# backplane_v4.net
KiCad netlist of a schematic drawn in EAGLE
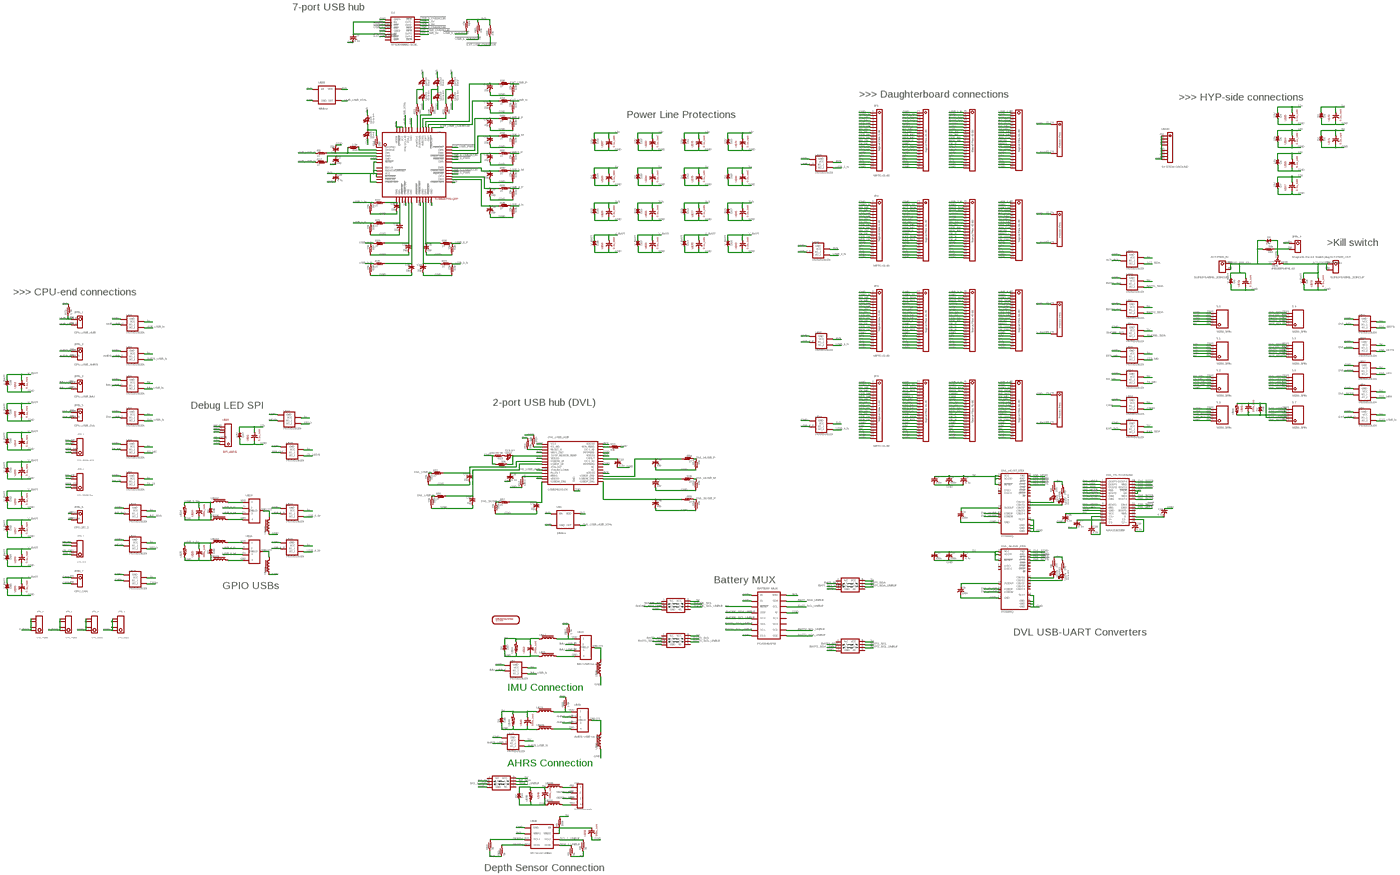
[diagram p0: schematic, sheet 1, overview]
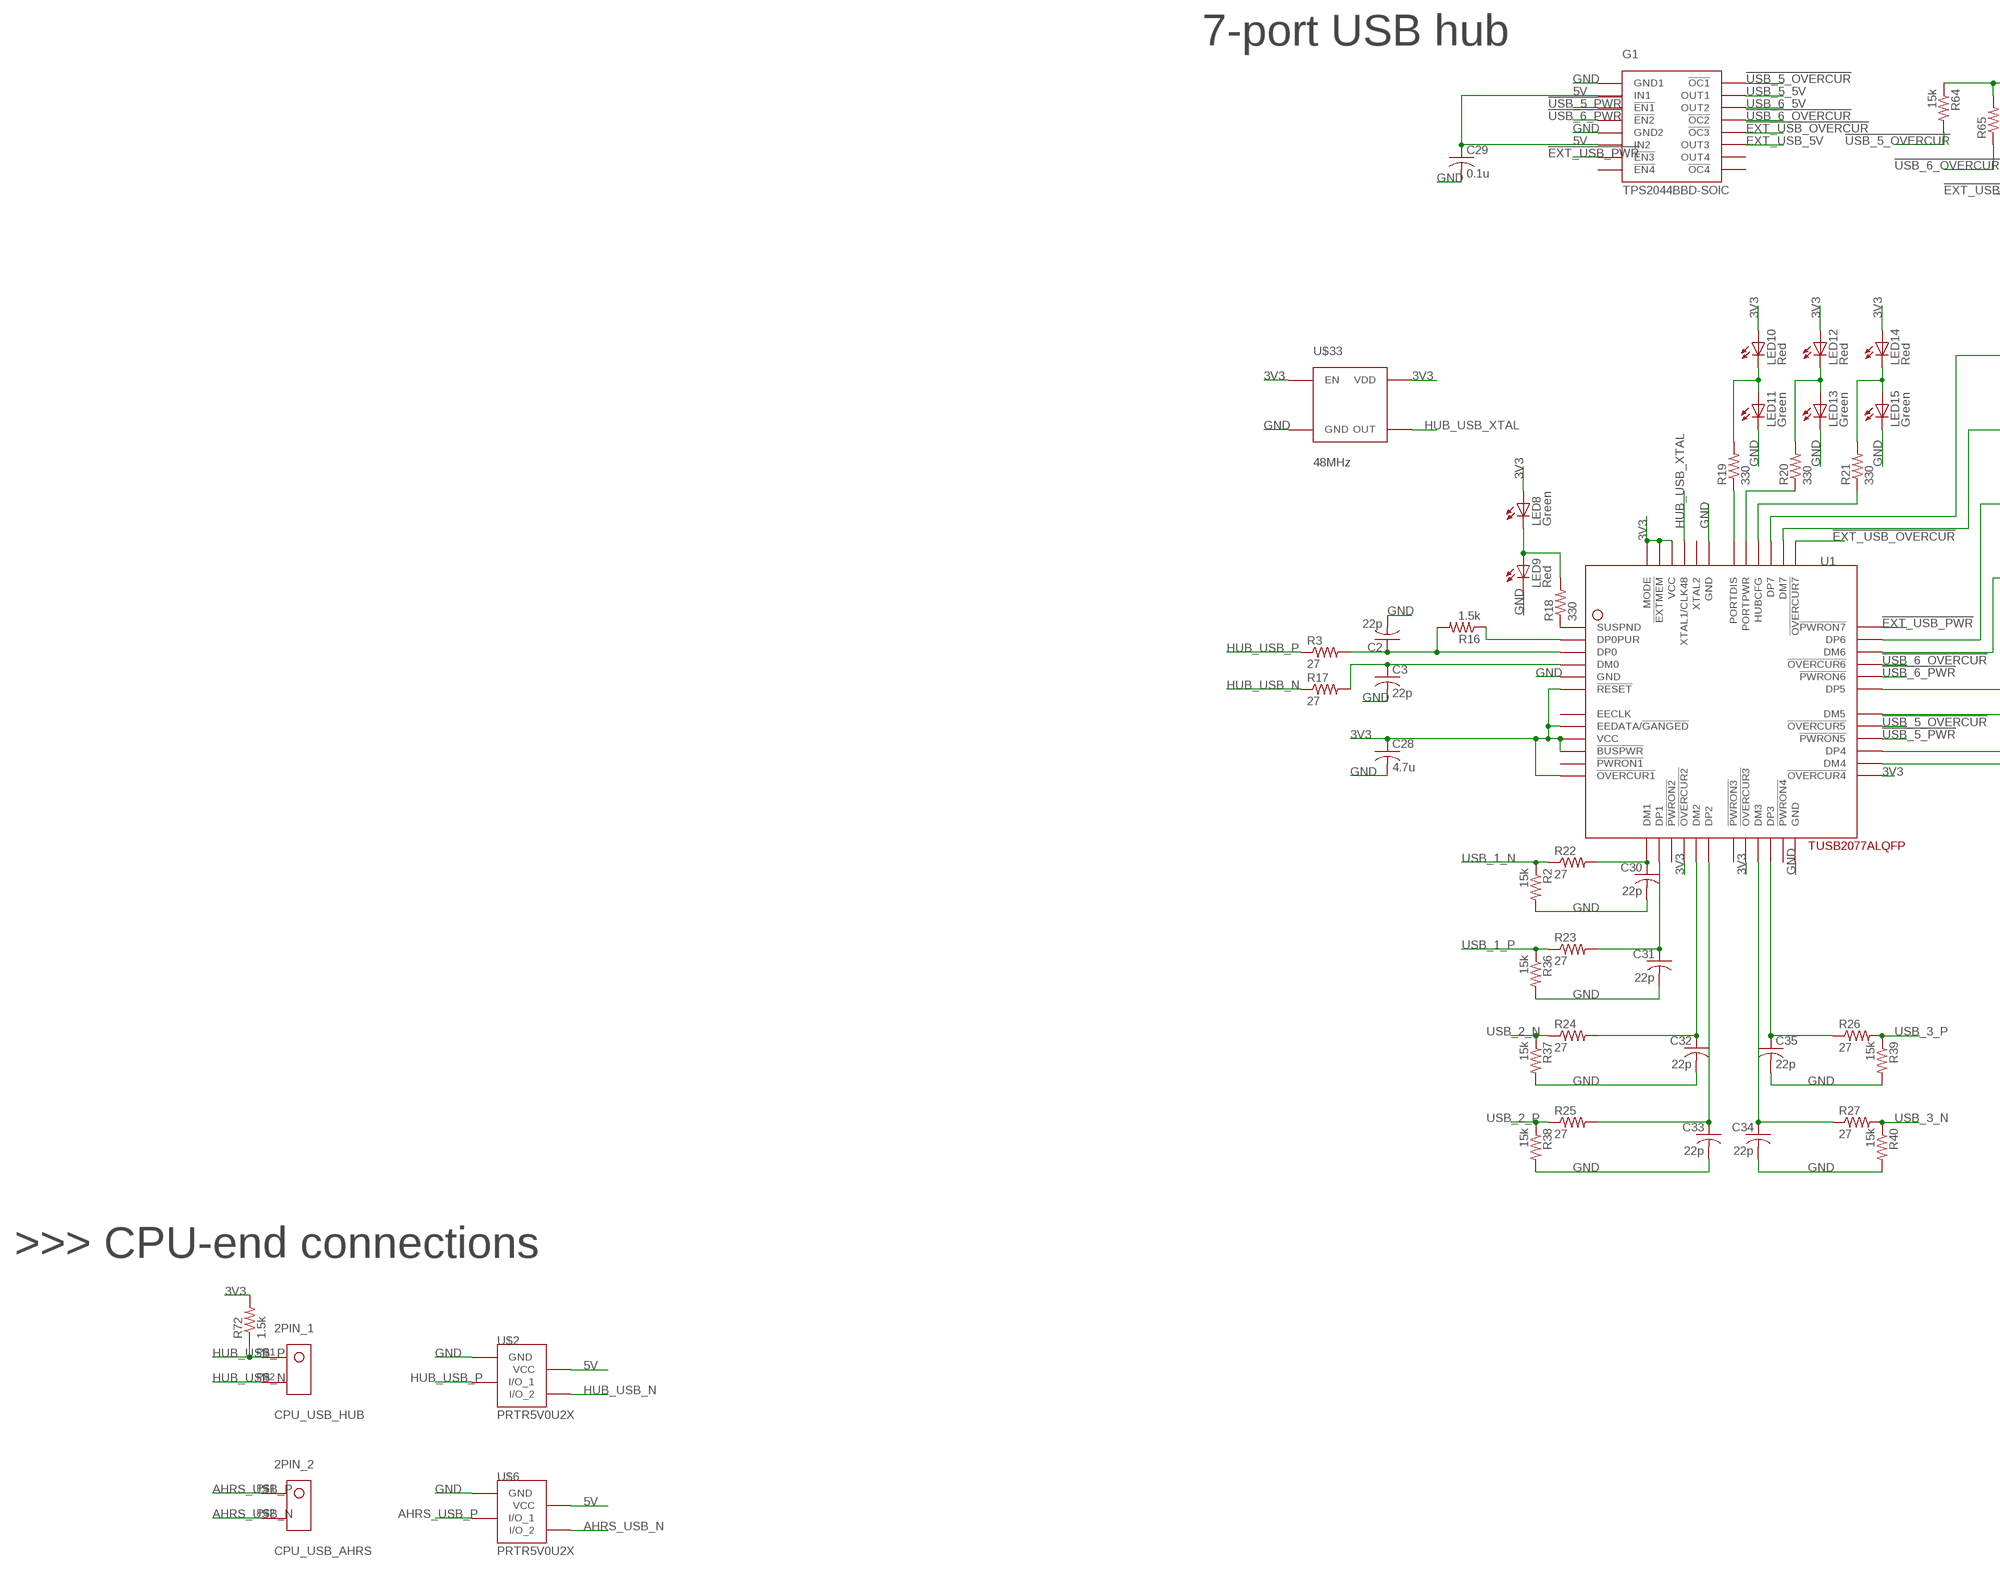
[diagram p1: schematic, sheet 1, part 1 of 5]
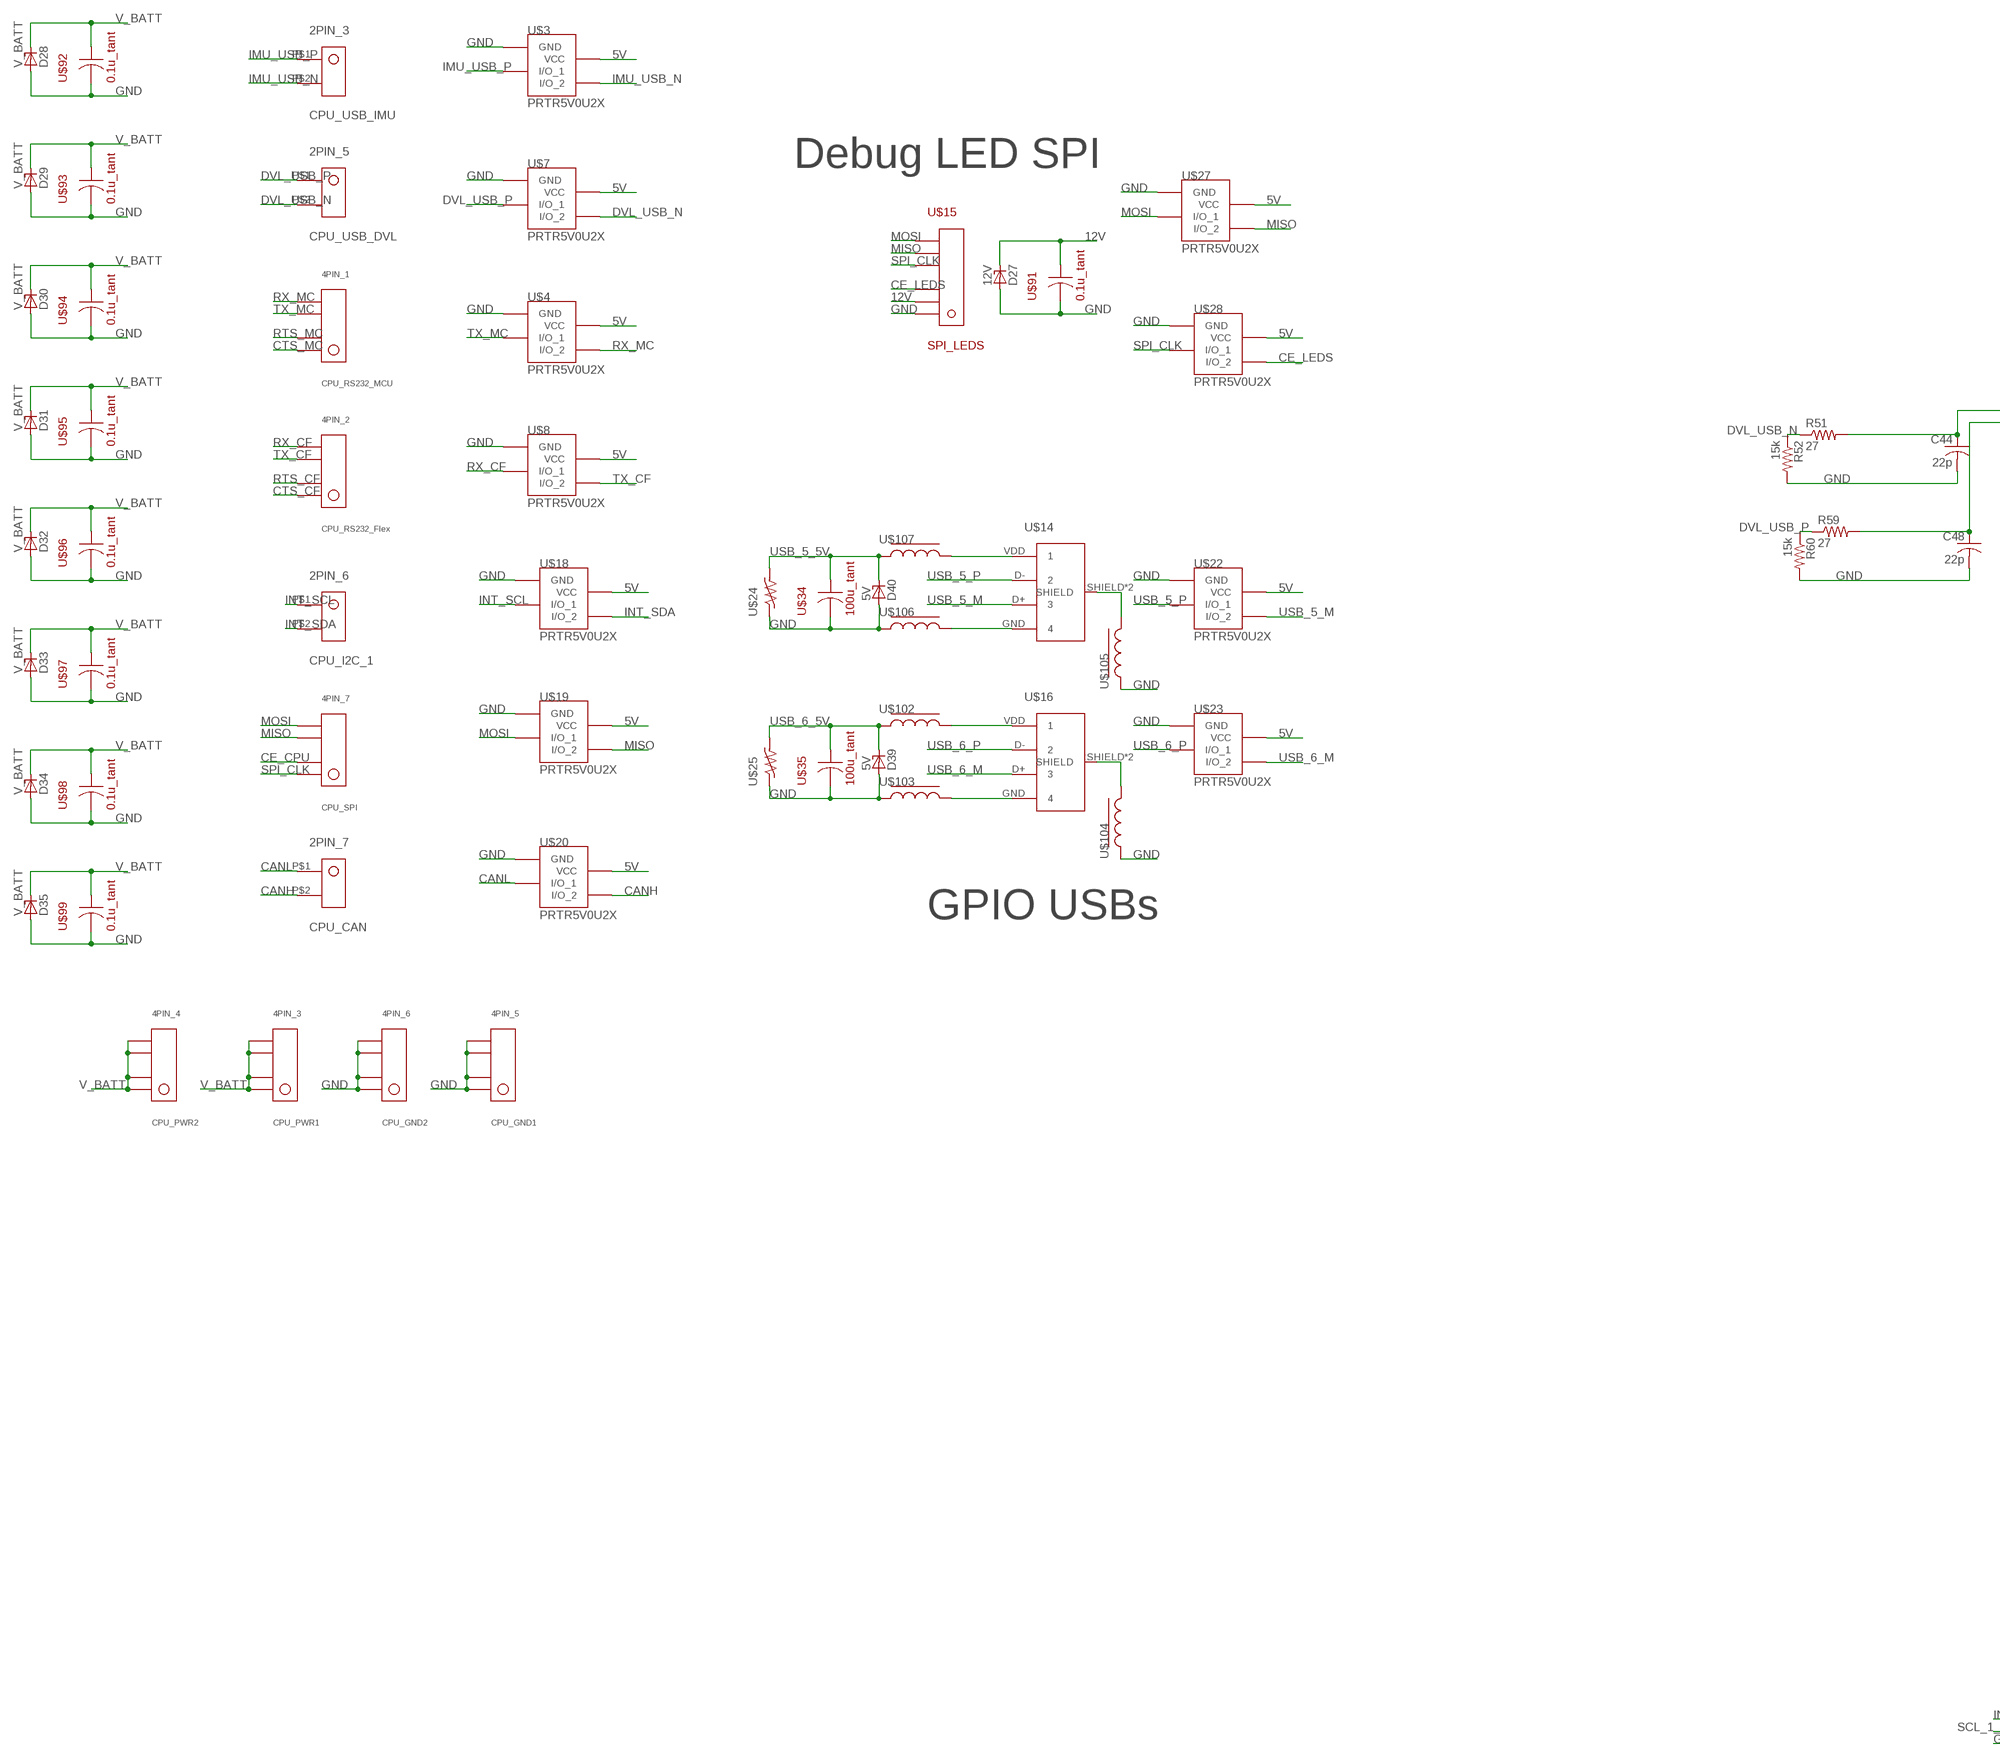
[diagram p2: schematic, sheet 1, part 2 of 5]
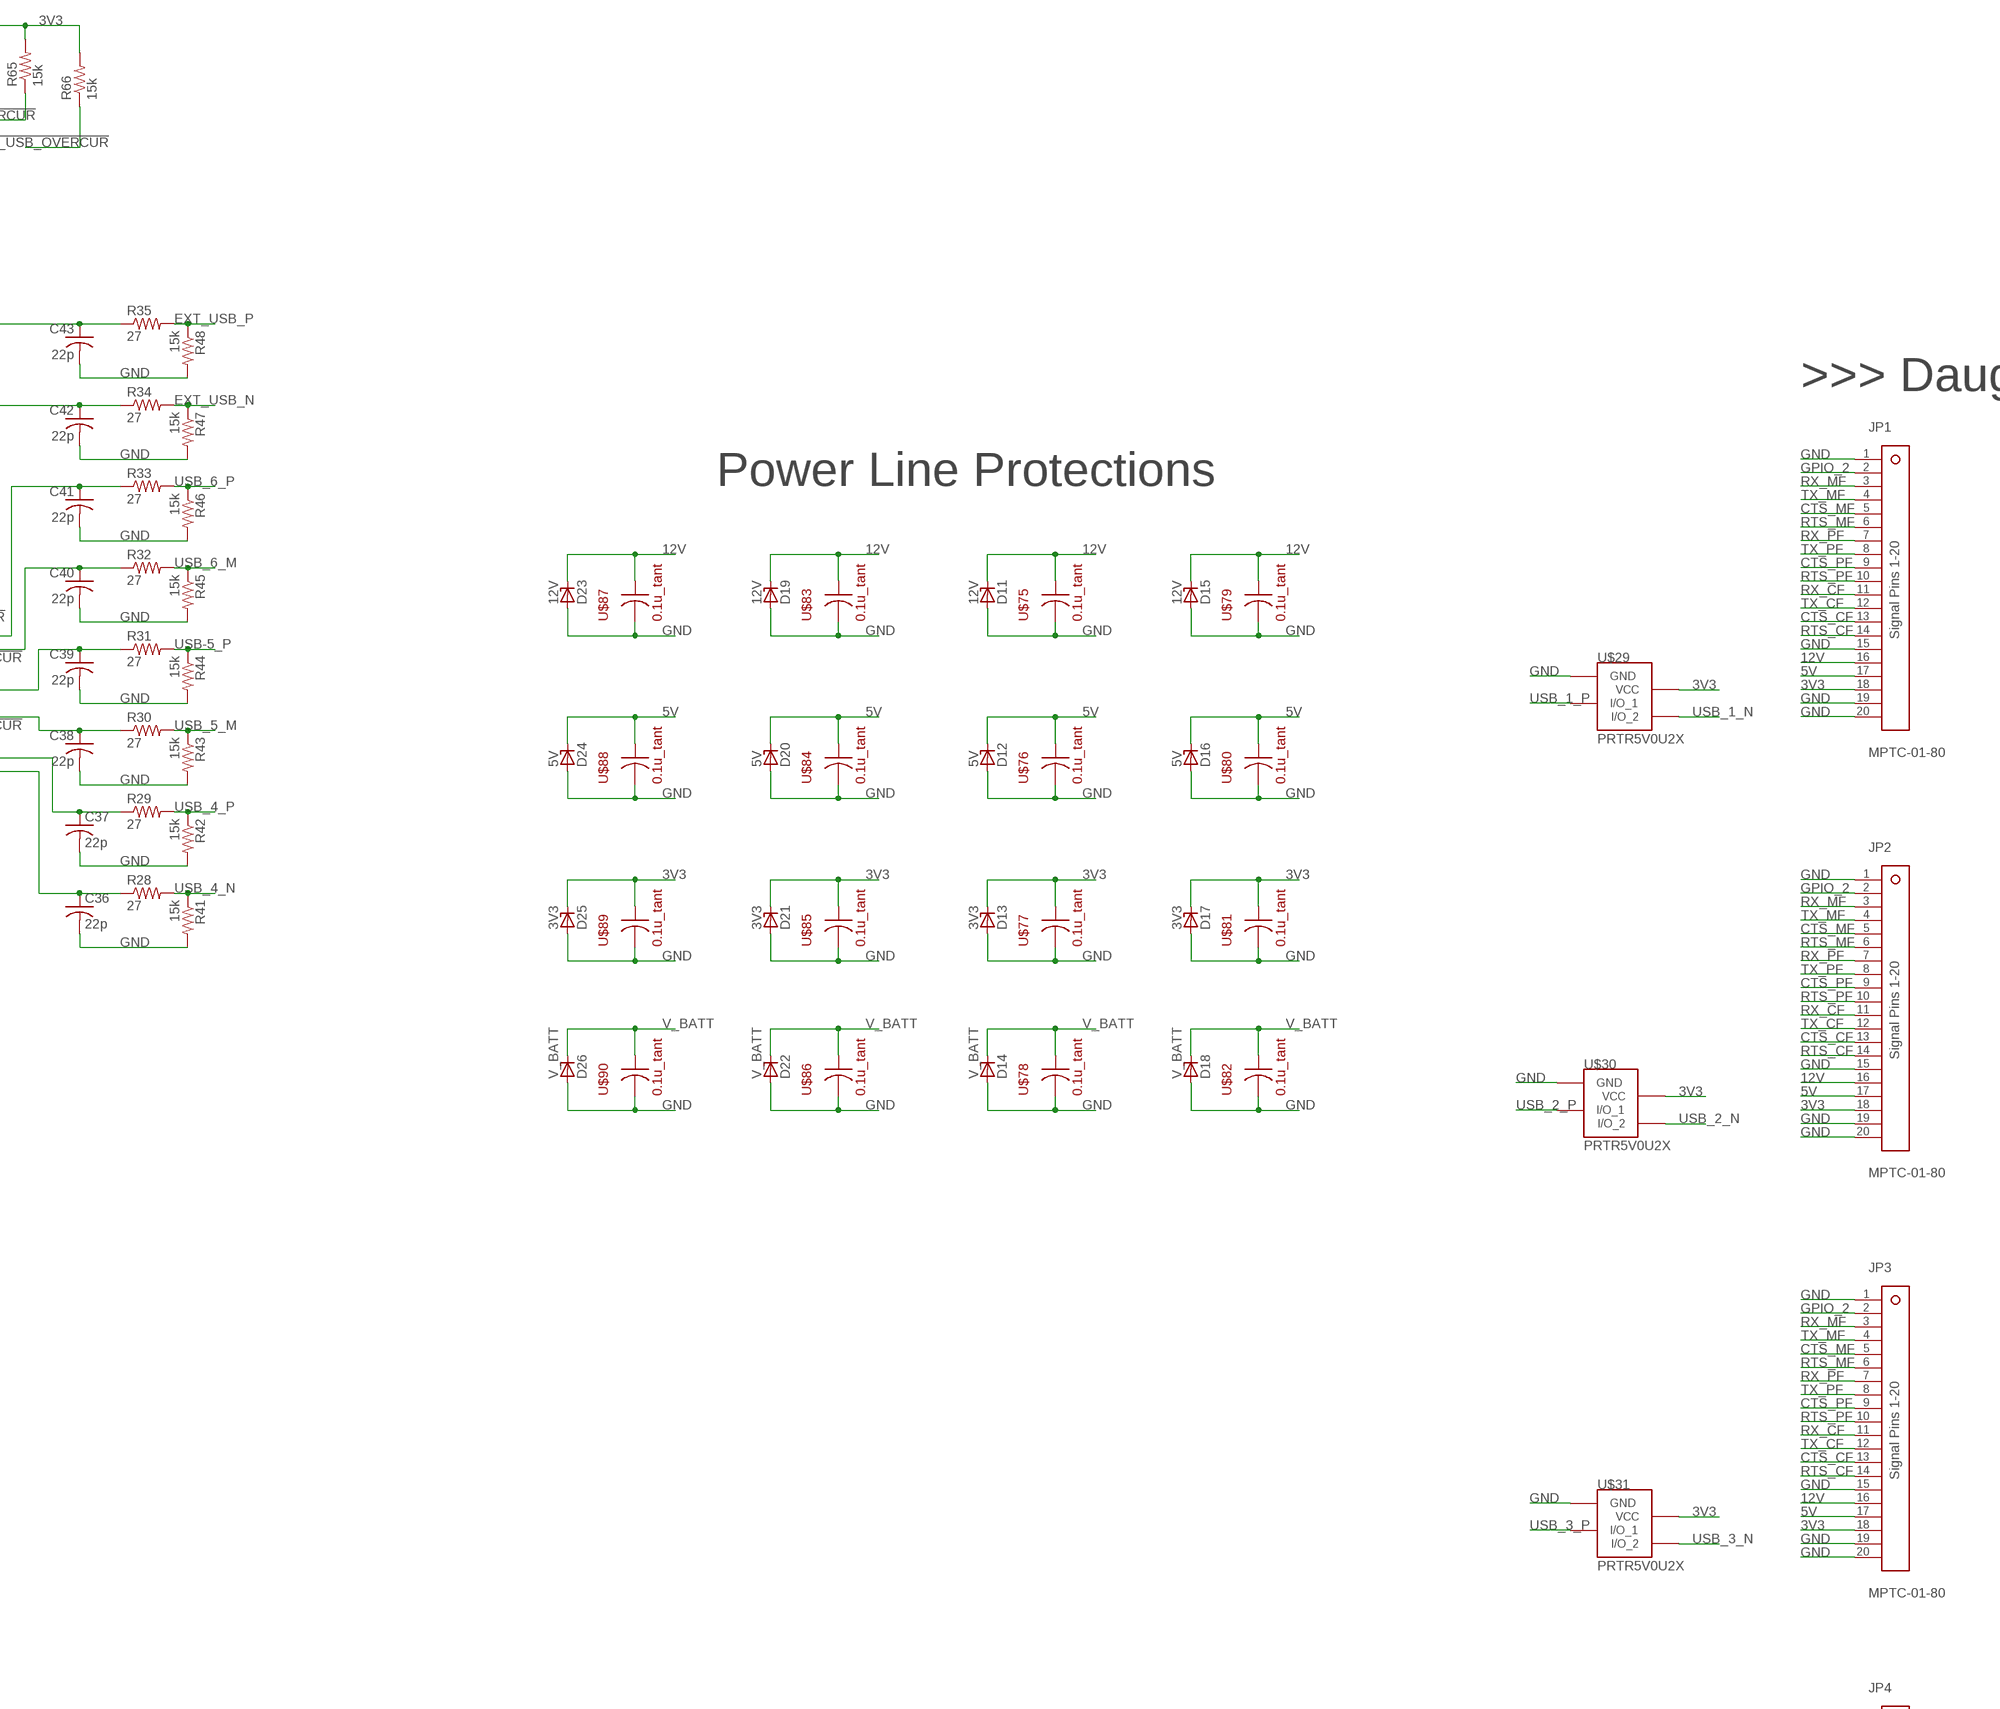
[diagram p3: schematic, sheet 1, part 3 of 5]
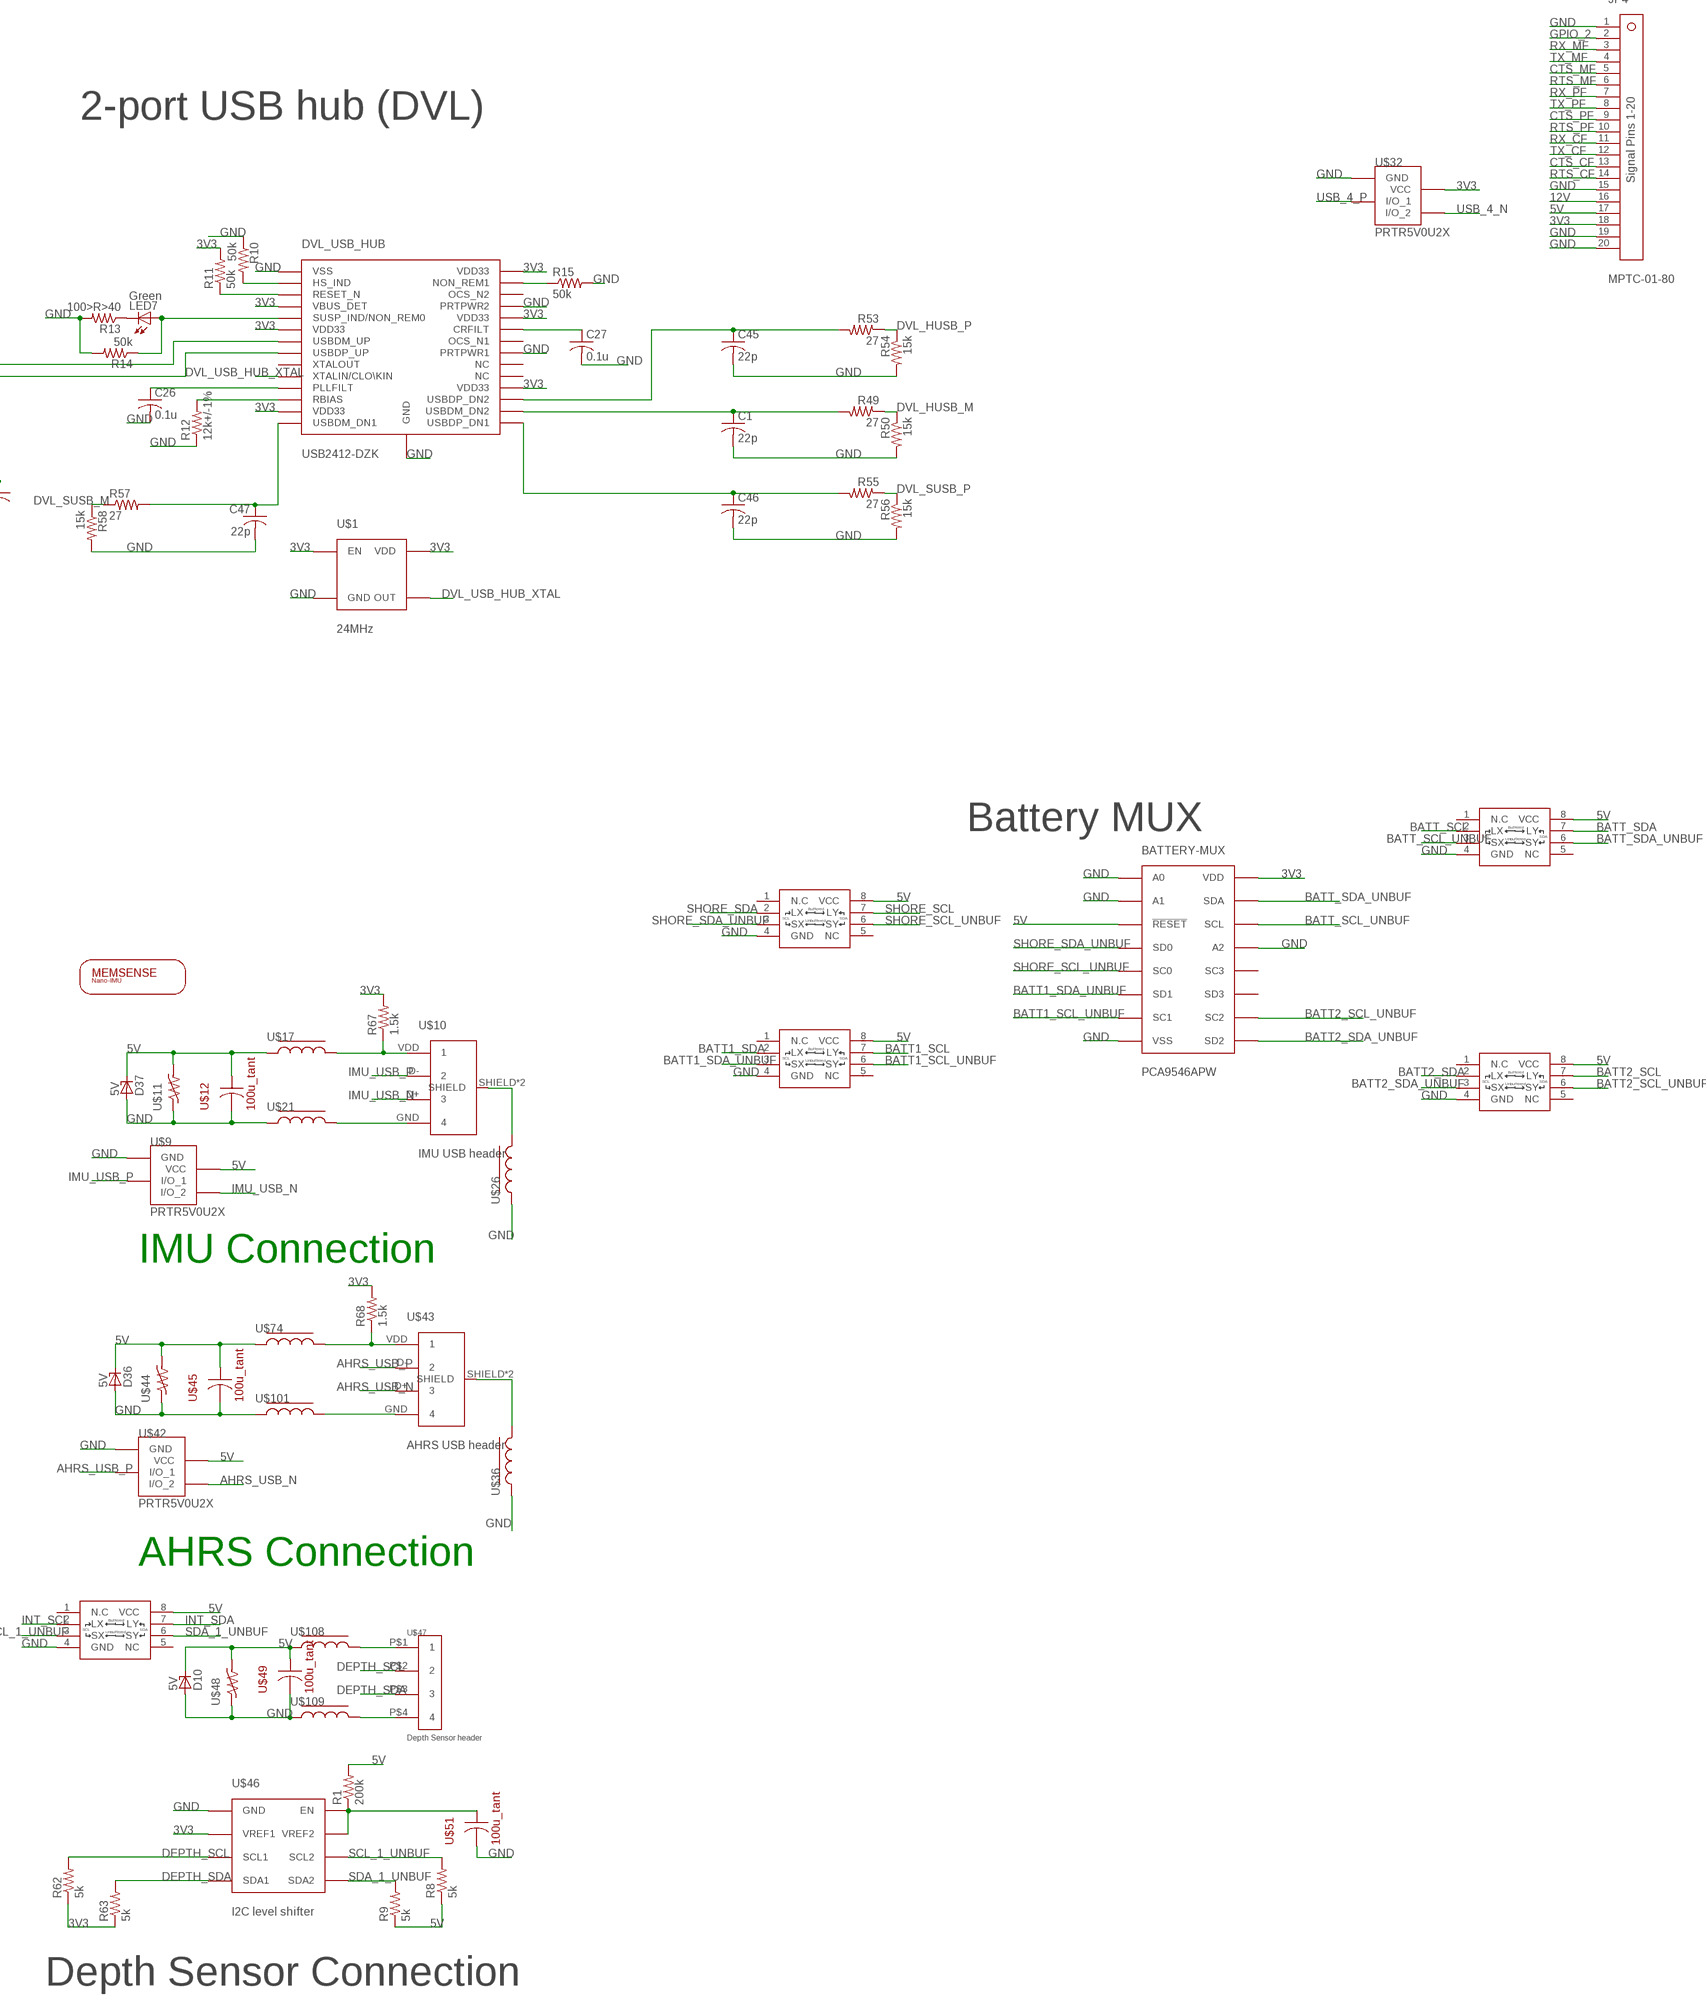
[diagram p4: schematic, sheet 1, part 4 of 5]
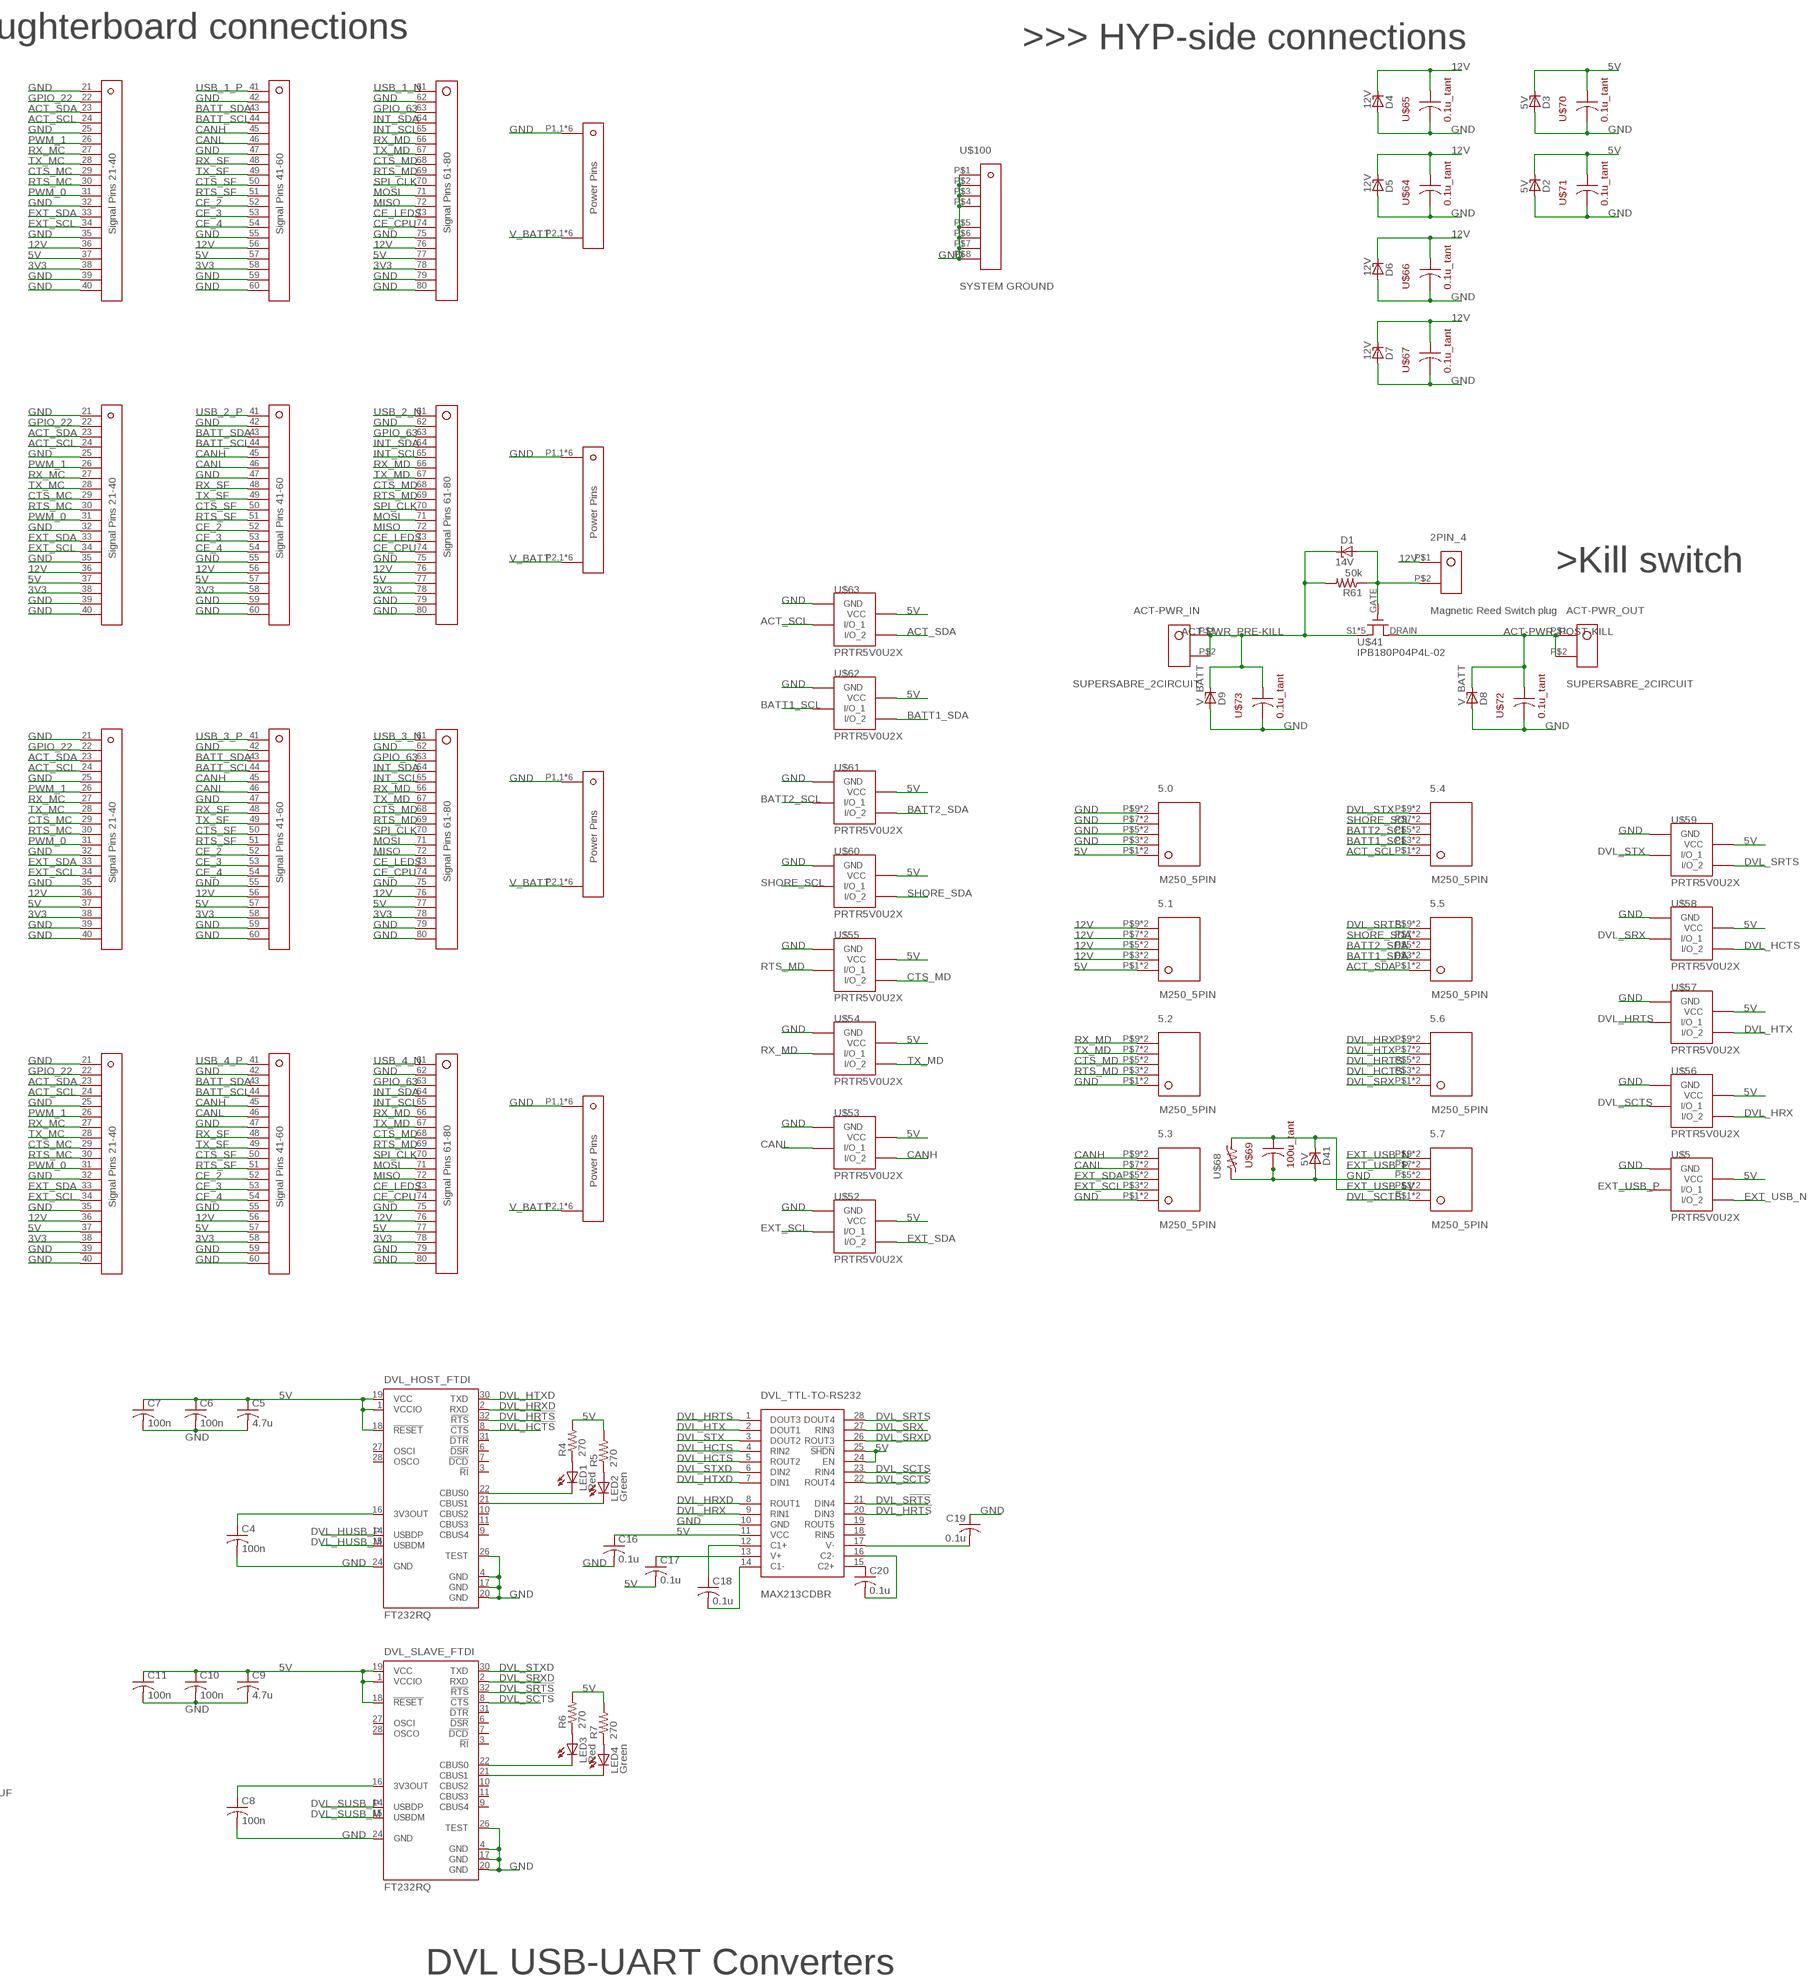
[diagram p5: schematic, sheet 1, part 5 of 5]

(export (version "E")
  (design (tool "Eeschema 10.0.6"))
  (components
    (comp (ref "2PIN_1")
      (value "CPU_USB_HUB")
      (footprint "eagle-import:KK254_VERT_2PIN")
      (libsource (lib "eagle-import") (part "KK254_VERT_2PIN22-29-2021"))
    )
    (comp (ref "2PIN_2")
      (value "CPU_USB_AHRS")
      (footprint "eagle-import:KK254_VERT_2PIN")
      (libsource (lib "eagle-import") (part "KK254_VERT_2PIN22-29-2021"))
    )
    (comp (ref "2PIN_3")
      (value "CPU_USB_IMU")
      (footprint "eagle-import:KK254_VERT_2PIN")
      (libsource (lib "eagle-import") (part "KK254_VERT_2PIN22-29-2021"))
    )
    (comp (ref "2PIN_4")
      (value "Magnetic Reed Switch plug")
      (footprint "eagle-import:KK254_VERT_2PIN")
      (libsource (lib "eagle-import") (part "KK254_VERT_2PIN22-29-2021"))
    )
    (comp (ref "2PIN_5")
      (value "CPU_USB_DVL")
      (footprint "eagle-import:KK254_VERT_2PIN")
      (libsource (lib "eagle-import") (part "KK254_VERT_2PIN22-29-2021"))
    )
    (comp (ref "2PIN_6")
      (value "CPU_I2C_1")
      (footprint "eagle-import:KK254_VERT_2PIN")
      (libsource (lib "eagle-import") (part "KK254_VERT_2PIN22-29-2021"))
    )
    (comp (ref "2PIN_7")
      (value "CPU_CAN")
      (footprint "eagle-import:KK254_VERT_2PIN")
      (libsource (lib "eagle-import") (part "KK254_VERT_2PIN22-29-2021"))
    )
    (comp (ref "4PIN_1")
      (value "CPU_RS232_MCU")
      (footprint "eagle-import:KK254_VERT_4PIN")
      (libsource (lib "eagle-import") (part "KK254_VERT_4PIN22-29-2041"))
    )
    (comp (ref "4PIN_2")
      (value "CPU_RS232_Flex")
      (footprint "eagle-import:KK254_VERT_4PIN")
      (libsource (lib "eagle-import") (part "KK254_VERT_4PIN22-29-2041"))
    )
    (comp (ref "4PIN_3")
      (value "CPU_PWR1")
      (footprint "eagle-import:KK254_VERT_4PIN")
      (libsource (lib "eagle-import") (part "KK254_VERT_4PIN22-29-2041"))
    )
    (comp (ref "4PIN_4")
      (value "CPU_PWR2")
      (footprint "eagle-import:KK254_VERT_4PIN")
      (libsource (lib "eagle-import") (part "KK254_VERT_4PIN22-29-2041"))
    )
    (comp (ref "4PIN_5")
      (value "CPU_GND1")
      (footprint "eagle-import:KK254_VERT_4PIN")
      (libsource (lib "eagle-import") (part "KK254_VERT_4PIN22-29-2041"))
    )
    (comp (ref "4PIN_6")
      (value "CPU_GND2")
      (footprint "eagle-import:KK254_VERT_4PIN")
      (libsource (lib "eagle-import") (part "KK254_VERT_4PIN22-29-2041"))
    )
    (comp (ref "4PIN_7")
      (value "CPU_SPI")
      (footprint "eagle-import:KK254_VERT_4PIN")
      (libsource (lib "eagle-import") (part "KK254_VERT_4PIN22-29-2041"))
    )
    (comp (ref "5.0")
      (value "M250_5PIN")
      (footprint "eagle-import:M205_5PIN")
      (libsource (lib "eagle-import") (part "M250_5PIN"))
    )
    (comp (ref "5.1")
      (value "M250_5PIN")
      (footprint "eagle-import:M205_5PIN")
      (libsource (lib "eagle-import") (part "M250_5PIN"))
    )
    (comp (ref "5.2")
      (value "M250_5PIN")
      (footprint "eagle-import:M205_5PIN")
      (libsource (lib "eagle-import") (part "M250_5PIN"))
    )
    (comp (ref "5.3")
      (value "M250_5PIN")
      (footprint "eagle-import:M205_5PIN")
      (libsource (lib "eagle-import") (part "M250_5PIN"))
    )
    (comp (ref "5.4")
      (value "M250_5PIN")
      (footprint "eagle-import:M205_5PIN")
      (libsource (lib "eagle-import") (part "M250_5PIN"))
    )
    (comp (ref "5.5")
      (value "M250_5PIN")
      (footprint "eagle-import:M205_5PIN")
      (libsource (lib "eagle-import") (part "M250_5PIN"))
    )
    (comp (ref "5.6")
      (value "M250_5PIN")
      (footprint "eagle-import:M205_5PIN")
      (libsource (lib "eagle-import") (part "M250_5PIN"))
    )
    (comp (ref "5.7")
      (value "M250_5PIN")
      (footprint "eagle-import:M205_5PIN")
      (libsource (lib "eagle-import") (part "M250_5PIN"))
    )
    (comp (ref "ACT-PWR_IN")
      (value "SUPERSABRE_2CIRCUIT")
      (footprint "eagle-import:SUPERSABRE_2CIRCUIT")
      (libsource (lib "eagle-import") (part "SUPERSABRE_2CIRCUIT"))
    )
    (comp (ref "ACT-PWR_OUT")
      (value "SUPERSABRE_2CIRCUIT")
      (footprint "eagle-import:SUPERSABRE_2CIRCUIT")
      (libsource (lib "eagle-import") (part "SUPERSABRE_2CIRCUIT"))
    )
    (comp (ref "BATTERY-MUX")
      (value "PCA9546APW")
      (footprint "eagle-import:TSSOP16")
      (libsource (lib "eagle-import") (part "PCA9546APW"))
    )
    (comp (ref "C1")
      (value "22p")
      (footprint "eagle-import:C0805")
      (libsource (lib "eagle-import") (part "C-USC0805"))
    )
    (comp (ref "C2")
      (value "22p")
      (footprint "eagle-import:C0805")
      (libsource (lib "eagle-import") (part "C-USC0805"))
    )
    (comp (ref "C3")
      (value "22p")
      (footprint "eagle-import:C0805")
      (libsource (lib "eagle-import") (part "C-USC0805"))
    )
    (comp (ref "C4")
      (value "100n")
      (footprint "eagle-import:C0805")
      (libsource (lib "eagle-import") (part "C-USC0805"))
    )
    (comp (ref "C5")
      (value "4.7u")
      (footprint "eagle-import:C0805")
      (libsource (lib "eagle-import") (part "C-USC0805"))
    )
    (comp (ref "C6")
      (value "100n")
      (footprint "eagle-import:C0805")
      (libsource (lib "eagle-import") (part "C-USC0805"))
    )
    (comp (ref "C7")
      (value "100n")
      (footprint "eagle-import:C0805")
      (libsource (lib "eagle-import") (part "C-USC0805"))
    )
    (comp (ref "C8")
      (value "100n")
      (footprint "eagle-import:C0805")
      (libsource (lib "eagle-import") (part "C-USC0805"))
    )
    (comp (ref "C9")
      (value "4.7u")
      (footprint "eagle-import:C0805")
      (libsource (lib "eagle-import") (part "C-USC0805"))
    )
    (comp (ref "C10")
      (value "100n")
      (footprint "eagle-import:C0805")
      (libsource (lib "eagle-import") (part "C-USC0805"))
    )
    (comp (ref "C11")
      (value "100n")
      (footprint "eagle-import:C0805")
      (libsource (lib "eagle-import") (part "C-USC0805"))
    )
    (comp (ref "C16")
      (value "0.1u")
      (footprint "eagle-import:C0805")
      (libsource (lib "eagle-import") (part "C-USC0805"))
    )
    (comp (ref "C17")
      (value "0.1u")
      (footprint "eagle-import:C0805")
      (libsource (lib "eagle-import") (part "C-USC0805"))
    )
    (comp (ref "C18")
      (value "0.1u")
      (footprint "eagle-import:C0805")
      (libsource (lib "eagle-import") (part "C-USC0805"))
    )
    (comp (ref "C19")
      (value "0.1u")
      (footprint "eagle-import:C0805")
      (libsource (lib "eagle-import") (part "C-USC0805"))
    )
    (comp (ref "C20")
      (value "0.1u")
      (footprint "eagle-import:C0805")
      (libsource (lib "eagle-import") (part "C-USC0805"))
    )
    (comp (ref "C26")
      (value "0.1u")
      (footprint "eagle-import:C0805")
      (libsource (lib "eagle-import") (part "C-USC0805"))
    )
    (comp (ref "C27")
      (value "0.1u")
      (footprint "eagle-import:C0805")
      (libsource (lib "eagle-import") (part "C-USC0805"))
    )
    (comp (ref "C28")
      (value "4.7u")
      (footprint "eagle-import:C0805")
      (libsource (lib "eagle-import") (part "C-USC0805"))
    )
    (comp (ref "C29")
      (value "0.1u")
      (footprint "eagle-import:C0805")
      (libsource (lib "eagle-import") (part "C-USC0805"))
    )
    (comp (ref "C30")
      (value "22p")
      (footprint "eagle-import:C0805")
      (libsource (lib "eagle-import") (part "C-USC0805"))
    )
    (comp (ref "C31")
      (value "22p")
      (footprint "eagle-import:C0805")
      (libsource (lib "eagle-import") (part "C-USC0805"))
    )
    (comp (ref "C32")
      (value "22p")
      (footprint "eagle-import:C0805")
      (libsource (lib "eagle-import") (part "C-USC0805"))
    )
    (comp (ref "C33")
      (value "22p")
      (footprint "eagle-import:C0805")
      (libsource (lib "eagle-import") (part "C-USC0805"))
    )
    (comp (ref "C34")
      (value "22p")
      (footprint "eagle-import:C0805")
      (libsource (lib "eagle-import") (part "C-USC0805"))
    )
    (comp (ref "C35")
      (value "22p")
      (footprint "eagle-import:C0805")
      (libsource (lib "eagle-import") (part "C-USC0805"))
    )
    (comp (ref "C36")
      (value "22p")
      (footprint "eagle-import:C0805")
      (libsource (lib "eagle-import") (part "C-USC0805"))
    )
    (comp (ref "C37")
      (value "22p")
      (footprint "eagle-import:C0805")
      (libsource (lib "eagle-import") (part "C-USC0805"))
    )
    (comp (ref "C38")
      (value "22p")
      (footprint "eagle-import:C0805")
      (libsource (lib "eagle-import") (part "C-USC0805"))
    )
    (comp (ref "C39")
      (value "22p")
      (footprint "eagle-import:C0805")
      (libsource (lib "eagle-import") (part "C-USC0805"))
    )
    (comp (ref "C40")
      (value "22p")
      (footprint "eagle-import:C0805")
      (libsource (lib "eagle-import") (part "C-USC0805"))
    )
    (comp (ref "C41")
      (value "22p")
      (footprint "eagle-import:C0805")
      (libsource (lib "eagle-import") (part "C-USC0805"))
    )
    (comp (ref "C42")
      (value "22p")
      (footprint "eagle-import:C0805")
      (libsource (lib "eagle-import") (part "C-USC0805"))
    )
    (comp (ref "C43")
      (value "22p")
      (footprint "eagle-import:C0805")
      (libsource (lib "eagle-import") (part "C-USC0805"))
    )
    (comp (ref "C44")
      (value "22p")
      (footprint "eagle-import:C0805")
      (libsource (lib "eagle-import") (part "C-USC0805"))
    )
    (comp (ref "C45")
      (value "22p")
      (footprint "eagle-import:C0805")
      (libsource (lib "eagle-import") (part "C-USC0805"))
    )
    (comp (ref "C46")
      (value "22p")
      (footprint "eagle-import:C0805")
      (libsource (lib "eagle-import") (part "C-USC0805"))
    )
    (comp (ref "C47")
      (value "22p")
      (footprint "eagle-import:C0805")
      (libsource (lib "eagle-import") (part "C-USC0805"))
    )
    (comp (ref "C48")
      (value "22p")
      (footprint "eagle-import:C0805")
      (libsource (lib "eagle-import") (part "C-USC0805"))
    )
    (comp (ref "D1")
      (value "14V")
      (footprint "eagle-import:SOD123")
      (libsource (lib "eagle-import") (part "ZENER-DIODESOD123"))
    )
    (comp (ref "D2")
      (value "5V")
      (footprint "eagle-import:SOD123")
      (libsource (lib "eagle-import") (part "ZENER-DIODESOD123"))
    )
    (comp (ref "D3")
      (value "5V")
      (footprint "eagle-import:SOD123")
      (libsource (lib "eagle-import") (part "ZENER-DIODESOD123"))
    )
    (comp (ref "D4")
      (value "12V")
      (footprint "eagle-import:SOD123")
      (libsource (lib "eagle-import") (part "ZENER-DIODESOD123"))
    )
    (comp (ref "D5")
      (value "12V")
      (footprint "eagle-import:SOD123")
      (libsource (lib "eagle-import") (part "ZENER-DIODESOD123"))
    )
    (comp (ref "D6")
      (value "12V")
      (footprint "eagle-import:SOD123")
      (libsource (lib "eagle-import") (part "ZENER-DIODESOD123"))
    )
    (comp (ref "D7")
      (value "12V")
      (footprint "eagle-import:SOD123")
      (libsource (lib "eagle-import") (part "ZENER-DIODESOD123"))
    )
    (comp (ref "D8")
      (value "V_BATT")
      (footprint "eagle-import:SOD123")
      (libsource (lib "eagle-import") (part "ZENER-DIODESOD123"))
    )
    (comp (ref "D9")
      (value "V_BATT")
      (footprint "eagle-import:SOD123")
      (libsource (lib "eagle-import") (part "ZENER-DIODESOD123"))
    )
    (comp (ref "D10")
      (value "5V")
      (footprint "eagle-import:SOD123")
      (libsource (lib "eagle-import") (part "ZENER-DIODESOD123"))
    )
    (comp (ref "D11")
      (value "12V")
      (footprint "eagle-import:SOD123")
      (libsource (lib "eagle-import") (part "ZENER-DIODESOD123"))
    )
    (comp (ref "D12")
      (value "5V")
      (footprint "eagle-import:SOD123")
      (libsource (lib "eagle-import") (part "ZENER-DIODESOD123"))
    )
    (comp (ref "D13")
      (value "3V3")
      (footprint "eagle-import:SOD123")
      (libsource (lib "eagle-import") (part "ZENER-DIODESOD123"))
    )
    (comp (ref "D14")
      (value "V_BATT")
      (footprint "eagle-import:SOD123")
      (libsource (lib "eagle-import") (part "ZENER-DIODESOD123"))
    )
    (comp (ref "D15")
      (value "12V")
      (footprint "eagle-import:SOD123")
      (libsource (lib "eagle-import") (part "ZENER-DIODESOD123"))
    )
    (comp (ref "D16")
      (value "5V")
      (footprint "eagle-import:SOD123")
      (libsource (lib "eagle-import") (part "ZENER-DIODESOD123"))
    )
    (comp (ref "D17")
      (value "3V3")
      (footprint "eagle-import:SOD123")
      (libsource (lib "eagle-import") (part "ZENER-DIODESOD123"))
    )
    (comp (ref "D18")
      (value "V_BATT")
      (footprint "eagle-import:SOD123")
      (libsource (lib "eagle-import") (part "ZENER-DIODESOD123"))
    )
    (comp (ref "D19")
      (value "12V")
      (footprint "eagle-import:SOD123")
      (libsource (lib "eagle-import") (part "ZENER-DIODESOD123"))
    )
    (comp (ref "D20")
      (value "5V")
      (footprint "eagle-import:SOD123")
      (libsource (lib "eagle-import") (part "ZENER-DIODESOD123"))
    )
    (comp (ref "D21")
      (value "3V3")
      (footprint "eagle-import:SOD123")
      (libsource (lib "eagle-import") (part "ZENER-DIODESOD123"))
    )
    (comp (ref "D22")
      (value "V_BATT")
      (footprint "eagle-import:SOD123")
      (libsource (lib "eagle-import") (part "ZENER-DIODESOD123"))
    )
    (comp (ref "D23")
      (value "12V")
      (footprint "eagle-import:SOD123")
      (libsource (lib "eagle-import") (part "ZENER-DIODESOD123"))
    )
    (comp (ref "D24")
      (value "5V")
      (footprint "eagle-import:SOD123")
      (libsource (lib "eagle-import") (part "ZENER-DIODESOD123"))
    )
    (comp (ref "D25")
      (value "3V3")
      (footprint "eagle-import:SOD123")
      (libsource (lib "eagle-import") (part "ZENER-DIODESOD123"))
    )
    (comp (ref "D26")
      (value "V_BATT")
      (footprint "eagle-import:SOD123")
      (libsource (lib "eagle-import") (part "ZENER-DIODESOD123"))
    )
    (comp (ref "D27")
      (value "12V")
      (footprint "eagle-import:SOD123")
      (libsource (lib "eagle-import") (part "ZENER-DIODESOD123"))
    )
    (comp (ref "D28")
      (value "V_BATT")
      (footprint "eagle-import:SOD123")
      (libsource (lib "eagle-import") (part "ZENER-DIODESOD123"))
    )
    (comp (ref "D29")
      (value "V_BATT")
      (footprint "eagle-import:SOD123")
      (libsource (lib "eagle-import") (part "ZENER-DIODESOD123"))
    )
    (comp (ref "D30")
      (value "V_BATT")
      (footprint "eagle-import:SOD123")
      (libsource (lib "eagle-import") (part "ZENER-DIODESOD123"))
    )
    (comp (ref "D31")
      (value "V_BATT")
      (footprint "eagle-import:SOD123")
      (libsource (lib "eagle-import") (part "ZENER-DIODESOD123"))
    )
    (comp (ref "D32")
      (value "V_BATT")
      (footprint "eagle-import:SOD123")
      (libsource (lib "eagle-import") (part "ZENER-DIODESOD123"))
    )
    (comp (ref "D33")
      (value "V_BATT")
      (footprint "eagle-import:SOD123")
      (libsource (lib "eagle-import") (part "ZENER-DIODESOD123"))
    )
    (comp (ref "D34")
      (value "V_BATT")
      (footprint "eagle-import:SOD123")
      (libsource (lib "eagle-import") (part "ZENER-DIODESOD123"))
    )
    (comp (ref "D35")
      (value "V_BATT")
      (footprint "eagle-import:SOD123")
      (libsource (lib "eagle-import") (part "ZENER-DIODESOD123"))
    )
    (comp (ref "D36")
      (value "5V")
      (footprint "eagle-import:SOD123")
      (libsource (lib "eagle-import") (part "ZENER-DIODESOD123"))
    )
    (comp (ref "D37")
      (value "5V")
      (footprint "eagle-import:SOD123")
      (libsource (lib "eagle-import") (part "ZENER-DIODESOD123"))
    )
    (comp (ref "D39")
      (value "5V")
      (footprint "eagle-import:SOD123")
      (libsource (lib "eagle-import") (part "ZENER-DIODESOD123"))
    )
    (comp (ref "D40")
      (value "5V")
      (footprint "eagle-import:SOD123")
      (libsource (lib "eagle-import") (part "ZENER-DIODESOD123"))
    )
    (comp (ref "D41")
      (value "5V")
      (footprint "eagle-import:SOD123")
      (libsource (lib "eagle-import") (part "ZENER-DIODESOD123"))
    )
    (comp (ref "DVL_HOST_FTDI")
      (value "FT232RQ")
      (footprint "eagle-import:QFN32")
      (libsource (lib "eagle-import") (part "FT232RQ"))
    )
    (comp (ref "DVL_SLAVE_FTDI")
      (value "FT232RQ")
      (footprint "eagle-import:QFN32")
      (libsource (lib "eagle-import") (part "FT232RQ"))
    )
    (comp (ref "DVL_TTL-TO-RS232")
      (value "MAX213CDBR")
      (footprint "eagle-import:SSOP28DB")
      (libsource (lib "eagle-import") (part "MAX213CDBR"))
    )
    (comp (ref "DVL_USB_HUB")
      (value "USB2412-DZK")
      (footprint "eagle-import:QFN-28")
      (libsource (lib "eagle-import") (part "USB2412-DZK"))
    )
    (comp (ref "G1")
      (value "TPS2044BBD-SOIC")
      (footprint "eagle-import:TPS2044")
      (libsource (lib "eagle-import") (part "TPS2044BBD-SOIC"))
    )
    (comp (ref "JP1")
      (value "MPTC-01-80")
      (footprint "eagle-import:MPTC-01-80")
      (libsource (lib "eagle-import") (part "MPTC-01-80"))
    )
    (comp (ref "JP2")
      (value "MPTC-01-80")
      (footprint "eagle-import:MPTC-01-80")
      (libsource (lib "eagle-import") (part "MPTC-01-80"))
    )
    (comp (ref "JP3")
      (value "MPTC-01-80")
      (footprint "eagle-import:MPTC-01-80")
      (libsource (lib "eagle-import") (part "MPTC-01-80"))
    )
    (comp (ref "JP4")
      (value "MPTC-01-80")
      (footprint "eagle-import:MPTC-01-80")
      (libsource (lib "eagle-import") (part "MPTC-01-80"))
    )
    (comp (ref "LED1")
      (value "Red")
      (footprint "eagle-import:CHIPLED_0805")
      (libsource (lib "eagle-import") (part "LEDCHIPLED_0805"))
    )
    (comp (ref "LED2")
      (value "Green")
      (footprint "eagle-import:CHIPLED_0805")
      (libsource (lib "eagle-import") (part "LEDCHIPLED_0805"))
    )
    (comp (ref "LED3")
      (value "Red")
      (footprint "eagle-import:CHIPLED_0805")
      (libsource (lib "eagle-import") (part "LEDCHIPLED_0805"))
    )
    (comp (ref "LED4")
      (value "Green")
      (footprint "eagle-import:CHIPLED_0805")
      (libsource (lib "eagle-import") (part "LEDCHIPLED_0805"))
    )
    (comp (ref "LED7")
      (value "Green")
      (footprint "eagle-import:CHIPLED_0805")
      (libsource (lib "eagle-import") (part "LEDCHIPLED_0805"))
    )
    (comp (ref "LED8")
      (value "Green")
      (footprint "eagle-import:CHIP-LED0805")
      (libsource (lib "eagle-import") (part "LEDCHIP-LED0805"))
    )
    (comp (ref "LED9")
      (value "Red")
      (footprint "eagle-import:CHIP-LED0805")
      (libsource (lib "eagle-import") (part "LEDCHIP-LED0805"))
    )
    (comp (ref "LED10")
      (value "Red")
      (footprint "eagle-import:CHIP-LED0805")
      (libsource (lib "eagle-import") (part "LEDCHIP-LED0805"))
    )
    (comp (ref "LED11")
      (value "Green")
      (footprint "eagle-import:CHIP-LED0805")
      (libsource (lib "eagle-import") (part "LEDCHIP-LED0805"))
    )
    (comp (ref "LED12")
      (value "Red")
      (footprint "eagle-import:CHIP-LED0805")
      (libsource (lib "eagle-import") (part "LEDCHIP-LED0805"))
    )
    (comp (ref "LED13")
      (value "Green")
      (footprint "eagle-import:CHIP-LED0805")
      (libsource (lib "eagle-import") (part "LEDCHIP-LED0805"))
    )
    (comp (ref "LED14")
      (value "Red")
      (footprint "eagle-import:CHIP-LED0805")
      (libsource (lib "eagle-import") (part "LEDCHIP-LED0805"))
    )
    (comp (ref "LED15")
      (value "Green")
      (footprint "eagle-import:CHIP-LED0805")
      (libsource (lib "eagle-import") (part "LEDCHIP-LED0805"))
    )
    (comp (ref "R1")
      (value "200k")
      (footprint "eagle-import:R0805")
      (libsource (lib "eagle-import") (part "R-US_R0805"))
    )
    (comp (ref "R2")
      (value "15k")
      (footprint "eagle-import:R0805")
      (libsource (lib "eagle-import") (part "R-US_R0805"))
    )
    (comp (ref "R3")
      (value "27")
      (footprint "eagle-import:R0805")
      (libsource (lib "eagle-import") (part "R-US_R0805"))
    )
    (comp (ref "R4")
      (value "270")
      (footprint "eagle-import:R0805")
      (libsource (lib "eagle-import") (part "R-US_R0805"))
    )
    (comp (ref "R5")
      (value "270")
      (footprint "eagle-import:R0805")
      (libsource (lib "eagle-import") (part "R-US_R0805"))
    )
    (comp (ref "R6")
      (value "270")
      (footprint "eagle-import:R0805")
      (libsource (lib "eagle-import") (part "R-US_R0805"))
    )
    (comp (ref "R7")
      (value "270")
      (footprint "eagle-import:R0805")
      (libsource (lib "eagle-import") (part "R-US_R0805"))
    )
    (comp (ref "R8")
      (value "5k")
      (footprint "eagle-import:R0805")
      (libsource (lib "eagle-import") (part "R-US_R0805"))
    )
    (comp (ref "R9")
      (value "5k")
      (footprint "eagle-import:R0805")
      (libsource (lib "eagle-import") (part "R-US_R0805"))
    )
    (comp (ref "R10")
      (value "50k")
      (footprint "eagle-import:R0805")
      (libsource (lib "eagle-import") (part "R-US_R0805"))
    )
    (comp (ref "R11")
      (value "50k")
      (footprint "eagle-import:R0805")
      (libsource (lib "eagle-import") (part "R-US_R0805"))
    )
    (comp (ref "R12")
      (value "12k+/-1%")
      (footprint "eagle-import:R0805")
      (libsource (lib "eagle-import") (part "R-US_R0805"))
    )
    (comp (ref "R13")
      (value "100>R>40")
      (footprint "eagle-import:R0805")
      (libsource (lib "eagle-import") (part "R-US_R0805"))
    )
    (comp (ref "R14")
      (value "50k")
      (footprint "eagle-import:R0805")
      (libsource (lib "eagle-import") (part "R-US_R0805"))
    )
    (comp (ref "R15")
      (value "50k")
      (footprint "eagle-import:R0805")
      (libsource (lib "eagle-import") (part "R-US_R0805"))
    )
    (comp (ref "R16")
      (value "1.5k")
      (footprint "eagle-import:R0805")
      (libsource (lib "eagle-import") (part "R-US_R0805"))
    )
    (comp (ref "R17")
      (value "27")
      (footprint "eagle-import:R0805")
      (libsource (lib "eagle-import") (part "R-US_R0805"))
    )
    (comp (ref "R18")
      (value "330")
      (footprint "eagle-import:R0805")
      (libsource (lib "eagle-import") (part "R-US_R0805"))
    )
    (comp (ref "R19")
      (value "330")
      (footprint "eagle-import:R0805")
      (libsource (lib "eagle-import") (part "R-US_R0805"))
    )
    (comp (ref "R20")
      (value "330")
      (footprint "eagle-import:R0805")
      (libsource (lib "eagle-import") (part "R-US_R0805"))
    )
    (comp (ref "R21")
      (value "330")
      (footprint "eagle-import:R0805")
      (libsource (lib "eagle-import") (part "R-US_R0805"))
    )
    (comp (ref "R22")
      (value "27")
      (footprint "eagle-import:R0805")
      (libsource (lib "eagle-import") (part "R-US_R0805"))
    )
    (comp (ref "R23")
      (value "27")
      (footprint "eagle-import:R0805")
      (libsource (lib "eagle-import") (part "R-US_R0805"))
    )
    (comp (ref "R24")
      (value "27")
      (footprint "eagle-import:R0805")
      (libsource (lib "eagle-import") (part "R-US_R0805"))
    )
    (comp (ref "R25")
      (value "27")
      (footprint "eagle-import:R0805")
      (libsource (lib "eagle-import") (part "R-US_R0805"))
    )
    (comp (ref "R26")
      (value "27")
      (footprint "eagle-import:R0805")
      (libsource (lib "eagle-import") (part "R-US_R0805"))
    )
    (comp (ref "R27")
      (value "27")
      (footprint "eagle-import:R0805")
      (libsource (lib "eagle-import") (part "R-US_R0805"))
    )
    (comp (ref "R28")
      (value "27")
      (footprint "eagle-import:R0805")
      (libsource (lib "eagle-import") (part "R-US_R0805"))
    )
    (comp (ref "R29")
      (value "27")
      (footprint "eagle-import:R0805")
      (libsource (lib "eagle-import") (part "R-US_R0805"))
    )
    (comp (ref "R30")
      (value "27")
      (footprint "eagle-import:R0805")
      (libsource (lib "eagle-import") (part "R-US_R0805"))
    )
    (comp (ref "R31")
      (value "27")
      (footprint "eagle-import:R0805")
      (libsource (lib "eagle-import") (part "R-US_R0805"))
    )
    (comp (ref "R32")
      (value "27")
      (footprint "eagle-import:R0805")
      (libsource (lib "eagle-import") (part "R-US_R0805"))
    )
    (comp (ref "R33")
      (value "27")
      (footprint "eagle-import:R0805")
      (libsource (lib "eagle-import") (part "R-US_R0805"))
    )
    (comp (ref "R34")
      (value "27")
      (footprint "eagle-import:R0805")
      (libsource (lib "eagle-import") (part "R-US_R0805"))
    )
    (comp (ref "R35")
      (value "27")
      (footprint "eagle-import:R0805")
      (libsource (lib "eagle-import") (part "R-US_R0805"))
    )
    (comp (ref "R36")
      (value "15k")
      (footprint "eagle-import:R0805")
      (libsource (lib "eagle-import") (part "R-US_R0805"))
    )
    (comp (ref "R37")
      (value "15k")
      (footprint "eagle-import:R0805")
      (libsource (lib "eagle-import") (part "R-US_R0805"))
    )
    (comp (ref "R38")
      (value "15k")
      (footprint "eagle-import:R0805")
      (libsource (lib "eagle-import") (part "R-US_R0805"))
    )
    (comp (ref "R39")
      (value "15k")
      (footprint "eagle-import:R0805")
      (libsource (lib "eagle-import") (part "R-US_R0805"))
    )
    (comp (ref "R40")
      (value "15k")
      (footprint "eagle-import:R0805")
      (libsource (lib "eagle-import") (part "R-US_R0805"))
    )
    (comp (ref "R41")
      (value "15k")
      (footprint "eagle-import:R0805")
      (libsource (lib "eagle-import") (part "R-US_R0805"))
    )
    (comp (ref "R42")
      (value "15k")
      (footprint "eagle-import:R0805")
      (libsource (lib "eagle-import") (part "R-US_R0805"))
    )
    (comp (ref "R43")
      (value "15k")
      (footprint "eagle-import:R0805")
      (libsource (lib "eagle-import") (part "R-US_R0805"))
    )
    (comp (ref "R44")
      (value "15k")
      (footprint "eagle-import:R0805")
      (libsource (lib "eagle-import") (part "R-US_R0805"))
    )
    (comp (ref "R45")
      (value "15k")
      (footprint "eagle-import:R0805")
      (libsource (lib "eagle-import") (part "R-US_R0805"))
    )
    (comp (ref "R46")
      (value "15k")
      (footprint "eagle-import:R0805")
      (libsource (lib "eagle-import") (part "R-US_R0805"))
    )
    (comp (ref "R47")
      (value "15k")
      (footprint "eagle-import:R0805")
      (libsource (lib "eagle-import") (part "R-US_R0805"))
    )
    (comp (ref "R48")
      (value "15k")
      (footprint "eagle-import:R0805")
      (libsource (lib "eagle-import") (part "R-US_R0805"))
    )
    (comp (ref "R49")
      (value "27")
      (footprint "eagle-import:R0805")
      (libsource (lib "eagle-import") (part "R-US_R0805"))
    )
    (comp (ref "R50")
      (value "15k")
      (footprint "eagle-import:R0805")
      (libsource (lib "eagle-import") (part "R-US_R0805"))
    )
    (comp (ref "R51")
      (value "27")
      (footprint "eagle-import:R0805")
      (libsource (lib "eagle-import") (part "R-US_R0805"))
    )
    (comp (ref "R52")
      (value "15k")
      (footprint "eagle-import:R0805")
      (libsource (lib "eagle-import") (part "R-US_R0805"))
    )
    (comp (ref "R53")
      (value "27")
      (footprint "eagle-import:R0805")
      (libsource (lib "eagle-import") (part "R-US_R0805"))
    )
    (comp (ref "R54")
      (value "15k")
      (footprint "eagle-import:R0805")
      (libsource (lib "eagle-import") (part "R-US_R0805"))
    )
    (comp (ref "R55")
      (value "27")
      (footprint "eagle-import:R0805")
      (libsource (lib "eagle-import") (part "R-US_R0805"))
    )
    (comp (ref "R56")
      (value "15k")
      (footprint "eagle-import:R0805")
      (libsource (lib "eagle-import") (part "R-US_R0805"))
    )
    (comp (ref "R57")
      (value "27")
      (footprint "eagle-import:R0805")
      (libsource (lib "eagle-import") (part "R-US_R0805"))
    )
    (comp (ref "R58")
      (value "15k")
      (footprint "eagle-import:R0805")
      (libsource (lib "eagle-import") (part "R-US_R0805"))
    )
    (comp (ref "R59")
      (value "27")
      (footprint "eagle-import:R0805")
      (libsource (lib "eagle-import") (part "R-US_R0805"))
    )
    (comp (ref "R60")
      (value "15k")
      (footprint "eagle-import:R0805")
      (libsource (lib "eagle-import") (part "R-US_R0805"))
    )
    (comp (ref "R61")
      (value "50k")
      (footprint "eagle-import:R0805")
      (libsource (lib "eagle-import") (part "R-US_R0805"))
    )
    (comp (ref "R62")
      (value "5k")
      (footprint "eagle-import:R0805")
      (libsource (lib "eagle-import") (part "R-US_R0805"))
    )
    (comp (ref "R63")
      (value "5k")
      (footprint "eagle-import:R0805")
      (libsource (lib "eagle-import") (part "R-US_R0805"))
    )
    (comp (ref "R64")
      (value "15k")
      (footprint "eagle-import:R0805")
      (libsource (lib "eagle-import") (part "R-US_R0805"))
    )
    (comp (ref "R65")
      (value "15k")
      (footprint "eagle-import:R0805")
      (libsource (lib "eagle-import") (part "R-US_R0805"))
    )
    (comp (ref "R66")
      (value "15k")
      (footprint "eagle-import:R0805")
      (libsource (lib "eagle-import") (part "R-US_R0805"))
    )
    (comp (ref "R67")
      (value "1.5k")
      (footprint "eagle-import:R0805")
      (libsource (lib "eagle-import") (part "R-US_R0805"))
    )
    (comp (ref "R68")
      (value "1.5k")
      (footprint "eagle-import:R0805")
      (libsource (lib "eagle-import") (part "R-US_R0805"))
    )
    (comp (ref "R72")
      (value "1.5k")
      (footprint "eagle-import:R0805")
      (libsource (lib "eagle-import") (part "R-US_R0805"))
    )
    (comp (ref "U$1")
      (value "24MHz")
      (footprint "eagle-import:4-CDFN_3.2X2.5MM")
      (libsource (lib "eagle-import") (part "DCS6XXX"))
    )
    (comp (ref "U$2")
      (value "PRTR5V0U2X")
      (footprint "eagle-import:SOT143B")
      (libsource (lib "eagle-import") (part "PRTR5V0U2X"))
    )
    (comp (ref "U$3")
      (value "PRTR5V0U2X")
      (footprint "eagle-import:SOT143B")
      (libsource (lib "eagle-import") (part "PRTR5V0U2X"))
    )
    (comp (ref "U$4")
      (value "PRTR5V0U2X")
      (footprint "eagle-import:SOT143B")
      (libsource (lib "eagle-import") (part "PRTR5V0U2X"))
    )
    (comp (ref "U$5")
      (value "PRTR5V0U2X")
      (footprint "eagle-import:SOT143B")
      (libsource (lib "eagle-import") (part "PRTR5V0U2X"))
    )
    (comp (ref "U$6")
      (value "PRTR5V0U2X")
      (footprint "eagle-import:SOT143B")
      (libsource (lib "eagle-import") (part "PRTR5V0U2X"))
    )
    (comp (ref "U$7")
      (value "PRTR5V0U2X")
      (footprint "eagle-import:SOT143B")
      (libsource (lib "eagle-import") (part "PRTR5V0U2X"))
    )
    (comp (ref "U$8")
      (value "PRTR5V0U2X")
      (footprint "eagle-import:SOT143B")
      (libsource (lib "eagle-import") (part "PRTR5V0U2X"))
    )
    (comp (ref "U$9")
      (value "PRTR5V0U2X")
      (footprint "eagle-import:SOT143B")
      (libsource (lib "eagle-import") (part "PRTR5V0U2X"))
    )
    (comp (ref "U$10")
      (value "IMU USB header")
      (footprint "eagle-import:UE27AE54100")
      (libsource (lib "eagle-import") (part "USB_4PIN_VERT"))
    )
    (comp (ref "U$11")
      (value "V5.5MLA0805")
      (footprint "eagle-import:0805")
      (libsource (lib "eagle-import") (part "V5.5MLA0805"))
    )
    (comp (ref "U$12")
      (value "100u_tant")
      (footprint "eagle-import:1206")
      (libsource (lib "eagle-import") (part "F93-XX-XXX-X-A"))
    )
    (comp (ref "U$13")
      (value "MEMSENSE_NIMU")
      (footprint "eagle-import:MEMSENSE_NIMU")
      (libsource (lib "eagle-import") (part "MEMSENSE_NIMU"))
    )
    (comp (ref "U$14")
      (value "USB_4PIN_VERT")
      (footprint "eagle-import:UE27AE54100")
      (libsource (lib "eagle-import") (part "USB_4PIN_VERT"))
    )
    (comp (ref "U$15")
      (value "SPI_LEDS")
      (footprint "eagle-import:KK254_6PIN")
      (libsource (lib "eagle-import") (part "KK254_6PIN"))
    )
    (comp (ref "U$16")
      (value "USB_4PIN_VERT")
      (footprint "eagle-import:UE27AE54100")
      (libsource (lib "eagle-import") (part "USB_4PIN_VERT"))
    )
    (comp (ref "U$17")
      (value "FERRITE_BEAD")
      (footprint "eagle-import:R0805")
      (libsource (lib "eagle-import") (part "FERRITE_BEAD"))
    )
    (comp (ref "U$18")
      (value "PRTR5V0U2X")
      (footprint "eagle-import:SOT143B")
      (libsource (lib "eagle-import") (part "PRTR5V0U2X"))
    )
    (comp (ref "U$19")
      (value "PRTR5V0U2X")
      (footprint "eagle-import:SOT143B")
      (libsource (lib "eagle-import") (part "PRTR5V0U2X"))
    )
    (comp (ref "U$20")
      (value "PRTR5V0U2X")
      (footprint "eagle-import:SOT143B")
      (libsource (lib "eagle-import") (part "PRTR5V0U2X"))
    )
    (comp (ref "U$21")
      (value "FERRITE_BEAD")
      (footprint "eagle-import:R0805")
      (libsource (lib "eagle-import") (part "FERRITE_BEAD"))
    )
    (comp (ref "U$22")
      (value "PRTR5V0U2X")
      (footprint "eagle-import:SOT143B")
      (libsource (lib "eagle-import") (part "PRTR5V0U2X"))
    )
    (comp (ref "U$23")
      (value "PRTR5V0U2X")
      (footprint "eagle-import:SOT143B")
      (libsource (lib "eagle-import") (part "PRTR5V0U2X"))
    )
    (comp (ref "U$24")
      (value "V5.5MLA0805")
      (footprint "eagle-import:0805")
      (libsource (lib "eagle-import") (part "V5.5MLA0805"))
    )
    (comp (ref "U$25")
      (value "V5.5MLA0805")
      (footprint "eagle-import:0805")
      (libsource (lib "eagle-import") (part "V5.5MLA0805"))
    )
    (comp (ref "U$26")
      (value "FERRITE_BEAD")
      (footprint "eagle-import:R0805")
      (libsource (lib "eagle-import") (part "FERRITE_BEAD"))
    )
    (comp (ref "U$27")
      (value "PRTR5V0U2X")
      (footprint "eagle-import:SOT143B")
      (libsource (lib "eagle-import") (part "PRTR5V0U2X"))
    )
    (comp (ref "U$28")
      (value "PRTR5V0U2X")
      (footprint "eagle-import:SOT143B")
      (libsource (lib "eagle-import") (part "PRTR5V0U2X"))
    )
    (comp (ref "U$29")
      (value "PRTR5V0U2X")
      (footprint "eagle-import:SOT143B")
      (libsource (lib "eagle-import") (part "PRTR5V0U2X"))
    )
    (comp (ref "U$30")
      (value "PRTR5V0U2X")
      (footprint "eagle-import:SOT143B")
      (libsource (lib "eagle-import") (part "PRTR5V0U2X"))
    )
    (comp (ref "U$31")
      (value "PRTR5V0U2X")
      (footprint "eagle-import:SOT143B")
      (libsource (lib "eagle-import") (part "PRTR5V0U2X"))
    )
    (comp (ref "U$32")
      (value "PRTR5V0U2X")
      (footprint "eagle-import:SOT143B")
      (libsource (lib "eagle-import") (part "PRTR5V0U2X"))
    )
    (comp (ref "U$33")
      (value "48MHz")
      (footprint "eagle-import:4-CDFN_3.2X2.5MM")
      (libsource (lib "eagle-import") (part "DCS6XXX"))
    )
    (comp (ref "U$34")
      (value "100u_tant")
      (footprint "eagle-import:1206")
      (libsource (lib "eagle-import") (part "F93-XX-XXX-X-A"))
    )
    (comp (ref "U$35")
      (value "100u_tant")
      (footprint "eagle-import:1206")
      (libsource (lib "eagle-import") (part "F93-XX-XXX-X-A"))
    )
    (comp (ref "U$36")
      (value "FERRITE_BEAD")
      (footprint "eagle-import:R0805")
      (libsource (lib "eagle-import") (part "FERRITE_BEAD"))
    )
    (comp (ref "U$37")
      (value "P82B715")
      (footprint "eagle-import:SO8")
      (libsource (lib "eagle-import") (part "P82B715"))
    )
    (comp (ref "U$38")
      (value "P82B715")
      (footprint "eagle-import:SO8")
      (libsource (lib "eagle-import") (part "P82B715"))
    )
    (comp (ref "U$39")
      (value "P82B715")
      (footprint "eagle-import:SO8")
      (libsource (lib "eagle-import") (part "P82B715"))
    )
    (comp (ref "U$40")
      (value "P82B715")
      (footprint "eagle-import:SO8")
      (libsource (lib "eagle-import") (part "P82B715"))
    )
    (comp (ref "U$41")
      (value "IPB180P04P4L-02")
      (footprint "eagle-import:PG-TO263-7-3")
      (libsource (lib "eagle-import") (part "IPB180P04P4L-02"))
    )
    (comp (ref "U$42")
      (value "PRTR5V0U2X")
      (footprint "eagle-import:SOT143B")
      (libsource (lib "eagle-import") (part "PRTR5V0U2X"))
    )
    (comp (ref "U$43")
      (value "AHRS USB header")
      (footprint "eagle-import:UE27AE54100")
      (libsource (lib "eagle-import") (part "USB_4PIN_VERT"))
    )
    (comp (ref "U$44")
      (value "V5.5MLA0805")
      (footprint "eagle-import:0805")
      (libsource (lib "eagle-import") (part "V5.5MLA0805"))
    )
    (comp (ref "U$45")
      (value "100u_tant")
      (footprint "eagle-import:1206")
      (libsource (lib "eagle-import") (part "F93-XX-XXX-X-A"))
    )
    (comp (ref "U$46")
      (value "I2C level shifter")
      (footprint "eagle-import:SM8")
      (libsource (lib "eagle-import") (part "PCA9306DCT"))
    )
    (comp (ref "U$47")
      (value "Depth Sensor header")
      (footprint "eagle-import:DF13-4")
      (libsource (lib "eagle-import") (part "DF13-4"))
    )
    (comp (ref "U$48")
      (value "V5.5MLA0805")
      (footprint "eagle-import:0805")
      (libsource (lib "eagle-import") (part "V5.5MLA0805"))
    )
    (comp (ref "U$49")
      (value "100u_tant")
      (footprint "eagle-import:1206")
      (libsource (lib "eagle-import") (part "F93-XX-XXX-X-A"))
    )
    (comp (ref "U$50")
      (value "P82B715")
      (footprint "eagle-import:SO8")
      (libsource (lib "eagle-import") (part "P82B715"))
    )
    (comp (ref "U$51")
      (value "100u_tant")
      (footprint "eagle-import:1206")
      (libsource (lib "eagle-import") (part "F93-XX-XXX-X-A"))
    )
    (comp (ref "U$52")
      (value "PRTR5V0U2X")
      (footprint "eagle-import:SOT143B")
      (libsource (lib "eagle-import") (part "PRTR5V0U2X"))
    )
    (comp (ref "U$53")
      (value "PRTR5V0U2X")
      (footprint "eagle-import:SOT143B")
      (libsource (lib "eagle-import") (part "PRTR5V0U2X"))
    )
    (comp (ref "U$54")
      (value "PRTR5V0U2X")
      (footprint "eagle-import:SOT143B")
      (libsource (lib "eagle-import") (part "PRTR5V0U2X"))
    )
    (comp (ref "U$55")
      (value "PRTR5V0U2X")
      (footprint "eagle-import:SOT143B")
      (libsource (lib "eagle-import") (part "PRTR5V0U2X"))
    )
    (comp (ref "U$56")
      (value "PRTR5V0U2X")
      (footprint "eagle-import:SOT143B")
      (libsource (lib "eagle-import") (part "PRTR5V0U2X"))
    )
    (comp (ref "U$57")
      (value "PRTR5V0U2X")
      (footprint "eagle-import:SOT143B")
      (libsource (lib "eagle-import") (part "PRTR5V0U2X"))
    )
    (comp (ref "U$58")
      (value "PRTR5V0U2X")
      (footprint "eagle-import:SOT143B")
      (libsource (lib "eagle-import") (part "PRTR5V0U2X"))
    )
    (comp (ref "U$59")
      (value "PRTR5V0U2X")
      (footprint "eagle-import:SOT143B")
      (libsource (lib "eagle-import") (part "PRTR5V0U2X"))
    )
    (comp (ref "U$60")
      (value "PRTR5V0U2X")
      (footprint "eagle-import:SOT143B")
      (libsource (lib "eagle-import") (part "PRTR5V0U2X"))
    )
    (comp (ref "U$61")
      (value "PRTR5V0U2X")
      (footprint "eagle-import:SOT143B")
      (libsource (lib "eagle-import") (part "PRTR5V0U2X"))
    )
    (comp (ref "U$62")
      (value "PRTR5V0U2X")
      (footprint "eagle-import:SOT143B")
      (libsource (lib "eagle-import") (part "PRTR5V0U2X"))
    )
    (comp (ref "U$63")
      (value "PRTR5V0U2X")
      (footprint "eagle-import:SOT143B")
      (libsource (lib "eagle-import") (part "PRTR5V0U2X"))
    )
    (comp (ref "U$64")
      (value "0.1u_tant")
      (footprint "eagle-import:1206")
      (libsource (lib "eagle-import") (part "F93-XX-XXX-X-A"))
    )
    (comp (ref "U$65")
      (value "0.1u_tant")
      (footprint "eagle-import:1206")
      (libsource (lib "eagle-import") (part "F93-XX-XXX-X-A"))
    )
    (comp (ref "U$66")
      (value "0.1u_tant")
      (footprint "eagle-import:1206")
      (libsource (lib "eagle-import") (part "F93-XX-XXX-X-A"))
    )
    (comp (ref "U$67")
      (value "0.1u_tant")
      (footprint "eagle-import:1206")
      (libsource (lib "eagle-import") (part "F93-XX-XXX-X-A"))
    )
    (comp (ref "U$68")
      (value "V5.5MLA0805")
      (footprint "eagle-import:0805")
      (libsource (lib "eagle-import") (part "V5.5MLA0805"))
    )
    (comp (ref "U$69")
      (value "100u_tant")
      (footprint "eagle-import:1206")
      (libsource (lib "eagle-import") (part "F93-XX-XXX-X-A"))
    )
    (comp (ref "U$70")
      (value "0.1u_tant")
      (footprint "eagle-import:1206")
      (libsource (lib "eagle-import") (part "F93-XX-XXX-X-A"))
    )
    (comp (ref "U$71")
      (value "0.1u_tant")
      (footprint "eagle-import:1206")
      (libsource (lib "eagle-import") (part "F93-XX-XXX-X-A"))
    )
    (comp (ref "U$72")
      (value "0.1u_tant")
      (footprint "eagle-import:1206")
      (libsource (lib "eagle-import") (part "F93-XX-XXX-X-A"))
    )
    (comp (ref "U$73")
      (value "0.1u_tant")
      (footprint "eagle-import:1206")
      (libsource (lib "eagle-import") (part "F93-XX-XXX-X-A"))
    )
    (comp (ref "U$74")
      (value "FERRITE_BEAD")
      (footprint "eagle-import:R0805")
      (libsource (lib "eagle-import") (part "FERRITE_BEAD"))
    )
    (comp (ref "U$75")
      (value "0.1u_tant")
      (footprint "eagle-import:1206")
      (libsource (lib "eagle-import") (part "F93-XX-XXX-X-A"))
    )
    (comp (ref "U$76")
      (value "0.1u_tant")
      (footprint "eagle-import:1206")
      (libsource (lib "eagle-import") (part "F93-XX-XXX-X-A"))
    )
    (comp (ref "U$77")
      (value "0.1u_tant")
      (footprint "eagle-import:1206")
      (libsource (lib "eagle-import") (part "F93-XX-XXX-X-A"))
    )
    (comp (ref "U$78")
      (value "0.1u_tant")
      (footprint "eagle-import:1206")
      (libsource (lib "eagle-import") (part "F93-XX-XXX-X-A"))
    )
    (comp (ref "U$79")
      (value "0.1u_tant")
      (footprint "eagle-import:1206")
      (libsource (lib "eagle-import") (part "F93-XX-XXX-X-A"))
    )
    (comp (ref "U$80")
      (value "0.1u_tant")
      (footprint "eagle-import:1206")
      (libsource (lib "eagle-import") (part "F93-XX-XXX-X-A"))
    )
    (comp (ref "U$81")
      (value "0.1u_tant")
      (footprint "eagle-import:1206")
      (libsource (lib "eagle-import") (part "F93-XX-XXX-X-A"))
    )
    (comp (ref "U$82")
      (value "0.1u_tant")
      (footprint "eagle-import:1206")
      (libsource (lib "eagle-import") (part "F93-XX-XXX-X-A"))
    )
    (comp (ref "U$83")
      (value "0.1u_tant")
      (footprint "eagle-import:1206")
      (libsource (lib "eagle-import") (part "F93-XX-XXX-X-A"))
    )
    (comp (ref "U$84")
      (value "0.1u_tant")
      (footprint "eagle-import:1206")
      (libsource (lib "eagle-import") (part "F93-XX-XXX-X-A"))
    )
    (comp (ref "U$85")
      (value "0.1u_tant")
      (footprint "eagle-import:1206")
      (libsource (lib "eagle-import") (part "F93-XX-XXX-X-A"))
    )
    (comp (ref "U$86")
      (value "0.1u_tant")
      (footprint "eagle-import:1206")
      (libsource (lib "eagle-import") (part "F93-XX-XXX-X-A"))
    )
    (comp (ref "U$87")
      (value "0.1u_tant")
      (footprint "eagle-import:1206")
      (libsource (lib "eagle-import") (part "F93-XX-XXX-X-A"))
    )
    (comp (ref "U$88")
      (value "0.1u_tant")
      (footprint "eagle-import:1206")
      (libsource (lib "eagle-import") (part "F93-XX-XXX-X-A"))
    )
    (comp (ref "U$89")
      (value "0.1u_tant")
      (footprint "eagle-import:1206")
      (libsource (lib "eagle-import") (part "F93-XX-XXX-X-A"))
    )
    (comp (ref "U$90")
      (value "0.1u_tant")
      (footprint "eagle-import:1206")
      (libsource (lib "eagle-import") (part "F93-XX-XXX-X-A"))
    )
    (comp (ref "U$91")
      (value "0.1u_tant")
      (footprint "eagle-import:1206")
      (libsource (lib "eagle-import") (part "F93-XX-XXX-X-A"))
    )
    (comp (ref "U$92")
      (value "0.1u_tant")
      (footprint "eagle-import:1206")
      (libsource (lib "eagle-import") (part "F93-XX-XXX-X-A"))
    )
    (comp (ref "U$93")
      (value "0.1u_tant")
      (footprint "eagle-import:1206")
      (libsource (lib "eagle-import") (part "F93-XX-XXX-X-A"))
    )
    (comp (ref "U$94")
      (value "0.1u_tant")
      (footprint "eagle-import:1206")
      (libsource (lib "eagle-import") (part "F93-XX-XXX-X-A"))
    )
    (comp (ref "U$95")
      (value "0.1u_tant")
      (footprint "eagle-import:1206")
      (libsource (lib "eagle-import") (part "F93-XX-XXX-X-A"))
    )
    (comp (ref "U$96")
      (value "0.1u_tant")
      (footprint "eagle-import:1206")
      (libsource (lib "eagle-import") (part "F93-XX-XXX-X-A"))
    )
    (comp (ref "U$97")
      (value "0.1u_tant")
      (footprint "eagle-import:1206")
      (libsource (lib "eagle-import") (part "F93-XX-XXX-X-A"))
    )
    (comp (ref "U$98")
      (value "0.1u_tant")
      (footprint "eagle-import:1206")
      (libsource (lib "eagle-import") (part "F93-XX-XXX-X-A"))
    )
    (comp (ref "U$99")
      (value "0.1u_tant")
      (footprint "eagle-import:1206")
      (libsource (lib "eagle-import") (part "F93-XX-XXX-X-A"))
    )
    (comp (ref "U$100")
      (value "SYSTEM GROUND")
      (footprint "eagle-import:SUPERSABRE_8-PIN")
      (libsource (lib "eagle-import") (part "SUPERSABRE_8CIRCUIT"))
    )
    (comp (ref "U$101")
      (value "FERRITE_BEAD")
      (footprint "eagle-import:R0805")
      (libsource (lib "eagle-import") (part "FERRITE_BEAD"))
    )
    (comp (ref "U$102")
      (value "FERRITE_BEAD")
      (footprint "eagle-import:R0805")
      (libsource (lib "eagle-import") (part "FERRITE_BEAD"))
    )
    (comp (ref "U$103")
      (value "FERRITE_BEAD")
      (footprint "eagle-import:R0805")
      (libsource (lib "eagle-import") (part "FERRITE_BEAD"))
    )
    (comp (ref "U$104")
      (value "FERRITE_BEAD")
      (footprint "eagle-import:R0805")
      (libsource (lib "eagle-import") (part "FERRITE_BEAD"))
    )
    (comp (ref "U$105")
      (value "FERRITE_BEAD")
      (footprint "eagle-import:R0805")
      (libsource (lib "eagle-import") (part "FERRITE_BEAD"))
    )
    (comp (ref "U$106")
      (value "FERRITE_BEAD")
      (footprint "eagle-import:R0805")
      (libsource (lib "eagle-import") (part "FERRITE_BEAD"))
    )
    (comp (ref "U$107")
      (value "FERRITE_BEAD")
      (footprint "eagle-import:R0805")
      (libsource (lib "eagle-import") (part "FERRITE_BEAD"))
    )
    (comp (ref "U$108")
      (value "FERRITE_BEAD")
      (footprint "eagle-import:R0805")
      (libsource (lib "eagle-import") (part "FERRITE_BEAD"))
    )
    (comp (ref "U$109")
      (value "FERRITE_BEAD")
      (footprint "eagle-import:R0805")
      (libsource (lib "eagle-import") (part "FERRITE_BEAD"))
    )
    (comp (ref "U1")
      (value "TUSB2077ALQFP")
      (footprint "eagle-import:48-LQFP_0.5MM_PITCH")
      (libsource (lib "eagle-import") (part "TUSB2077ALQFP"))
    )
  )
  (nets
    (net (code "1") (name "/3V3") (class "Default")
      (node (ref "BATTERY-MUX") (pin "P$16") (pinfunction "VDD_P$16") (pintype "bidirectional"))
      (node (ref "C28") (pin "1") (pinfunction "1_1") (pintype "passive"))
      (node (ref "D13") (pin "C") (pinfunction "C_C") (pintype "passive"))
      (node (ref "D17") (pin "C") (pinfunction "C_C") (pintype "passive"))
      (node (ref "D21") (pin "C") (pinfunction "C_C") (pintype "passive"))
      (node (ref "D25") (pin "C") (pinfunction "C_C") (pintype "passive"))
      (node (ref "DVL_USB_HUB") (pin "P$10") (pinfunction "VDD33_P$10") (pintype "bidirectional"))
      (node (ref "DVL_USB_HUB") (pin "P$14") (pinfunction "VDD33_P$14") (pintype "bidirectional"))
      (node (ref "DVL_USB_HUB") (pin "P$18") (pinfunction "VBUS_DET_P$18") (pintype "bidirectional"))
      (node (ref "DVL_USB_HUB") (pin "P$20") (pinfunction "VDD33_P$20") (pintype "bidirectional"))
      (node (ref "DVL_USB_HUB") (pin "P$27") (pinfunction "VDD33_P$27") (pintype "bidirectional"))
      (node (ref "DVL_USB_HUB") (pin "P$4") (pinfunction "VDD33_P$4") (pintype "bidirectional"))
      (node (ref "JP1") (pin "18") (pinfunction "P$18_18") (pintype "bidirectional"))
      (node (ref "JP1") (pin "38") (pinfunction "P$38_38") (pintype "bidirectional"))
      (node (ref "JP1") (pin "58") (pinfunction "P$58_58") (pintype "bidirectional"))
      (node (ref "JP1") (pin "78") (pinfunction "P$78_78") (pintype "bidirectional"))
      (node (ref "JP2") (pin "18") (pinfunction "P$18_18") (pintype "bidirectional"))
      (node (ref "JP2") (pin "38") (pinfunction "P$38_38") (pintype "bidirectional"))
      (node (ref "JP2") (pin "58") (pinfunction "P$58_58") (pintype "bidirectional"))
      (node (ref "JP2") (pin "78") (pinfunction "P$78_78") (pintype "bidirectional"))
      (node (ref "JP3") (pin "18") (pinfunction "P$18_18") (pintype "bidirectional"))
      (node (ref "JP3") (pin "38") (pinfunction "P$38_38") (pintype "bidirectional"))
      (node (ref "JP3") (pin "58") (pinfunction "P$58_58") (pintype "bidirectional"))
      (node (ref "JP3") (pin "78") (pinfunction "P$78_78") (pintype "bidirectional"))
      (node (ref "JP4") (pin "18") (pinfunction "P$18_18") (pintype "bidirectional"))
      (node (ref "JP4") (pin "38") (pinfunction "P$38_38") (pintype "bidirectional"))
      (node (ref "JP4") (pin "58") (pinfunction "P$58_58") (pintype "bidirectional"))
      (node (ref "JP4") (pin "78") (pinfunction "P$78_78") (pintype "bidirectional"))
      (node (ref "LED10") (pin "A") (pinfunction "A_A") (pintype "passive"))
      (node (ref "LED12") (pin "A") (pinfunction "A_A") (pintype "passive"))
      (node (ref "LED14") (pin "A") (pinfunction "A_A") (pintype "passive"))
      (node (ref "LED8") (pin "A") (pinfunction "A_A") (pintype "passive"))
      (node (ref "R11") (pin "2") (pinfunction "2_2") (pintype "passive"))
      (node (ref "R62") (pin "1") (pinfunction "1_1") (pintype "passive"))
      (node (ref "R63") (pin "1") (pinfunction "1_1") (pintype "passive"))
      (node (ref "R64") (pin "1") (pinfunction "1_1") (pintype "passive"))
      (node (ref "R65") (pin "2") (pinfunction "2_2") (pintype "passive"))
      (node (ref "R66") (pin "2") (pinfunction "2_2") (pintype "passive"))
      (node (ref "R67") (pin "2") (pinfunction "2_2") (pintype "passive"))
      (node (ref "R68") (pin "2") (pinfunction "2_2") (pintype "passive"))
      (node (ref "R72") (pin "2") (pinfunction "2_2") (pintype "passive"))
      (node (ref "U$1") (pin "P$1") (pinfunction "EN_P$1") (pintype "bidirectional"))
      (node (ref "U$1") (pin "P$4") (pinfunction "VDD_P$4") (pintype "bidirectional"))
      (node (ref "U$29") (pin "P$4") (pinfunction "VCC_P$4") (pintype "bidirectional"))
      (node (ref "U$30") (pin "P$4") (pinfunction "VCC_P$4") (pintype "bidirectional"))
      (node (ref "U$31") (pin "P$4") (pinfunction "VCC_P$4") (pintype "bidirectional"))
      (node (ref "U$32") (pin "P$4") (pinfunction "VCC_P$4") (pintype "bidirectional"))
      (node (ref "U$33") (pin "P$1") (pinfunction "EN_P$1") (pintype "bidirectional"))
      (node (ref "U$33") (pin "P$4") (pinfunction "VDD_P$4") (pintype "bidirectional"))
      (node (ref "U$46") (pin "P$2") (pinfunction "VREF1_P$2") (pintype "bidirectional"))
      (node (ref "U$77") (pin "P$1") (pinfunction "+_P$1") (pintype "bidirectional"))
      (node (ref "U$81") (pin "P$1") (pinfunction "+_P$1") (pintype "bidirectional"))
      (node (ref "U$85") (pin "P$1") (pinfunction "+_P$1") (pintype "bidirectional"))
      (node (ref "U$89") (pin "P$1") (pinfunction "+_P$1") (pintype "bidirectional"))
      (node (ref "U1") (pin "P$10") (pinfunction "~{BUSPWR}_P$10") (pintype "bidirectional"))
      (node (ref "U1") (pin "P$12") (pinfunction "~{OVERCUR1}_P$12") (pintype "bidirectional"))
      (node (ref "U1") (pin "P$16") (pinfunction "~{OVERCUR2}_P$16") (pintype "bidirectional"))
      (node (ref "U1") (pin "P$20") (pinfunction "~{OVERCUR3}_P$20") (pintype "bidirectional"))
      (node (ref "U1") (pin "P$25") (pinfunction "~{OVERCUR4}_P$25") (pintype "bidirectional"))
      (node (ref "U1") (pin "P$46") (pinfunction "VCC_P$46") (pintype "bidirectional"))
      (node (ref "U1") (pin "P$47") (pinfunction "~{EXTMEM}_P$47") (pintype "bidirectional"))
      (node (ref "U1") (pin "P$48") (pinfunction "MODE_P$48") (pintype "bidirectional"))
      (node (ref "U1") (pin "P$6") (pinfunction "~{RESET}_P$6") (pintype "bidirectional"))
      (node (ref "U1") (pin "P$8") (pinfunction "EEDATA/~{GANGED}_P$8") (pintype "bidirectional"))
      (node (ref "U1") (pin "P$9") (pinfunction "VCC_P$9") (pintype "bidirectional"))
    )
    (net (code "2") (name "/5V") (class "Default")
      (node (ref "5.0") (pin "P$1") (pinfunction "P$1_P$1") (pintype "bidirectional"))
      (node (ref "5.0") (pin "P$2") (pinfunction "P$1_P$2") (pintype "bidirectional"))
      (node (ref "5.1") (pin "P$1") (pinfunction "P$1_P$1") (pintype "bidirectional"))
      (node (ref "5.1") (pin "P$2") (pinfunction "P$1_P$2") (pintype "bidirectional"))
      (node (ref "BATTERY-MUX") (pin "P$3") (pinfunction "~{RESET}_P$3") (pintype "bidirectional"))
      (node (ref "C10") (pin "1") (pinfunction "1_1") (pintype "passive"))
      (node (ref "C11") (pin "1") (pinfunction "1_1") (pintype "passive"))
      (node (ref "C16") (pin "1") (pinfunction "1_1") (pintype "passive"))
      (node (ref "C17") (pin "2") (pinfunction "2_2") (pintype "passive"))
      (node (ref "C29") (pin "1") (pinfunction "1_1") (pintype "passive"))
      (node (ref "C5") (pin "1") (pinfunction "1_1") (pintype "passive"))
      (node (ref "C6") (pin "1") (pinfunction "1_1") (pintype "passive"))
      (node (ref "C7") (pin "1") (pinfunction "1_1") (pintype "passive"))
      (node (ref "C9") (pin "1") (pinfunction "1_1") (pintype "passive"))
      (node (ref "D10") (pin "C") (pinfunction "C_C") (pintype "passive"))
      (node (ref "D12") (pin "C") (pinfunction "C_C") (pintype "passive"))
      (node (ref "D16") (pin "C") (pinfunction "C_C") (pintype "passive"))
      (node (ref "D2") (pin "C") (pinfunction "C_C") (pintype "passive"))
      (node (ref "D20") (pin "C") (pinfunction "C_C") (pintype "passive"))
      (node (ref "D24") (pin "C") (pinfunction "C_C") (pintype "passive"))
      (node (ref "D3") (pin "C") (pinfunction "C_C") (pintype "passive"))
      (node (ref "D36") (pin "C") (pinfunction "C_C") (pintype "passive"))
      (node (ref "D37") (pin "C") (pinfunction "C_C") (pintype "passive"))
      (node (ref "DVL_HOST_FTDI") (pin "1") (pinfunction "VCCIO_1") (pintype "power_in"))
      (node (ref "DVL_HOST_FTDI") (pin "18") (pinfunction "~{RESET}_18") (pintype "input"))
      (node (ref "DVL_HOST_FTDI") (pin "19") (pinfunction "VCC_19") (pintype "power_in"))
      (node (ref "DVL_SLAVE_FTDI") (pin "1") (pinfunction "VCCIO_1") (pintype "power_in"))
      (node (ref "DVL_SLAVE_FTDI") (pin "18") (pinfunction "~{RESET}_18") (pintype "input"))
      (node (ref "DVL_SLAVE_FTDI") (pin "19") (pinfunction "VCC_19") (pintype "power_in"))
      (node (ref "DVL_TTL-TO-RS232") (pin "11") (pinfunction "VCC_11") (pintype "bidirectional"))
      (node (ref "DVL_TTL-TO-RS232") (pin "24") (pinfunction "EN_24") (pintype "bidirectional"))
      (node (ref "DVL_TTL-TO-RS232") (pin "25") (pinfunction "~{SHDN}_25") (pintype "bidirectional"))
      (node (ref "G1") (pin "IN1") (pinfunction "IN1_IN1") (pintype "bidirectional"))
      (node (ref "G1") (pin "IN2") (pinfunction "IN2_IN2") (pintype "bidirectional"))
      (node (ref "JP1") (pin "17") (pinfunction "P$17_17") (pintype "bidirectional"))
      (node (ref "JP1") (pin "37") (pinfunction "P$37_37") (pintype "bidirectional"))
      (node (ref "JP1") (pin "57") (pinfunction "P$57_57") (pintype "bidirectional"))
      (node (ref "JP1") (pin "77") (pinfunction "P$77_77") (pintype "bidirectional"))
      (node (ref "JP2") (pin "17") (pinfunction "P$17_17") (pintype "bidirectional"))
      (node (ref "JP2") (pin "37") (pinfunction "P$37_37") (pintype "bidirectional"))
      (node (ref "JP2") (pin "57") (pinfunction "P$57_57") (pintype "bidirectional"))
      (node (ref "JP2") (pin "77") (pinfunction "P$77_77") (pintype "bidirectional"))
      (node (ref "JP3") (pin "17") (pinfunction "P$17_17") (pintype "bidirectional"))
      (node (ref "JP3") (pin "37") (pinfunction "P$37_37") (pintype "bidirectional"))
      (node (ref "JP3") (pin "57") (pinfunction "P$57_57") (pintype "bidirectional"))
      (node (ref "JP3") (pin "77") (pinfunction "P$77_77") (pintype "bidirectional"))
      (node (ref "JP4") (pin "17") (pinfunction "P$17_17") (pintype "bidirectional"))
      (node (ref "JP4") (pin "37") (pinfunction "P$37_37") (pintype "bidirectional"))
      (node (ref "JP4") (pin "57") (pinfunction "P$57_57") (pintype "bidirectional"))
      (node (ref "JP4") (pin "77") (pinfunction "P$77_77") (pintype "bidirectional"))
      (node (ref "R1") (pin "2") (pinfunction "2_2") (pintype "passive"))
      (node (ref "R4") (pin "2") (pinfunction "2_2") (pintype "passive"))
      (node (ref "R5") (pin "2") (pinfunction "2_2") (pintype "passive"))
      (node (ref "R6") (pin "2") (pinfunction "2_2") (pintype "passive"))
      (node (ref "R7") (pin "2") (pinfunction "2_2") (pintype "passive"))
      (node (ref "R8") (pin "1") (pinfunction "1_1") (pintype "passive"))
      (node (ref "R9") (pin "1") (pinfunction "1_1") (pintype "passive"))
      (node (ref "U$108") (pin "1") (pinfunction "P$1_1") (pintype "bidirectional"))
      (node (ref "U$11") (pin "P$2") (pinfunction "P$2_P$2") (pintype "bidirectional"))
      (node (ref "U$12") (pin "P$1") (pinfunction "+_P$1") (pintype "bidirectional"))
      (node (ref "U$17") (pin "1") (pinfunction "P$1_1") (pintype "bidirectional"))
      (node (ref "U$18") (pin "P$4") (pinfunction "VCC_P$4") (pintype "bidirectional"))
      (node (ref "U$19") (pin "P$4") (pinfunction "VCC_P$4") (pintype "bidirectional"))
      (node (ref "U$2") (pin "P$4") (pinfunction "VCC_P$4") (pintype "bidirectional"))
      (node (ref "U$20") (pin "P$4") (pinfunction "VCC_P$4") (pintype "bidirectional"))
      (node (ref "U$22") (pin "P$4") (pinfunction "VCC_P$4") (pintype "bidirectional"))
      (node (ref "U$23") (pin "P$4") (pinfunction "VCC_P$4") (pintype "bidirectional"))
      (node (ref "U$27") (pin "P$4") (pinfunction "VCC_P$4") (pintype "bidirectional"))
      (node (ref "U$28") (pin "P$4") (pinfunction "VCC_P$4") (pintype "bidirectional"))
      (node (ref "U$3") (pin "P$4") (pinfunction "VCC_P$4") (pintype "bidirectional"))
      (node (ref "U$37") (pin "8") (pinfunction "VCC_8") (pintype "bidirectional"))
      (node (ref "U$38") (pin "8") (pinfunction "VCC_8") (pintype "bidirectional"))
      (node (ref "U$39") (pin "8") (pinfunction "VCC_8") (pintype "bidirectional"))
      (node (ref "U$4") (pin "P$4") (pinfunction "VCC_P$4") (pintype "bidirectional"))
      (node (ref "U$40") (pin "8") (pinfunction "VCC_8") (pintype "bidirectional"))
      (node (ref "U$42") (pin "P$4") (pinfunction "VCC_P$4") (pintype "bidirectional"))
      (node (ref "U$44") (pin "P$2") (pinfunction "P$2_P$2") (pintype "bidirectional"))
      (node (ref "U$45") (pin "P$1") (pinfunction "+_P$1") (pintype "bidirectional"))
      (node (ref "U$48") (pin "P$2") (pinfunction "P$2_P$2") (pintype "bidirectional"))
      (node (ref "U$49") (pin "P$1") (pinfunction "+_P$1") (pintype "bidirectional"))
      (node (ref "U$5") (pin "P$4") (pinfunction "VCC_P$4") (pintype "bidirectional"))
      (node (ref "U$50") (pin "8") (pinfunction "VCC_8") (pintype "bidirectional"))
      (node (ref "U$52") (pin "P$4") (pinfunction "VCC_P$4") (pintype "bidirectional"))
      (node (ref "U$53") (pin "P$4") (pinfunction "VCC_P$4") (pintype "bidirectional"))
      (node (ref "U$54") (pin "P$4") (pinfunction "VCC_P$4") (pintype "bidirectional"))
      (node (ref "U$55") (pin "P$4") (pinfunction "VCC_P$4") (pintype "bidirectional"))
      (node (ref "U$56") (pin "P$4") (pinfunction "VCC_P$4") (pintype "bidirectional"))
      (node (ref "U$57") (pin "P$4") (pinfunction "VCC_P$4") (pintype "bidirectional"))
      (node (ref "U$58") (pin "P$4") (pinfunction "VCC_P$4") (pintype "bidirectional"))
      (node (ref "U$59") (pin "P$4") (pinfunction "VCC_P$4") (pintype "bidirectional"))
      (node (ref "U$6") (pin "P$4") (pinfunction "VCC_P$4") (pintype "bidirectional"))
      (node (ref "U$60") (pin "P$4") (pinfunction "VCC_P$4") (pintype "bidirectional"))
      (node (ref "U$61") (pin "P$4") (pinfunction "VCC_P$4") (pintype "bidirectional"))
      (node (ref "U$62") (pin "P$4") (pinfunction "VCC_P$4") (pintype "bidirectional"))
      (node (ref "U$63") (pin "P$4") (pinfunction "VCC_P$4") (pintype "bidirectional"))
      (node (ref "U$7") (pin "P$4") (pinfunction "VCC_P$4") (pintype "bidirectional"))
      (node (ref "U$70") (pin "P$1") (pinfunction "+_P$1") (pintype "bidirectional"))
      (node (ref "U$71") (pin "P$1") (pinfunction "+_P$1") (pintype "bidirectional"))
      (node (ref "U$74") (pin "1") (pinfunction "P$1_1") (pintype "bidirectional"))
      (node (ref "U$76") (pin "P$1") (pinfunction "+_P$1") (pintype "bidirectional"))
      (node (ref "U$8") (pin "P$4") (pinfunction "VCC_P$4") (pintype "bidirectional"))
      (node (ref "U$80") (pin "P$1") (pinfunction "+_P$1") (pintype "bidirectional"))
      (node (ref "U$84") (pin "P$1") (pinfunction "+_P$1") (pintype "bidirectional"))
      (node (ref "U$88") (pin "P$1") (pinfunction "+_P$1") (pintype "bidirectional"))
      (node (ref "U$9") (pin "P$4") (pinfunction "VCC_P$4") (pintype "bidirectional"))
    )
    (net (code "3") (name "/12V") (class "Default")
      (node (ref "2PIN_4") (pin "P$1") (pinfunction "P$1_P$1") (pintype "bidirectional"))
      (node (ref "5.1") (pin "P$10") (pinfunction "P$5_P$10") (pintype "bidirectional"))
      (node (ref "5.1") (pin "P$3") (pinfunction "P$2_P$3") (pintype "bidirectional"))
      (node (ref "5.1") (pin "P$4") (pinfunction "P$2_P$4") (pintype "bidirectional"))
      (node (ref "5.1") (pin "P$5") (pinfunction "P$3_P$5") (pintype "bidirectional"))
      (node (ref "5.1") (pin "P$6") (pinfunction "P$3_P$6") (pintype "bidirectional"))
      (node (ref "5.1") (pin "P$7") (pinfunction "P$4_P$7") (pintype "bidirectional"))
      (node (ref "5.1") (pin "P$8") (pinfunction "P$4_P$8") (pintype "bidirectional"))
      (node (ref "5.1") (pin "P$9") (pinfunction "P$5_P$9") (pintype "bidirectional"))
      (node (ref "D11") (pin "C") (pinfunction "C_C") (pintype "passive"))
      (node (ref "D15") (pin "C") (pinfunction "C_C") (pintype "passive"))
      (node (ref "D19") (pin "C") (pinfunction "C_C") (pintype "passive"))
      (node (ref "D23") (pin "C") (pinfunction "C_C") (pintype "passive"))
      (node (ref "D27") (pin "C") (pinfunction "C_C") (pintype "passive"))
      (node (ref "D4") (pin "C") (pinfunction "C_C") (pintype "passive"))
      (node (ref "D5") (pin "C") (pinfunction "C_C") (pintype "passive"))
      (node (ref "D6") (pin "C") (pinfunction "C_C") (pintype "passive"))
      (node (ref "D7") (pin "C") (pinfunction "C_C") (pintype "passive"))
      (node (ref "JP1") (pin "16") (pinfunction "P$16_16") (pintype "bidirectional"))
      (node (ref "JP1") (pin "36") (pinfunction "P$36_36") (pintype "bidirectional"))
      (node (ref "JP1") (pin "56") (pinfunction "P$56_56") (pintype "bidirectional"))
      (node (ref "JP1") (pin "76") (pinfunction "P$76_76") (pintype "bidirectional"))
      (node (ref "JP2") (pin "16") (pinfunction "P$16_16") (pintype "bidirectional"))
      (node (ref "JP2") (pin "36") (pinfunction "P$36_36") (pintype "bidirectional"))
      (node (ref "JP2") (pin "56") (pinfunction "P$56_56") (pintype "bidirectional"))
      (node (ref "JP2") (pin "76") (pinfunction "P$76_76") (pintype "bidirectional"))
      (node (ref "JP3") (pin "16") (pinfunction "P$16_16") (pintype "bidirectional"))
      (node (ref "JP3") (pin "36") (pinfunction "P$36_36") (pintype "bidirectional"))
      (node (ref "JP3") (pin "56") (pinfunction "P$56_56") (pintype "bidirectional"))
      (node (ref "JP3") (pin "76") (pinfunction "P$76_76") (pintype "bidirectional"))
      (node (ref "JP4") (pin "16") (pinfunction "P$16_16") (pintype "bidirectional"))
      (node (ref "JP4") (pin "36") (pinfunction "P$36_36") (pintype "bidirectional"))
      (node (ref "JP4") (pin "56") (pinfunction "P$56_56") (pintype "bidirectional"))
      (node (ref "JP4") (pin "76") (pinfunction "P$76_76") (pintype "bidirectional"))
      (node (ref "U$15") (pin "P$2") (pinfunction "P$2_P$2") (pintype "bidirectional"))
      (node (ref "U$64") (pin "P$1") (pinfunction "+_P$1") (pintype "bidirectional"))
      (node (ref "U$65") (pin "P$1") (pinfunction "+_P$1") (pintype "bidirectional"))
      (node (ref "U$66") (pin "P$1") (pinfunction "+_P$1") (pintype "bidirectional"))
      (node (ref "U$67") (pin "P$1") (pinfunction "+_P$1") (pintype "bidirectional"))
      (node (ref "U$75") (pin "P$1") (pinfunction "+_P$1") (pintype "bidirectional"))
      (node (ref "U$79") (pin "P$1") (pinfunction "+_P$1") (pintype "bidirectional"))
      (node (ref "U$83") (pin "P$1") (pinfunction "+_P$1") (pintype "bidirectional"))
      (node (ref "U$87") (pin "P$1") (pinfunction "+_P$1") (pintype "bidirectional"))
      (node (ref "U$91") (pin "P$1") (pinfunction "+_P$1") (pintype "bidirectional"))
    )
    (net (code "4") (name "/ACT-PWR_POST-KILL") (class "Default")
      (node (ref "ACT-PWR_OUT") (pin "P$1") (pinfunction "P$1_P$1") (pintype "bidirectional"))
      (node (ref "ACT-PWR_OUT") (pin "P$2") (pinfunction "P$2_P$2") (pintype "bidirectional"))
      (node (ref "D8") (pin "C") (pinfunction "C_C") (pintype "passive"))
      (node (ref "U$41") (pin "DRAIN") (pinfunction "P$2_DRAIN") (pintype "bidirectional"))
      (node (ref "U$72") (pin "P$1") (pinfunction "+_P$1") (pintype "bidirectional"))
    )
    (net (code "5") (name "/ACT-PWR_PRE-KILL") (class "Default")
      (node (ref "ACT-PWR_IN") (pin "P$1") (pinfunction "P$1_P$1") (pintype "bidirectional"))
      (node (ref "ACT-PWR_IN") (pin "P$2") (pinfunction "P$2_P$2") (pintype "bidirectional"))
      (node (ref "D1") (pin "C") (pinfunction "C_C") (pintype "passive"))
      (node (ref "D9") (pin "C") (pinfunction "C_C") (pintype "passive"))
      (node (ref "R61") (pin "2") (pinfunction "2_2") (pintype "passive"))
      (node (ref "U$41") (pin "S1") (pinfunction "P$1_S1") (pintype "bidirectional"))
      (node (ref "U$41") (pin "S2") (pinfunction "P$1_S2") (pintype "bidirectional"))
      (node (ref "U$41") (pin "S3") (pinfunction "P$1_S3") (pintype "bidirectional"))
      (node (ref "U$41") (pin "S4") (pinfunction "P$1_S4") (pintype "bidirectional"))
      (node (ref "U$41") (pin "S5") (pinfunction "P$1_S5") (pintype "bidirectional"))
      (node (ref "U$73") (pin "P$1") (pinfunction "+_P$1") (pintype "bidirectional"))
    )
    (net (code "6") (name "/ACT_SCL") (class "Default")
      (node (ref "5.4") (pin "P$1") (pinfunction "P$1_P$1") (pintype "bidirectional"))
      (node (ref "5.4") (pin "P$2") (pinfunction "P$1_P$2") (pintype "bidirectional"))
      (node (ref "JP1") (pin "24") (pinfunction "P$24_24") (pintype "bidirectional"))
      (node (ref "JP2") (pin "24") (pinfunction "P$24_24") (pintype "bidirectional"))
      (node (ref "JP3") (pin "24") (pinfunction "P$24_24") (pintype "bidirectional"))
      (node (ref "JP4") (pin "24") (pinfunction "P$24_24") (pintype "bidirectional"))
      (node (ref "U$63") (pin "P$2") (pinfunction "I/O_1_P$2") (pintype "bidirectional"))
    )
    (net (code "7") (name "/ACT_SDA") (class "Default")
      (node (ref "5.5") (pin "P$1") (pinfunction "P$1_P$1") (pintype "bidirectional"))
      (node (ref "5.5") (pin "P$2") (pinfunction "P$1_P$2") (pintype "bidirectional"))
      (node (ref "JP1") (pin "23") (pinfunction "P$23_23") (pintype "bidirectional"))
      (node (ref "JP2") (pin "23") (pinfunction "P$23_23") (pintype "bidirectional"))
      (node (ref "JP3") (pin "23") (pinfunction "P$23_23") (pintype "bidirectional"))
      (node (ref "JP4") (pin "23") (pinfunction "P$23_23") (pintype "bidirectional"))
      (node (ref "U$63") (pin "P$3") (pinfunction "I/O_2_P$3") (pintype "bidirectional"))
    )
    (net (code "8") (name "/AHRS_USB_N") (class "Default")
      (node (ref "2PIN_2") (pin "P$2") (pinfunction "P$2_P$2") (pintype "bidirectional"))
      (node (ref "U$42") (pin "P$3") (pinfunction "I/O_2_P$3") (pintype "bidirectional"))
      (node (ref "U$43") (pin "D+") (pinfunction "3_D+") (pintype "bidirectional"))
      (node (ref "U$6") (pin "P$3") (pinfunction "I/O_2_P$3") (pintype "bidirectional"))
    )
    (net (code "9") (name "/AHRS_USB_P") (class "Default")
      (node (ref "2PIN_2") (pin "P$1") (pinfunction "P$1_P$1") (pintype "bidirectional"))
      (node (ref "U$42") (pin "P$2") (pinfunction "I/O_1_P$2") (pintype "bidirectional"))
      (node (ref "U$43") (pin "D-") (pinfunction "2_D-") (pintype "bidirectional"))
      (node (ref "U$6") (pin "P$2") (pinfunction "I/O_1_P$2") (pintype "bidirectional"))
    )
    (net (code "10") (name "/BATT1_SCL") (class "Default")
      (node (ref "5.4") (pin "P$3") (pinfunction "P$2_P$3") (pintype "bidirectional"))
      (node (ref "5.4") (pin "P$4") (pinfunction "P$2_P$4") (pintype "bidirectional"))
      (node (ref "U$39") (pin "7") (pinfunction "LY_7") (pintype "bidirectional"))
      (node (ref "U$62") (pin "P$2") (pinfunction "I/O_1_P$2") (pintype "bidirectional"))
    )
    (net (code "11") (name "/BATT1_SCL_UNBUF") (class "Default")
      (node (ref "BATTERY-MUX") (pin "P$7") (pinfunction "SC1_P$7") (pintype "bidirectional"))
      (node (ref "U$39") (pin "6") (pinfunction "SY_6") (pintype "bidirectional"))
    )
    (net (code "12") (name "/BATT1_SDA") (class "Default")
      (node (ref "5.5") (pin "P$3") (pinfunction "P$2_P$3") (pintype "bidirectional"))
      (node (ref "5.5") (pin "P$4") (pinfunction "P$2_P$4") (pintype "bidirectional"))
      (node (ref "U$39") (pin "2") (pinfunction "LX_2") (pintype "bidirectional"))
      (node (ref "U$62") (pin "P$3") (pinfunction "I/O_2_P$3") (pintype "bidirectional"))
    )
    (net (code "13") (name "/BATT1_SDA_UNBUF") (class "Default")
      (node (ref "BATTERY-MUX") (pin "P$6") (pinfunction "SD1_P$6") (pintype "bidirectional"))
      (node (ref "U$39") (pin "3") (pinfunction "SX_3") (pintype "bidirectional"))
    )
    (net (code "14") (name "/BATT2_SCL") (class "Default")
      (node (ref "5.4") (pin "P$5") (pinfunction "P$3_P$5") (pintype "bidirectional"))
      (node (ref "5.4") (pin "P$6") (pinfunction "P$3_P$6") (pintype "bidirectional"))
      (node (ref "U$37") (pin "7") (pinfunction "LY_7") (pintype "bidirectional"))
      (node (ref "U$61") (pin "P$2") (pinfunction "I/O_1_P$2") (pintype "bidirectional"))
    )
    (net (code "15") (name "/BATT2_SCL_UNBUF") (class "Default")
      (node (ref "BATTERY-MUX") (pin "P$10") (pinfunction "SC2_P$10") (pintype "bidirectional"))
      (node (ref "U$37") (pin "6") (pinfunction "SY_6") (pintype "bidirectional"))
    )
    (net (code "16") (name "/BATT2_SDA") (class "Default")
      (node (ref "5.5") (pin "P$5") (pinfunction "P$3_P$5") (pintype "bidirectional"))
      (node (ref "5.5") (pin "P$6") (pinfunction "P$3_P$6") (pintype "bidirectional"))
      (node (ref "U$37") (pin "2") (pinfunction "LX_2") (pintype "bidirectional"))
      (node (ref "U$61") (pin "P$3") (pinfunction "I/O_2_P$3") (pintype "bidirectional"))
    )
    (net (code "17") (name "/BATT2_SDA_UNBUF") (class "Default")
      (node (ref "BATTERY-MUX") (pin "P$9") (pinfunction "SD2_P$9") (pintype "bidirectional"))
      (node (ref "U$37") (pin "3") (pinfunction "SX_3") (pintype "bidirectional"))
    )
    (net (code "18") (name "/BATT_SCL") (class "Default")
      (node (ref "JP1") (pin "44") (pinfunction "P$44_44") (pintype "bidirectional"))
      (node (ref "JP2") (pin "44") (pinfunction "P$44_44") (pintype "bidirectional"))
      (node (ref "JP3") (pin "44") (pinfunction "P$44_44") (pintype "bidirectional"))
      (node (ref "JP4") (pin "44") (pinfunction "P$44_44") (pintype "bidirectional"))
      (node (ref "U$38") (pin "2") (pinfunction "LX_2") (pintype "bidirectional"))
    )
    (net (code "19") (name "/BATT_SCL_UNBUF") (class "Default")
      (node (ref "BATTERY-MUX") (pin "P$14") (pinfunction "SCL_P$14") (pintype "bidirectional"))
      (node (ref "U$38") (pin "3") (pinfunction "SX_3") (pintype "bidirectional"))
    )
    (net (code "20") (name "/BATT_SDA") (class "Default")
      (node (ref "JP1") (pin "43") (pinfunction "P$43_43") (pintype "bidirectional"))
      (node (ref "JP2") (pin "43") (pinfunction "P$43_43") (pintype "bidirectional"))
      (node (ref "JP3") (pin "43") (pinfunction "P$43_43") (pintype "bidirectional"))
      (node (ref "JP4") (pin "43") (pinfunction "P$43_43") (pintype "bidirectional"))
      (node (ref "U$38") (pin "7") (pinfunction "LY_7") (pintype "bidirectional"))
    )
    (net (code "21") (name "/BATT_SDA_UNBUF") (class "Default")
      (node (ref "BATTERY-MUX") (pin "P$15") (pinfunction "SDA_P$15") (pintype "bidirectional"))
      (node (ref "U$38") (pin "6") (pinfunction "SY_6") (pintype "bidirectional"))
    )
    (net (code "22") (name "/CANH") (class "Default")
      (node (ref "2PIN_7") (pin "P$2") (pinfunction "P$2_P$2") (pintype "bidirectional"))
      (node (ref "5.3") (pin "P$10") (pinfunction "P$5_P$10") (pintype "bidirectional"))
      (node (ref "5.3") (pin "P$9") (pinfunction "P$5_P$9") (pintype "bidirectional"))
      (node (ref "JP1") (pin "45") (pinfunction "P$45_45") (pintype "bidirectional"))
      (node (ref "JP2") (pin "45") (pinfunction "P$45_45") (pintype "bidirectional"))
      (node (ref "JP3") (pin "45") (pinfunction "P$45_45") (pintype "bidirectional"))
      (node (ref "JP4") (pin "45") (pinfunction "P$45_45") (pintype "bidirectional"))
      (node (ref "U$20") (pin "P$3") (pinfunction "I/O_2_P$3") (pintype "bidirectional"))
      (node (ref "U$53") (pin "P$3") (pinfunction "I/O_2_P$3") (pintype "bidirectional"))
    )
    (net (code "23") (name "/CANL") (class "Default")
      (node (ref "2PIN_7") (pin "P$1") (pinfunction "P$1_P$1") (pintype "bidirectional"))
      (node (ref "5.3") (pin "P$7") (pinfunction "P$4_P$7") (pintype "bidirectional"))
      (node (ref "5.3") (pin "P$8") (pinfunction "P$4_P$8") (pintype "bidirectional"))
      (node (ref "JP1") (pin "46") (pinfunction "P$46_46") (pintype "bidirectional"))
      (node (ref "JP2") (pin "46") (pinfunction "P$46_46") (pintype "bidirectional"))
      (node (ref "JP3") (pin "46") (pinfunction "P$46_46") (pintype "bidirectional"))
      (node (ref "JP4") (pin "46") (pinfunction "P$46_46") (pintype "bidirectional"))
      (node (ref "U$20") (pin "P$2") (pinfunction "I/O_1_P$2") (pintype "bidirectional"))
      (node (ref "U$53") (pin "P$2") (pinfunction "I/O_1_P$2") (pintype "bidirectional"))
    )
    (net (code "24") (name "/CE_2") (class "Default")
      (node (ref "JP1") (pin "52") (pinfunction "P$52_52") (pintype "bidirectional"))
      (node (ref "JP2") (pin "52") (pinfunction "P$52_52") (pintype "bidirectional"))
      (node (ref "JP3") (pin "52") (pinfunction "P$52_52") (pintype "bidirectional"))
      (node (ref "JP4") (pin "52") (pinfunction "P$52_52") (pintype "bidirectional"))
    )
    (net (code "25") (name "/CE_3") (class "Default")
      (node (ref "JP1") (pin "53") (pinfunction "P$53_53") (pintype "bidirectional"))
      (node (ref "JP2") (pin "53") (pinfunction "P$53_53") (pintype "bidirectional"))
      (node (ref "JP3") (pin "53") (pinfunction "P$53_53") (pintype "bidirectional"))
      (node (ref "JP4") (pin "53") (pinfunction "P$53_53") (pintype "bidirectional"))
    )
    (net (code "26") (name "/CE_4") (class "Default")
      (node (ref "JP1") (pin "54") (pinfunction "P$54_54") (pintype "bidirectional"))
      (node (ref "JP2") (pin "54") (pinfunction "P$54_54") (pintype "bidirectional"))
      (node (ref "JP3") (pin "54") (pinfunction "P$54_54") (pintype "bidirectional"))
      (node (ref "JP4") (pin "54") (pinfunction "P$54_54") (pintype "bidirectional"))
    )
    (net (code "27") (name "/CE_CPU") (class "Default")
      (node (ref "4PIN_7") (pin "P$2") (pinfunction "P$2_P$2") (pintype "bidirectional"))
      (node (ref "JP1") (pin "74") (pinfunction "P$74_74") (pintype "bidirectional"))
      (node (ref "JP2") (pin "74") (pinfunction "P$74_74") (pintype "bidirectional"))
      (node (ref "JP3") (pin "74") (pinfunction "P$74_74") (pintype "bidirectional"))
      (node (ref "JP4") (pin "74") (pinfunction "P$74_74") (pintype "bidirectional"))
    )
    (net (code "28") (name "/CE_LEDS") (class "Default")
      (node (ref "JP1") (pin "73") (pinfunction "P$73_73") (pintype "bidirectional"))
      (node (ref "JP2") (pin "73") (pinfunction "P$73_73") (pintype "bidirectional"))
      (node (ref "JP3") (pin "73") (pinfunction "P$73_73") (pintype "bidirectional"))
      (node (ref "JP4") (pin "73") (pinfunction "P$73_73") (pintype "bidirectional"))
      (node (ref "U$15") (pin "P$3") (pinfunction "P$3_P$3") (pintype "bidirectional"))
      (node (ref "U$28") (pin "P$3") (pinfunction "I/O_2_P$3") (pintype "bidirectional"))
    )
    (net (code "29") (name "/CTS_CF") (class "Default")
      (node (ref "4PIN_2") (pin "P$1") (pinfunction "P$1_P$1") (pintype "bidirectional"))
      (node (ref "JP1") (pin "13") (pinfunction "P$13_13") (pintype "bidirectional"))
      (node (ref "JP2") (pin "13") (pinfunction "P$13_13") (pintype "bidirectional"))
      (node (ref "JP3") (pin "13") (pinfunction "P$13_13") (pintype "bidirectional"))
      (node (ref "JP4") (pin "13") (pinfunction "P$13_13") (pintype "bidirectional"))
    )
    (net (code "30") (name "/CTS_MC") (class "Default")
      (node (ref "4PIN_1") (pin "P$1") (pinfunction "P$1_P$1") (pintype "bidirectional"))
      (node (ref "JP1") (pin "29") (pinfunction "P$29_29") (pintype "bidirectional"))
      (node (ref "JP2") (pin "29") (pinfunction "P$29_29") (pintype "bidirectional"))
      (node (ref "JP3") (pin "29") (pinfunction "P$29_29") (pintype "bidirectional"))
      (node (ref "JP4") (pin "29") (pinfunction "P$29_29") (pintype "bidirectional"))
    )
    (net (code "31") (name "/CTS_MD") (class "Default")
      (node (ref "5.2") (pin "P$5") (pinfunction "P$3_P$5") (pintype "bidirectional"))
      (node (ref "5.2") (pin "P$6") (pinfunction "P$3_P$6") (pintype "bidirectional"))
      (node (ref "JP1") (pin "68") (pinfunction "P$68_68") (pintype "bidirectional"))
      (node (ref "JP2") (pin "68") (pinfunction "P$68_68") (pintype "bidirectional"))
      (node (ref "JP3") (pin "68") (pinfunction "P$68_68") (pintype "bidirectional"))
      (node (ref "JP4") (pin "68") (pinfunction "P$68_68") (pintype "bidirectional"))
      (node (ref "U$55") (pin "P$3") (pinfunction "I/O_2_P$3") (pintype "bidirectional"))
    )
    (net (code "32") (name "/CTS_MF") (class "Default")
      (node (ref "JP1") (pin "5") (pinfunction "P$5_5") (pintype "bidirectional"))
      (node (ref "JP2") (pin "5") (pinfunction "P$5_5") (pintype "bidirectional"))
      (node (ref "JP3") (pin "5") (pinfunction "P$5_5") (pintype "bidirectional"))
      (node (ref "JP4") (pin "5") (pinfunction "P$5_5") (pintype "bidirectional"))
    )
    (net (code "33") (name "/CTS_PF") (class "Default")
      (node (ref "JP1") (pin "9") (pinfunction "P$9_9") (pintype "bidirectional"))
      (node (ref "JP2") (pin "9") (pinfunction "P$9_9") (pintype "bidirectional"))
      (node (ref "JP3") (pin "9") (pinfunction "P$9_9") (pintype "bidirectional"))
      (node (ref "JP4") (pin "9") (pinfunction "P$9_9") (pintype "bidirectional"))
    )
    (net (code "34") (name "/CTS_SF") (class "Default")
      (node (ref "JP1") (pin "50") (pinfunction "P$50_50") (pintype "bidirectional"))
      (node (ref "JP2") (pin "50") (pinfunction "P$50_50") (pintype "bidirectional"))
      (node (ref "JP3") (pin "50") (pinfunction "P$50_50") (pintype "bidirectional"))
      (node (ref "JP4") (pin "50") (pinfunction "P$50_50") (pintype "bidirectional"))
    )
    (net (code "35") (name "/DEPTH_SCL") (class "Default")
      (node (ref "R62") (pin "2") (pinfunction "2_2") (pintype "passive"))
      (node (ref "U$46") (pin "P$3") (pinfunction "SCL1_P$3") (pintype "bidirectional"))
      (node (ref "U$47") (pin "P$2") (pinfunction "2_P$2") (pintype "bidirectional"))
    )
    (net (code "36") (name "/DEPTH_SDA") (class "Default")
      (node (ref "R63") (pin "2") (pinfunction "2_2") (pintype "passive"))
      (node (ref "U$46") (pin "P$4") (pinfunction "SDA1_P$4") (pintype "bidirectional"))
      (node (ref "U$47") (pin "P$3") (pinfunction "3_P$3") (pintype "bidirectional"))
    )
    (net (code "37") (name "/DVL_HCTS") (class "Default")
      (node (ref "5.6") (pin "P$3") (pinfunction "P$2_P$3") (pintype "bidirectional"))
      (node (ref "5.6") (pin "P$4") (pinfunction "P$2_P$4") (pintype "bidirectional"))
      (node (ref "DVL_TTL-TO-RS232") (pin "4") (pinfunction "RIN2_4") (pintype "bidirectional"))
      (node (ref "U$58") (pin "P$3") (pinfunction "I/O_2_P$3") (pintype "bidirectional"))
    )
    (net (code "38") (name "/DVL_HRTS") (class "Default")
      (node (ref "5.6") (pin "P$5") (pinfunction "P$3_P$5") (pintype "bidirectional"))
      (node (ref "5.6") (pin "P$6") (pinfunction "P$3_P$6") (pintype "bidirectional"))
      (node (ref "DVL_TTL-TO-RS232") (pin "1") (pinfunction "DOUT3_1") (pintype "bidirectional"))
      (node (ref "U$57") (pin "P$2") (pinfunction "I/O_1_P$2") (pintype "bidirectional"))
    )
    (net (code "39") (name "/DVL_HRX") (class "Default")
      (node (ref "5.6") (pin "P$10") (pinfunction "P$5_P$10") (pintype "bidirectional"))
      (node (ref "5.6") (pin "P$9") (pinfunction "P$5_P$9") (pintype "bidirectional"))
      (node (ref "DVL_TTL-TO-RS232") (pin "9") (pinfunction "RIN1_9") (pintype "bidirectional"))
      (node (ref "U$56") (pin "P$3") (pinfunction "I/O_2_P$3") (pintype "bidirectional"))
    )
    (net (code "40") (name "/DVL_HRXD") (class "Default")
      (node (ref "DVL_HOST_FTDI") (pin "2") (pinfunction "RXD_2") (pintype "input"))
      (node (ref "DVL_TTL-TO-RS232") (pin "8") (pinfunction "ROUT1_8") (pintype "bidirectional"))
    )
    (net (code "41") (name "/DVL_HTX") (class "Default")
      (node (ref "5.6") (pin "P$7") (pinfunction "P$4_P$7") (pintype "bidirectional"))
      (node (ref "5.6") (pin "P$8") (pinfunction "P$4_P$8") (pintype "bidirectional"))
      (node (ref "DVL_TTL-TO-RS232") (pin "2") (pinfunction "DOUT1_2") (pintype "bidirectional"))
      (node (ref "U$57") (pin "P$3") (pinfunction "I/O_2_P$3") (pintype "bidirectional"))
    )
    (net (code "42") (name "/DVL_HTXD") (class "Default")
      (node (ref "DVL_HOST_FTDI") (pin "30") (pinfunction "TXD_30") (pintype "output"))
      (node (ref "DVL_TTL-TO-RS232") (pin "7") (pinfunction "DIN1_7") (pintype "bidirectional"))
    )
    (net (code "43") (name "/DVL_HUSB_M") (class "Default")
      (node (ref "DVL_HOST_FTDI") (pin "15") (pinfunction "USBDM_15") (pintype "bidirectional"))
      (node (ref "R49") (pin "1") (pinfunction "1_1") (pintype "passive"))
      (node (ref "R50") (pin "1") (pinfunction "1_1") (pintype "passive"))
    )
    (net (code "44") (name "/DVL_HUSB_P") (class "Default")
      (node (ref "DVL_HOST_FTDI") (pin "14") (pinfunction "USBDP_14") (pintype "bidirectional"))
      (node (ref "R53") (pin "1") (pinfunction "1_1") (pintype "passive"))
      (node (ref "R54") (pin "1") (pinfunction "1_1") (pintype "passive"))
    )
    (net (code "45") (name "/DVL_H~{CTS}") (class "Default")
      (node (ref "DVL_HOST_FTDI") (pin "8") (pinfunction "~{CTS}_8") (pintype "input"))
      (node (ref "DVL_TTL-TO-RS232") (pin "5") (pinfunction "ROUT2_5") (pintype "bidirectional"))
    )
    (net (code "46") (name "/DVL_H~{RTS}") (class "Default")
      (node (ref "DVL_HOST_FTDI") (pin "32") (pinfunction "~{RTS}_32") (pintype "output"))
      (node (ref "DVL_TTL-TO-RS232") (pin "20") (pinfunction "DIN3_20") (pintype "bidirectional"))
    )
    (net (code "47") (name "/DVL_SCTS") (class "Default")
      (node (ref "5.7") (pin "P$1") (pinfunction "P$1_P$1") (pintype "bidirectional"))
      (node (ref "5.7") (pin "P$2") (pinfunction "P$1_P$2") (pintype "bidirectional"))
      (node (ref "DVL_TTL-TO-RS232") (pin "23") (pinfunction "RIN4_23") (pintype "bidirectional"))
      (node (ref "U$56") (pin "P$2") (pinfunction "I/O_1_P$2") (pintype "bidirectional"))
    )
    (net (code "48") (name "/DVL_SRTS") (class "Default")
      (node (ref "5.5") (pin "P$10") (pinfunction "P$5_P$10") (pintype "bidirectional"))
      (node (ref "5.5") (pin "P$9") (pinfunction "P$5_P$9") (pintype "bidirectional"))
      (node (ref "DVL_TTL-TO-RS232") (pin "28") (pinfunction "DOUT4_28") (pintype "bidirectional"))
      (node (ref "U$59") (pin "P$3") (pinfunction "I/O_2_P$3") (pintype "bidirectional"))
    )
    (net (code "49") (name "/DVL_SRX") (class "Default")
      (node (ref "5.6") (pin "P$1") (pinfunction "P$1_P$1") (pintype "bidirectional"))
      (node (ref "5.6") (pin "P$2") (pinfunction "P$1_P$2") (pintype "bidirectional"))
      (node (ref "DVL_TTL-TO-RS232") (pin "27") (pinfunction "RIN3_27") (pintype "bidirectional"))
      (node (ref "U$58") (pin "P$2") (pinfunction "I/O_1_P$2") (pintype "bidirectional"))
    )
    (net (code "50") (name "/DVL_SRXD") (class "Default")
      (node (ref "DVL_SLAVE_FTDI") (pin "2") (pinfunction "RXD_2") (pintype "input"))
      (node (ref "DVL_TTL-TO-RS232") (pin "26") (pinfunction "ROUT3_26") (pintype "bidirectional"))
    )
    (net (code "51") (name "/DVL_STX") (class "Default")
      (node (ref "5.4") (pin "P$10") (pinfunction "P$5_P$10") (pintype "bidirectional"))
      (node (ref "5.4") (pin "P$9") (pinfunction "P$5_P$9") (pintype "bidirectional"))
      (node (ref "DVL_TTL-TO-RS232") (pin "3") (pinfunction "DOUT2_3") (pintype "bidirectional"))
      (node (ref "U$59") (pin "P$2") (pinfunction "I/O_1_P$2") (pintype "bidirectional"))
    )
    (net (code "52") (name "/DVL_STXD") (class "Default")
      (node (ref "DVL_SLAVE_FTDI") (pin "30") (pinfunction "TXD_30") (pintype "output"))
      (node (ref "DVL_TTL-TO-RS232") (pin "6") (pinfunction "DIN2_6") (pintype "bidirectional"))
    )
    (net (code "53") (name "/DVL_SUSB_M") (class "Default")
      (node (ref "DVL_SLAVE_FTDI") (pin "15") (pinfunction "USBDM_15") (pintype "bidirectional"))
      (node (ref "R57") (pin "1") (pinfunction "1_1") (pintype "passive"))
      (node (ref "R58") (pin "1") (pinfunction "1_1") (pintype "passive"))
    )
    (net (code "54") (name "/DVL_SUSB_P") (class "Default")
      (node (ref "DVL_SLAVE_FTDI") (pin "14") (pinfunction "USBDP_14") (pintype "bidirectional"))
      (node (ref "R55") (pin "1") (pinfunction "1_1") (pintype "passive"))
      (node (ref "R56") (pin "1") (pinfunction "1_1") (pintype "passive"))
    )
    (net (code "55") (name "/DVL_S~{CTS}") (class "Default")
      (node (ref "DVL_SLAVE_FTDI") (pin "8") (pinfunction "~{CTS}_8") (pintype "input"))
      (node (ref "DVL_TTL-TO-RS232") (pin "22") (pinfunction "ROUT4_22") (pintype "bidirectional"))
    )
    (net (code "56") (name "/DVL_S~{RTS}") (class "Default")
      (node (ref "DVL_SLAVE_FTDI") (pin "32") (pinfunction "~{RTS}_32") (pintype "output"))
      (node (ref "DVL_TTL-TO-RS232") (pin "21") (pinfunction "DIN4_21") (pintype "bidirectional"))
    )
    (net (code "57") (name "/DVL_USB_HUB_XTAL") (class "Default")
      (node (ref "DVL_USB_HUB") (pin "P$24") (pinfunction "XTALIN/CLO\\KIN_P$24") (pintype "bidirectional"))
      (node (ref "U$1") (pin "P$3") (pinfunction "OUT_P$3") (pintype "bidirectional"))
    )
    (net (code "58") (name "/DVL_USB_N") (class "Default")
      (node (ref "2PIN_5") (pin "P$2") (pinfunction "P$2_P$2") (pintype "bidirectional"))
      (node (ref "R51") (pin "1") (pinfunction "1_1") (pintype "passive"))
      (node (ref "R52") (pin "1") (pinfunction "1_1") (pintype "passive"))
      (node (ref "U$7") (pin "P$3") (pinfunction "I/O_2_P$3") (pintype "bidirectional"))
    )
    (net (code "59") (name "/DVL_USB_P") (class "Default")
      (node (ref "2PIN_5") (pin "P$1") (pinfunction "P$1_P$1") (pintype "bidirectional"))
      (node (ref "R59") (pin "1") (pinfunction "1_1") (pintype "passive"))
      (node (ref "R60") (pin "1") (pinfunction "1_1") (pintype "passive"))
      (node (ref "U$7") (pin "P$2") (pinfunction "I/O_1_P$2") (pintype "bidirectional"))
    )
    (net (code "60") (name "/EXT_SCL") (class "Default")
      (node (ref "5.3") (pin "P$3") (pinfunction "P$2_P$3") (pintype "bidirectional"))
      (node (ref "5.3") (pin "P$4") (pinfunction "P$2_P$4") (pintype "bidirectional"))
      (node (ref "JP1") (pin "34") (pinfunction "P$34_34") (pintype "bidirectional"))
      (node (ref "JP2") (pin "34") (pinfunction "P$34_34") (pintype "bidirectional"))
      (node (ref "JP3") (pin "34") (pinfunction "P$34_34") (pintype "bidirectional"))
      (node (ref "JP4") (pin "34") (pinfunction "P$34_34") (pintype "bidirectional"))
      (node (ref "U$52") (pin "P$2") (pinfunction "I/O_1_P$2") (pintype "bidirectional"))
    )
    (net (code "61") (name "/EXT_SDA") (class "Default")
      (node (ref "5.3") (pin "P$5") (pinfunction "P$3_P$5") (pintype "bidirectional"))
      (node (ref "5.3") (pin "P$6") (pinfunction "P$3_P$6") (pintype "bidirectional"))
      (node (ref "JP1") (pin "33") (pinfunction "P$33_33") (pintype "bidirectional"))
      (node (ref "JP2") (pin "33") (pinfunction "P$33_33") (pintype "bidirectional"))
      (node (ref "JP3") (pin "33") (pinfunction "P$33_33") (pintype "bidirectional"))
      (node (ref "JP4") (pin "33") (pinfunction "P$33_33") (pintype "bidirectional"))
      (node (ref "U$52") (pin "P$3") (pinfunction "I/O_2_P$3") (pintype "bidirectional"))
    )
    (net (code "62") (name "/EXT_USB_5V") (class "Default")
      (node (ref "5.7") (pin "P$3") (pinfunction "P$2_P$3") (pintype "bidirectional"))
      (node (ref "5.7") (pin "P$4") (pinfunction "P$2_P$4") (pintype "bidirectional"))
      (node (ref "D41") (pin "C") (pinfunction "C_C") (pintype "passive"))
      (node (ref "G1") (pin "OUT3") (pinfunction "OUT3_OUT3") (pintype "bidirectional"))
      (node (ref "U$68") (pin "P$2") (pinfunction "P$2_P$2") (pintype "bidirectional"))
      (node (ref "U$69") (pin "P$1") (pinfunction "+_P$1") (pintype "bidirectional"))
    )
    (net (code "63") (name "/EXT_USB_N") (class "Default")
      (node (ref "5.7") (pin "P$10") (pinfunction "P$5_P$10") (pintype "bidirectional"))
      (node (ref "5.7") (pin "P$9") (pinfunction "P$5_P$9") (pintype "bidirectional"))
      (node (ref "R34") (pin "2") (pinfunction "2_2") (pintype "passive"))
      (node (ref "R47") (pin "1") (pinfunction "1_1") (pintype "passive"))
      (node (ref "U$5") (pin "P$3") (pinfunction "I/O_2_P$3") (pintype "bidirectional"))
    )
    (net (code "64") (name "/EXT_USB_P") (class "Default")
      (node (ref "5.7") (pin "P$7") (pinfunction "P$4_P$7") (pintype "bidirectional"))
      (node (ref "5.7") (pin "P$8") (pinfunction "P$4_P$8") (pintype "bidirectional"))
      (node (ref "R35") (pin "2") (pinfunction "2_2") (pintype "passive"))
      (node (ref "R48") (pin "1") (pinfunction "1_1") (pintype "passive"))
      (node (ref "U$5") (pin "P$2") (pinfunction "I/O_1_P$2") (pintype "bidirectional"))
    )
    (net (code "65") (name "/GND") (class "Default")
      (node (ref "4PIN_5") (pin "P$1") (pinfunction "P$1_P$1") (pintype "bidirectional"))
      (node (ref "4PIN_5") (pin "P$2") (pinfunction "P$2_P$2") (pintype "bidirectional"))
      (node (ref "4PIN_5") (pin "P$3") (pinfunction "P$3_P$3") (pintype "bidirectional"))
      (node (ref "4PIN_5") (pin "P$4") (pinfunction "P$4_P$4") (pintype "bidirectional"))
      (node (ref "4PIN_6") (pin "P$1") (pinfunction "P$1_P$1") (pintype "bidirectional"))
      (node (ref "4PIN_6") (pin "P$2") (pinfunction "P$2_P$2") (pintype "bidirectional"))
      (node (ref "4PIN_6") (pin "P$3") (pinfunction "P$3_P$3") (pintype "bidirectional"))
      (node (ref "4PIN_6") (pin "P$4") (pinfunction "P$4_P$4") (pintype "bidirectional"))
      (node (ref "5.0") (pin "P$10") (pinfunction "P$5_P$10") (pintype "bidirectional"))
      (node (ref "5.0") (pin "P$3") (pinfunction "P$2_P$3") (pintype "bidirectional"))
      (node (ref "5.0") (pin "P$4") (pinfunction "P$2_P$4") (pintype "bidirectional"))
      (node (ref "5.0") (pin "P$5") (pinfunction "P$3_P$5") (pintype "bidirectional"))
      (node (ref "5.0") (pin "P$6") (pinfunction "P$3_P$6") (pintype "bidirectional"))
      (node (ref "5.0") (pin "P$7") (pinfunction "P$4_P$7") (pintype "bidirectional"))
      (node (ref "5.0") (pin "P$8") (pinfunction "P$4_P$8") (pintype "bidirectional"))
      (node (ref "5.0") (pin "P$9") (pinfunction "P$5_P$9") (pintype "bidirectional"))
      (node (ref "5.2") (pin "P$1") (pinfunction "P$1_P$1") (pintype "bidirectional"))
      (node (ref "5.2") (pin "P$2") (pinfunction "P$1_P$2") (pintype "bidirectional"))
      (node (ref "5.3") (pin "P$1") (pinfunction "P$1_P$1") (pintype "bidirectional"))
      (node (ref "5.3") (pin "P$2") (pinfunction "P$1_P$2") (pintype "bidirectional"))
      (node (ref "5.7") (pin "P$5") (pinfunction "P$3_P$5") (pintype "bidirectional"))
      (node (ref "5.7") (pin "P$6") (pinfunction "P$3_P$6") (pintype "bidirectional"))
      (node (ref "BATTERY-MUX") (pin "P$1") (pinfunction "A0_P$1") (pintype "bidirectional"))
      (node (ref "BATTERY-MUX") (pin "P$13") (pinfunction "A2_P$13") (pintype "bidirectional"))
      (node (ref "BATTERY-MUX") (pin "P$2") (pinfunction "A1_P$2") (pintype "bidirectional"))
      (node (ref "BATTERY-MUX") (pin "P$8") (pinfunction "VSS_P$8") (pintype "bidirectional"))
      (node (ref "C1") (pin "2") (pinfunction "2_2") (pintype "passive"))
      (node (ref "C10") (pin "2") (pinfunction "2_2") (pintype "passive"))
      (node (ref "C11") (pin "2") (pinfunction "2_2") (pintype "passive"))
      (node (ref "C16") (pin "2") (pinfunction "2_2") (pintype "passive"))
      (node (ref "C19") (pin "1") (pinfunction "1_1") (pintype "passive"))
      (node (ref "C2") (pin "2") (pinfunction "2_2") (pintype "passive"))
      (node (ref "C26") (pin "2") (pinfunction "2_2") (pintype "passive"))
      (node (ref "C27") (pin "2") (pinfunction "2_2") (pintype "passive"))
      (node (ref "C28") (pin "2") (pinfunction "2_2") (pintype "passive"))
      (node (ref "C29") (pin "2") (pinfunction "2_2") (pintype "passive"))
      (node (ref "C3") (pin "2") (pinfunction "2_2") (pintype "passive"))
      (node (ref "C30") (pin "2") (pinfunction "2_2") (pintype "passive"))
      (node (ref "C31") (pin "2") (pinfunction "2_2") (pintype "passive"))
      (node (ref "C32") (pin "2") (pinfunction "2_2") (pintype "passive"))
      (node (ref "C33") (pin "2") (pinfunction "2_2") (pintype "passive"))
      (node (ref "C34") (pin "2") (pinfunction "2_2") (pintype "passive"))
      (node (ref "C35") (pin "2") (pinfunction "2_2") (pintype "passive"))
      (node (ref "C36") (pin "2") (pinfunction "2_2") (pintype "passive"))
      (node (ref "C37") (pin "2") (pinfunction "2_2") (pintype "passive"))
      (node (ref "C38") (pin "2") (pinfunction "2_2") (pintype "passive"))
      (node (ref "C39") (pin "2") (pinfunction "2_2") (pintype "passive"))
      (node (ref "C4") (pin "2") (pinfunction "2_2") (pintype "passive"))
      (node (ref "C40") (pin "2") (pinfunction "2_2") (pintype "passive"))
      (node (ref "C41") (pin "2") (pinfunction "2_2") (pintype "passive"))
      (node (ref "C42") (pin "2") (pinfunction "2_2") (pintype "passive"))
      (node (ref "C43") (pin "2") (pinfunction "2_2") (pintype "passive"))
      (node (ref "C44") (pin "2") (pinfunction "2_2") (pintype "passive"))
      (node (ref "C45") (pin "2") (pinfunction "2_2") (pintype "passive"))
      (node (ref "C46") (pin "2") (pinfunction "2_2") (pintype "passive"))
      (node (ref "C47") (pin "2") (pinfunction "2_2") (pintype "passive"))
      (node (ref "C48") (pin "2") (pinfunction "2_2") (pintype "passive"))
      (node (ref "C5") (pin "2") (pinfunction "2_2") (pintype "passive"))
      (node (ref "C6") (pin "2") (pinfunction "2_2") (pintype "passive"))
      (node (ref "C7") (pin "2") (pinfunction "2_2") (pintype "passive"))
      (node (ref "C8") (pin "2") (pinfunction "2_2") (pintype "passive"))
      (node (ref "C9") (pin "2") (pinfunction "2_2") (pintype "passive"))
      (node (ref "D10") (pin "A") (pinfunction "A_A") (pintype "passive"))
      (node (ref "D11") (pin "A") (pinfunction "A_A") (pintype "passive"))
      (node (ref "D12") (pin "A") (pinfunction "A_A") (pintype "passive"))
      (node (ref "D13") (pin "A") (pinfunction "A_A") (pintype "passive"))
      (node (ref "D14") (pin "A") (pinfunction "A_A") (pintype "passive"))
      (node (ref "D15") (pin "A") (pinfunction "A_A") (pintype "passive"))
      (node (ref "D16") (pin "A") (pinfunction "A_A") (pintype "passive"))
      (node (ref "D17") (pin "A") (pinfunction "A_A") (pintype "passive"))
      (node (ref "D18") (pin "A") (pinfunction "A_A") (pintype "passive"))
      (node (ref "D19") (pin "A") (pinfunction "A_A") (pintype "passive"))
      (node (ref "D2") (pin "A") (pinfunction "A_A") (pintype "passive"))
      (node (ref "D20") (pin "A") (pinfunction "A_A") (pintype "passive"))
      (node (ref "D21") (pin "A") (pinfunction "A_A") (pintype "passive"))
      (node (ref "D22") (pin "A") (pinfunction "A_A") (pintype "passive"))
      (node (ref "D23") (pin "A") (pinfunction "A_A") (pintype "passive"))
      (node (ref "D24") (pin "A") (pinfunction "A_A") (pintype "passive"))
      (node (ref "D25") (pin "A") (pinfunction "A_A") (pintype "passive"))
      (node (ref "D26") (pin "A") (pinfunction "A_A") (pintype "passive"))
      (node (ref "D27") (pin "A") (pinfunction "A_A") (pintype "passive"))
      (node (ref "D28") (pin "A") (pinfunction "A_A") (pintype "passive"))
      (node (ref "D29") (pin "A") (pinfunction "A_A") (pintype "passive"))
      (node (ref "D3") (pin "A") (pinfunction "A_A") (pintype "passive"))
      (node (ref "D30") (pin "A") (pinfunction "A_A") (pintype "passive"))
      (node (ref "D31") (pin "A") (pinfunction "A_A") (pintype "passive"))
      (node (ref "D32") (pin "A") (pinfunction "A_A") (pintype "passive"))
      (node (ref "D33") (pin "A") (pinfunction "A_A") (pintype "passive"))
      (node (ref "D34") (pin "A") (pinfunction "A_A") (pintype "passive"))
      (node (ref "D35") (pin "A") (pinfunction "A_A") (pintype "passive"))
      (node (ref "D36") (pin "A") (pinfunction "A_A") (pintype "passive"))
      (node (ref "D37") (pin "A") (pinfunction "A_A") (pintype "passive"))
      (node (ref "D39") (pin "A") (pinfunction "A_A") (pintype "passive"))
      (node (ref "D4") (pin "A") (pinfunction "A_A") (pintype "passive"))
      (node (ref "D40") (pin "A") (pinfunction "A_A") (pintype "passive"))
      (node (ref "D41") (pin "A") (pinfunction "A_A") (pintype "passive"))
      (node (ref "D5") (pin "A") (pinfunction "A_A") (pintype "passive"))
      (node (ref "D6") (pin "A") (pinfunction "A_A") (pintype "passive"))
      (node (ref "D7") (pin "A") (pinfunction "A_A") (pintype "passive"))
      (node (ref "D8") (pin "A") (pinfunction "A_A") (pintype "passive"))
      (node (ref "D9") (pin "A") (pinfunction "A_A") (pintype "passive"))
      (node (ref "DVL_HOST_FTDI") (pin "17") (pinfunction "GND_17") (pintype "power_in"))
      (node (ref "DVL_HOST_FTDI") (pin "20") (pinfunction "GND_20") (pintype "power_in"))
      (node (ref "DVL_HOST_FTDI") (pin "24") (pinfunction "GND_24") (pintype "power_in"))
      (node (ref "DVL_HOST_FTDI") (pin "26") (pinfunction "TEST_26") (pintype "input"))
      (node (ref "DVL_HOST_FTDI") (pin "4") (pinfunction "GND_4") (pintype "power_in"))
      (node (ref "DVL_SLAVE_FTDI") (pin "17") (pinfunction "GND_17") (pintype "power_in"))
      (node (ref "DVL_SLAVE_FTDI") (pin "20") (pinfunction "GND_20") (pintype "power_in"))
      (node (ref "DVL_SLAVE_FTDI") (pin "24") (pinfunction "GND_24") (pintype "power_in"))
      (node (ref "DVL_SLAVE_FTDI") (pin "26") (pinfunction "TEST_26") (pintype "input"))
      (node (ref "DVL_SLAVE_FTDI") (pin "4") (pinfunction "GND_4") (pintype "power_in"))
      (node (ref "DVL_TTL-TO-RS232") (pin "10") (pinfunction "GND_10") (pintype "bidirectional"))
      (node (ref "DVL_USB_HUB") (pin "P$11") (pinfunction "PRTPWR2_P$11") (pintype "bidirectional"))
      (node (ref "DVL_USB_HUB") (pin "P$15") (pinfunction "VSS_P$15") (pintype "bidirectional"))
      (node (ref "DVL_USB_HUB") (pin "P$29") (pinfunction "GND_P$29") (pintype "bidirectional"))
      (node (ref "DVL_USB_HUB") (pin "P$7") (pinfunction "PRTPWR1_P$7") (pintype "bidirectional"))
      (node (ref "G1") (pin "GND1") (pinfunction "GND1_GND1") (pintype "bidirectional"))
      (node (ref "G1") (pin "GND2") (pinfunction "GND2_GND2") (pintype "bidirectional"))
      (node (ref "JP1") (pin "1") (pinfunction "P$1_1") (pintype "bidirectional"))
      (node (ref "JP1") (pin "15") (pinfunction "P$15_15") (pintype "bidirectional"))
      (node (ref "JP1") (pin "19") (pinfunction "P$19_19") (pintype "bidirectional"))
      (node (ref "JP1") (pin "20") (pinfunction "P$20_20") (pintype "bidirectional"))
      (node (ref "JP1") (pin "21") (pinfunction "P$21_21") (pintype "bidirectional"))
      (node (ref "JP1") (pin "25") (pinfunction "P$25_25") (pintype "bidirectional"))
      (node (ref "JP1") (pin "32") (pinfunction "P$32_32") (pintype "bidirectional"))
      (node (ref "JP1") (pin "35") (pinfunction "P$35_35") (pintype "bidirectional"))
      (node (ref "JP1") (pin "39") (pinfunction "P$39_39") (pintype "bidirectional"))
      (node (ref "JP1") (pin "40") (pinfunction "P$40_40") (pintype "bidirectional"))
      (node (ref "JP1") (pin "42") (pinfunction "P$42_42") (pintype "bidirectional"))
      (node (ref "JP1") (pin "47") (pinfunction "P$47_47") (pintype "bidirectional"))
      (node (ref "JP1") (pin "55") (pinfunction "P$55_55") (pintype "bidirectional"))
      (node (ref "JP1") (pin "59") (pinfunction "P$59_59") (pintype "bidirectional"))
      (node (ref "JP1") (pin "60") (pinfunction "P$60_60") (pintype "bidirectional"))
      (node (ref "JP1") (pin "62") (pinfunction "P$62_62") (pintype "bidirectional"))
      (node (ref "JP1") (pin "75") (pinfunction "P$75_75") (pintype "bidirectional"))
      (node (ref "JP1") (pin "79") (pinfunction "P$79_79") (pintype "bidirectional"))
      (node (ref "JP1") (pin "80") (pinfunction "P$80_80") (pintype "bidirectional"))
      (node (ref "JP1") (pin "P1,1") (pinfunction "POWER1_P1,1") (pintype "bidirectional"))
      (node (ref "JP1") (pin "P1,2") (pinfunction "POWER1_P1,2") (pintype "bidirectional"))
      (node (ref "JP1") (pin "P1,3") (pinfunction "POWER1_P1,3") (pintype "bidirectional"))
      (node (ref "JP1") (pin "P1,4") (pinfunction "POWER1_P1,4") (pintype "bidirectional"))
      (node (ref "JP1") (pin "P1,5") (pinfunction "POWER1_P1,5") (pintype "bidirectional"))
      (node (ref "JP1") (pin "P1,6") (pinfunction "POWER1_P1,6") (pintype "bidirectional"))
      (node (ref "JP2") (pin "1") (pinfunction "P$1_1") (pintype "bidirectional"))
      (node (ref "JP2") (pin "15") (pinfunction "P$15_15") (pintype "bidirectional"))
      (node (ref "JP2") (pin "19") (pinfunction "P$19_19") (pintype "bidirectional"))
      (node (ref "JP2") (pin "20") (pinfunction "P$20_20") (pintype "bidirectional"))
      (node (ref "JP2") (pin "21") (pinfunction "P$21_21") (pintype "bidirectional"))
      (node (ref "JP2") (pin "25") (pinfunction "P$25_25") (pintype "bidirectional"))
      (node (ref "JP2") (pin "32") (pinfunction "P$32_32") (pintype "bidirectional"))
      (node (ref "JP2") (pin "35") (pinfunction "P$35_35") (pintype "bidirectional"))
      (node (ref "JP2") (pin "39") (pinfunction "P$39_39") (pintype "bidirectional"))
      (node (ref "JP2") (pin "40") (pinfunction "P$40_40") (pintype "bidirectional"))
      (node (ref "JP2") (pin "42") (pinfunction "P$42_42") (pintype "bidirectional"))
      (node (ref "JP2") (pin "47") (pinfunction "P$47_47") (pintype "bidirectional"))
      (node (ref "JP2") (pin "55") (pinfunction "P$55_55") (pintype "bidirectional"))
      (node (ref "JP2") (pin "59") (pinfunction "P$59_59") (pintype "bidirectional"))
      (node (ref "JP2") (pin "60") (pinfunction "P$60_60") (pintype "bidirectional"))
      (node (ref "JP2") (pin "62") (pinfunction "P$62_62") (pintype "bidirectional"))
      (node (ref "JP2") (pin "75") (pinfunction "P$75_75") (pintype "bidirectional"))
      (node (ref "JP2") (pin "79") (pinfunction "P$79_79") (pintype "bidirectional"))
      (node (ref "JP2") (pin "80") (pinfunction "P$80_80") (pintype "bidirectional"))
      (node (ref "JP2") (pin "P1,1") (pinfunction "POWER1_P1,1") (pintype "bidirectional"))
      (node (ref "JP2") (pin "P1,2") (pinfunction "POWER1_P1,2") (pintype "bidirectional"))
      (node (ref "JP2") (pin "P1,3") (pinfunction "POWER1_P1,3") (pintype "bidirectional"))
      (node (ref "JP2") (pin "P1,4") (pinfunction "POWER1_P1,4") (pintype "bidirectional"))
      (node (ref "JP2") (pin "P1,5") (pinfunction "POWER1_P1,5") (pintype "bidirectional"))
      (node (ref "JP2") (pin "P1,6") (pinfunction "POWER1_P1,6") (pintype "bidirectional"))
      (node (ref "JP3") (pin "1") (pinfunction "P$1_1") (pintype "bidirectional"))
      (node (ref "JP3") (pin "15") (pinfunction "P$15_15") (pintype "bidirectional"))
      (node (ref "JP3") (pin "19") (pinfunction "P$19_19") (pintype "bidirectional"))
      (node (ref "JP3") (pin "20") (pinfunction "P$20_20") (pintype "bidirectional"))
      (node (ref "JP3") (pin "21") (pinfunction "P$21_21") (pintype "bidirectional"))
      (node (ref "JP3") (pin "25") (pinfunction "P$25_25") (pintype "bidirectional"))
      (node (ref "JP3") (pin "32") (pinfunction "P$32_32") (pintype "bidirectional"))
      (node (ref "JP3") (pin "35") (pinfunction "P$35_35") (pintype "bidirectional"))
      (node (ref "JP3") (pin "39") (pinfunction "P$39_39") (pintype "bidirectional"))
      (node (ref "JP3") (pin "40") (pinfunction "P$40_40") (pintype "bidirectional"))
      (node (ref "JP3") (pin "42") (pinfunction "P$42_42") (pintype "bidirectional"))
      (node (ref "JP3") (pin "47") (pinfunction "P$47_47") (pintype "bidirectional"))
      (node (ref "JP3") (pin "55") (pinfunction "P$55_55") (pintype "bidirectional"))
      (node (ref "JP3") (pin "59") (pinfunction "P$59_59") (pintype "bidirectional"))
      (node (ref "JP3") (pin "60") (pinfunction "P$60_60") (pintype "bidirectional"))
      (node (ref "JP3") (pin "62") (pinfunction "P$62_62") (pintype "bidirectional"))
      (node (ref "JP3") (pin "75") (pinfunction "P$75_75") (pintype "bidirectional"))
      (node (ref "JP3") (pin "79") (pinfunction "P$79_79") (pintype "bidirectional"))
      (node (ref "JP3") (pin "80") (pinfunction "P$80_80") (pintype "bidirectional"))
      (node (ref "JP3") (pin "P1,1") (pinfunction "POWER1_P1,1") (pintype "bidirectional"))
      (node (ref "JP3") (pin "P1,2") (pinfunction "POWER1_P1,2") (pintype "bidirectional"))
      (node (ref "JP3") (pin "P1,3") (pinfunction "POWER1_P1,3") (pintype "bidirectional"))
      (node (ref "JP3") (pin "P1,4") (pinfunction "POWER1_P1,4") (pintype "bidirectional"))
      (node (ref "JP3") (pin "P1,5") (pinfunction "POWER1_P1,5") (pintype "bidirectional"))
      (node (ref "JP3") (pin "P1,6") (pinfunction "POWER1_P1,6") (pintype "bidirectional"))
      (node (ref "JP4") (pin "1") (pinfunction "P$1_1") (pintype "bidirectional"))
      (node (ref "JP4") (pin "15") (pinfunction "P$15_15") (pintype "bidirectional"))
      (node (ref "JP4") (pin "19") (pinfunction "P$19_19") (pintype "bidirectional"))
      (node (ref "JP4") (pin "20") (pinfunction "P$20_20") (pintype "bidirectional"))
      (node (ref "JP4") (pin "21") (pinfunction "P$21_21") (pintype "bidirectional"))
      (node (ref "JP4") (pin "25") (pinfunction "P$25_25") (pintype "bidirectional"))
      (node (ref "JP4") (pin "32") (pinfunction "P$32_32") (pintype "bidirectional"))
      (node (ref "JP4") (pin "35") (pinfunction "P$35_35") (pintype "bidirectional"))
      (node (ref "JP4") (pin "39") (pinfunction "P$39_39") (pintype "bidirectional"))
      (node (ref "JP4") (pin "40") (pinfunction "P$40_40") (pintype "bidirectional"))
      (node (ref "JP4") (pin "42") (pinfunction "P$42_42") (pintype "bidirectional"))
      (node (ref "JP4") (pin "47") (pinfunction "P$47_47") (pintype "bidirectional"))
      (node (ref "JP4") (pin "55") (pinfunction "P$55_55") (pintype "bidirectional"))
      (node (ref "JP4") (pin "59") (pinfunction "P$59_59") (pintype "bidirectional"))
      (node (ref "JP4") (pin "60") (pinfunction "P$60_60") (pintype "bidirectional"))
      (node (ref "JP4") (pin "62") (pinfunction "P$62_62") (pintype "bidirectional"))
      (node (ref "JP4") (pin "75") (pinfunction "P$75_75") (pintype "bidirectional"))
      (node (ref "JP4") (pin "79") (pinfunction "P$79_79") (pintype "bidirectional"))
      (node (ref "JP4") (pin "80") (pinfunction "P$80_80") (pintype "bidirectional"))
      (node (ref "JP4") (pin "P1,1") (pinfunction "POWER1_P1,1") (pintype "bidirectional"))
      (node (ref "JP4") (pin "P1,2") (pinfunction "POWER1_P1,2") (pintype "bidirectional"))
      (node (ref "JP4") (pin "P1,3") (pinfunction "POWER1_P1,3") (pintype "bidirectional"))
      (node (ref "JP4") (pin "P1,4") (pinfunction "POWER1_P1,4") (pintype "bidirectional"))
      (node (ref "JP4") (pin "P1,5") (pinfunction "POWER1_P1,5") (pintype "bidirectional"))
      (node (ref "JP4") (pin "P1,6") (pinfunction "POWER1_P1,6") (pintype "bidirectional"))
      (node (ref "LED11") (pin "C") (pinfunction "C_C") (pintype "passive"))
      (node (ref "LED13") (pin "C") (pinfunction "C_C") (pintype "passive"))
      (node (ref "LED15") (pin "C") (pinfunction "C_C") (pintype "passive"))
      (node (ref "LED9") (pin "C") (pinfunction "C_C") (pintype "passive"))
      (node (ref "R10") (pin "1") (pinfunction "1_1") (pintype "passive"))
      (node (ref "R12") (pin "1") (pinfunction "1_1") (pintype "passive"))
      (node (ref "R13") (pin "2") (pinfunction "2_2") (pintype "passive"))
      (node (ref "R14") (pin "2") (pinfunction "2_2") (pintype "passive"))
      (node (ref "R15") (pin "2") (pinfunction "2_2") (pintype "passive"))
      (node (ref "R2") (pin "2") (pinfunction "2_2") (pintype "passive"))
      (node (ref "R36") (pin "2") (pinfunction "2_2") (pintype "passive"))
      (node (ref "R37") (pin "2") (pinfunction "2_2") (pintype "passive"))
      (node (ref "R38") (pin "2") (pinfunction "2_2") (pintype "passive"))
      (node (ref "R39") (pin "2") (pinfunction "2_2") (pintype "passive"))
      (node (ref "R40") (pin "2") (pinfunction "2_2") (pintype "passive"))
      (node (ref "R41") (pin "2") (pinfunction "2_2") (pintype "passive"))
      (node (ref "R42") (pin "2") (pinfunction "2_2") (pintype "passive"))
      (node (ref "R43") (pin "2") (pinfunction "2_2") (pintype "passive"))
      (node (ref "R44") (pin "2") (pinfunction "2_2") (pintype "passive"))
      (node (ref "R45") (pin "2") (pinfunction "2_2") (pintype "passive"))
      (node (ref "R46") (pin "2") (pinfunction "2_2") (pintype "passive"))
      (node (ref "R47") (pin "2") (pinfunction "2_2") (pintype "passive"))
      (node (ref "R48") (pin "2") (pinfunction "2_2") (pintype "passive"))
      (node (ref "R50") (pin "2") (pinfunction "2_2") (pintype "passive"))
      (node (ref "R52") (pin "2") (pinfunction "2_2") (pintype "passive"))
      (node (ref "R54") (pin "2") (pinfunction "2_2") (pintype "passive"))
      (node (ref "R56") (pin "2") (pinfunction "2_2") (pintype "passive"))
      (node (ref "R58") (pin "2") (pinfunction "2_2") (pintype "passive"))
      (node (ref "R60") (pin "2") (pinfunction "2_2") (pintype "passive"))
      (node (ref "U$1") (pin "P$2") (pinfunction "GND_P$2") (pintype "bidirectional"))
      (node (ref "U$100") (pin "P$1") (pinfunction "1_P$1") (pintype "bidirectional"))
      (node (ref "U$100") (pin "P$2") (pinfunction "2_P$2") (pintype "bidirectional"))
      (node (ref "U$100") (pin "P$3") (pinfunction "3_P$3") (pintype "bidirectional"))
      (node (ref "U$100") (pin "P$4") (pinfunction "4_P$4") (pintype "bidirectional"))
      (node (ref "U$100") (pin "P$5") (pinfunction "5_P$5") (pintype "bidirectional"))
      (node (ref "U$100") (pin "P$6") (pinfunction "6_P$6") (pintype "bidirectional"))
      (node (ref "U$100") (pin "P$7") (pinfunction "7_P$7") (pintype "bidirectional"))
      (node (ref "U$100") (pin "P$8") (pinfunction "8_P$8") (pintype "bidirectional"))
      (node (ref "U$101") (pin "1") (pinfunction "P$1_1") (pintype "bidirectional"))
      (node (ref "U$103") (pin "1") (pinfunction "P$1_1") (pintype "bidirectional"))
      (node (ref "U$104") (pin "1") (pinfunction "P$1_1") (pintype "bidirectional"))
      (node (ref "U$105") (pin "1") (pinfunction "P$1_1") (pintype "bidirectional"))
      (node (ref "U$106") (pin "1") (pinfunction "P$1_1") (pintype "bidirectional"))
      (node (ref "U$109") (pin "1") (pinfunction "P$1_1") (pintype "bidirectional"))
      (node (ref "U$11") (pin "P$1") (pinfunction "P$1_P$1") (pintype "bidirectional"))
      (node (ref "U$12") (pin "P$2") (pinfunction "-_P$2") (pintype "bidirectional"))
      (node (ref "U$15") (pin "P$1") (pinfunction "P$1_P$1") (pintype "bidirectional"))
      (node (ref "U$18") (pin "P$1") (pinfunction "GND_P$1") (pintype "bidirectional"))
      (node (ref "U$19") (pin "P$1") (pinfunction "GND_P$1") (pintype "bidirectional"))
      (node (ref "U$2") (pin "P$1") (pinfunction "GND_P$1") (pintype "bidirectional"))
      (node (ref "U$20") (pin "P$1") (pinfunction "GND_P$1") (pintype "bidirectional"))
      (node (ref "U$21") (pin "1") (pinfunction "P$1_1") (pintype "bidirectional"))
      (node (ref "U$22") (pin "P$1") (pinfunction "GND_P$1") (pintype "bidirectional"))
      (node (ref "U$23") (pin "P$1") (pinfunction "GND_P$1") (pintype "bidirectional"))
      (node (ref "U$24") (pin "P$1") (pinfunction "P$1_P$1") (pintype "bidirectional"))
      (node (ref "U$25") (pin "P$1") (pinfunction "P$1_P$1") (pintype "bidirectional"))
      (node (ref "U$26") (pin "1") (pinfunction "P$1_1") (pintype "bidirectional"))
      (node (ref "U$27") (pin "P$1") (pinfunction "GND_P$1") (pintype "bidirectional"))
      (node (ref "U$28") (pin "P$1") (pinfunction "GND_P$1") (pintype "bidirectional"))
      (node (ref "U$29") (pin "P$1") (pinfunction "GND_P$1") (pintype "bidirectional"))
      (node (ref "U$3") (pin "P$1") (pinfunction "GND_P$1") (pintype "bidirectional"))
      (node (ref "U$30") (pin "P$1") (pinfunction "GND_P$1") (pintype "bidirectional"))
      (node (ref "U$31") (pin "P$1") (pinfunction "GND_P$1") (pintype "bidirectional"))
      (node (ref "U$32") (pin "P$1") (pinfunction "GND_P$1") (pintype "bidirectional"))
      (node (ref "U$33") (pin "P$2") (pinfunction "GND_P$2") (pintype "bidirectional"))
      (node (ref "U$34") (pin "P$2") (pinfunction "-_P$2") (pintype "bidirectional"))
      (node (ref "U$35") (pin "P$2") (pinfunction "-_P$2") (pintype "bidirectional"))
      (node (ref "U$36") (pin "1") (pinfunction "P$1_1") (pintype "bidirectional"))
      (node (ref "U$37") (pin "4") (pinfunction "GND_4") (pintype "bidirectional"))
      (node (ref "U$38") (pin "4") (pinfunction "GND_4") (pintype "bidirectional"))
      (node (ref "U$39") (pin "4") (pinfunction "GND_4") (pintype "bidirectional"))
      (node (ref "U$4") (pin "P$1") (pinfunction "GND_P$1") (pintype "bidirectional"))
      (node (ref "U$40") (pin "4") (pinfunction "GND_4") (pintype "bidirectional"))
      (node (ref "U$42") (pin "P$1") (pinfunction "GND_P$1") (pintype "bidirectional"))
      (node (ref "U$44") (pin "P$1") (pinfunction "P$1_P$1") (pintype "bidirectional"))
      (node (ref "U$45") (pin "P$2") (pinfunction "-_P$2") (pintype "bidirectional"))
      (node (ref "U$46") (pin "P$1") (pinfunction "GND_P$1") (pintype "bidirectional"))
      (node (ref "U$48") (pin "P$1") (pinfunction "P$1_P$1") (pintype "bidirectional"))
      (node (ref "U$49") (pin "P$2") (pinfunction "-_P$2") (pintype "bidirectional"))
      (node (ref "U$5") (pin "P$1") (pinfunction "GND_P$1") (pintype "bidirectional"))
      (node (ref "U$50") (pin "4") (pinfunction "GND_4") (pintype "bidirectional"))
      (node (ref "U$51") (pin "P$2") (pinfunction "-_P$2") (pintype "bidirectional"))
      (node (ref "U$52") (pin "P$1") (pinfunction "GND_P$1") (pintype "bidirectional"))
      (node (ref "U$53") (pin "P$1") (pinfunction "GND_P$1") (pintype "bidirectional"))
      (node (ref "U$54") (pin "P$1") (pinfunction "GND_P$1") (pintype "bidirectional"))
      (node (ref "U$55") (pin "P$1") (pinfunction "GND_P$1") (pintype "bidirectional"))
      (node (ref "U$56") (pin "P$1") (pinfunction "GND_P$1") (pintype "bidirectional"))
      (node (ref "U$57") (pin "P$1") (pinfunction "GND_P$1") (pintype "bidirectional"))
      (node (ref "U$58") (pin "P$1") (pinfunction "GND_P$1") (pintype "bidirectional"))
      (node (ref "U$59") (pin "P$1") (pinfunction "GND_P$1") (pintype "bidirectional"))
      (node (ref "U$6") (pin "P$1") (pinfunction "GND_P$1") (pintype "bidirectional"))
      (node (ref "U$60") (pin "P$1") (pinfunction "GND_P$1") (pintype "bidirectional"))
      (node (ref "U$61") (pin "P$1") (pinfunction "GND_P$1") (pintype "bidirectional"))
      (node (ref "U$62") (pin "P$1") (pinfunction "GND_P$1") (pintype "bidirectional"))
      (node (ref "U$63") (pin "P$1") (pinfunction "GND_P$1") (pintype "bidirectional"))
      (node (ref "U$64") (pin "P$2") (pinfunction "-_P$2") (pintype "bidirectional"))
      (node (ref "U$65") (pin "P$2") (pinfunction "-_P$2") (pintype "bidirectional"))
      (node (ref "U$66") (pin "P$2") (pinfunction "-_P$2") (pintype "bidirectional"))
      (node (ref "U$67") (pin "P$2") (pinfunction "-_P$2") (pintype "bidirectional"))
      (node (ref "U$68") (pin "P$1") (pinfunction "P$1_P$1") (pintype "bidirectional"))
      (node (ref "U$69") (pin "P$2") (pinfunction "-_P$2") (pintype "bidirectional"))
      (node (ref "U$7") (pin "P$1") (pinfunction "GND_P$1") (pintype "bidirectional"))
      (node (ref "U$70") (pin "P$2") (pinfunction "-_P$2") (pintype "bidirectional"))
      (node (ref "U$71") (pin "P$2") (pinfunction "-_P$2") (pintype "bidirectional"))
      (node (ref "U$72") (pin "P$2") (pinfunction "-_P$2") (pintype "bidirectional"))
      (node (ref "U$73") (pin "P$2") (pinfunction "-_P$2") (pintype "bidirectional"))
      (node (ref "U$75") (pin "P$2") (pinfunction "-_P$2") (pintype "bidirectional"))
      (node (ref "U$76") (pin "P$2") (pinfunction "-_P$2") (pintype "bidirectional"))
      (node (ref "U$77") (pin "P$2") (pinfunction "-_P$2") (pintype "bidirectional"))
      (node (ref "U$78") (pin "P$2") (pinfunction "-_P$2") (pintype "bidirectional"))
      (node (ref "U$79") (pin "P$2") (pinfunction "-_P$2") (pintype "bidirectional"))
      (node (ref "U$8") (pin "P$1") (pinfunction "GND_P$1") (pintype "bidirectional"))
      (node (ref "U$80") (pin "P$2") (pinfunction "-_P$2") (pintype "bidirectional"))
      (node (ref "U$81") (pin "P$2") (pinfunction "-_P$2") (pintype "bidirectional"))
      (node (ref "U$82") (pin "P$2") (pinfunction "-_P$2") (pintype "bidirectional"))
      (node (ref "U$83") (pin "P$2") (pinfunction "-_P$2") (pintype "bidirectional"))
      (node (ref "U$84") (pin "P$2") (pinfunction "-_P$2") (pintype "bidirectional"))
      (node (ref "U$85") (pin "P$2") (pinfunction "-_P$2") (pintype "bidirectional"))
      (node (ref "U$86") (pin "P$2") (pinfunction "-_P$2") (pintype "bidirectional"))
      (node (ref "U$87") (pin "P$2") (pinfunction "-_P$2") (pintype "bidirectional"))
      (node (ref "U$88") (pin "P$2") (pinfunction "-_P$2") (pintype "bidirectional"))
      (node (ref "U$89") (pin "P$2") (pinfunction "-_P$2") (pintype "bidirectional"))
      (node (ref "U$9") (pin "P$1") (pinfunction "GND_P$1") (pintype "bidirectional"))
      (node (ref "U$90") (pin "P$2") (pinfunction "-_P$2") (pintype "bidirectional"))
      (node (ref "U$91") (pin "P$2") (pinfunction "-_P$2") (pintype "bidirectional"))
      (node (ref "U$92") (pin "P$2") (pinfunction "-_P$2") (pintype "bidirectional"))
      (node (ref "U$93") (pin "P$2") (pinfunction "-_P$2") (pintype "bidirectional"))
      (node (ref "U$94") (pin "P$2") (pinfunction "-_P$2") (pintype "bidirectional"))
      (node (ref "U$95") (pin "P$2") (pinfunction "-_P$2") (pintype "bidirectional"))
      (node (ref "U$96") (pin "P$2") (pinfunction "-_P$2") (pintype "bidirectional"))
      (node (ref "U$97") (pin "P$2") (pinfunction "-_P$2") (pintype "bidirectional"))
      (node (ref "U$98") (pin "P$2") (pinfunction "-_P$2") (pintype "bidirectional"))
      (node (ref "U$99") (pin "P$2") (pinfunction "-_P$2") (pintype "bidirectional"))
      (node (ref "U1") (pin "P$24") (pinfunction "GND_P$24") (pintype "bidirectional"))
      (node (ref "U1") (pin "P$43") (pinfunction "GND_P$43") (pintype "bidirectional"))
      (node (ref "U1") (pin "P$5") (pinfunction "GND_P$5") (pintype "bidirectional"))
    )
    (net (code "66") (name "/GPIO_2") (class "Default")
      (node (ref "JP1") (pin "2") (pinfunction "P$2_2") (pintype "bidirectional"))
      (node (ref "JP2") (pin "2") (pinfunction "P$2_2") (pintype "bidirectional"))
      (node (ref "JP3") (pin "2") (pinfunction "P$2_2") (pintype "bidirectional"))
      (node (ref "JP4") (pin "2") (pinfunction "P$2_2") (pintype "bidirectional"))
    )
    (net (code "67") (name "/GPIO_22") (class "Default")
      (node (ref "JP1") (pin "22") (pinfunction "P$22_22") (pintype "bidirectional"))
      (node (ref "JP2") (pin "22") (pinfunction "P$22_22") (pintype "bidirectional"))
      (node (ref "JP3") (pin "22") (pinfunction "P$22_22") (pintype "bidirectional"))
      (node (ref "JP4") (pin "22") (pinfunction "P$22_22") (pintype "bidirectional"))
    )
    (net (code "68") (name "/GPIO_63") (class "Default")
      (node (ref "JP1") (pin "63") (pinfunction "P$63_63") (pintype "bidirectional"))
      (node (ref "JP2") (pin "63") (pinfunction "P$63_63") (pintype "bidirectional"))
      (node (ref "JP3") (pin "63") (pinfunction "P$63_63") (pintype "bidirectional"))
      (node (ref "JP4") (pin "63") (pinfunction "P$63_63") (pintype "bidirectional"))
    )
    (net (code "69") (name "/HUB_USB_N") (class "Default")
      (node (ref "2PIN_1") (pin "P$2") (pinfunction "P$2_P$2") (pintype "bidirectional"))
      (node (ref "R17") (pin "1") (pinfunction "1_1") (pintype "passive"))
      (node (ref "U$2") (pin "P$3") (pinfunction "I/O_2_P$3") (pintype "bidirectional"))
    )
    (net (code "70") (name "/HUB_USB_P") (class "Default")
      (node (ref "2PIN_1") (pin "P$1") (pinfunction "P$1_P$1") (pintype "bidirectional"))
      (node (ref "R3") (pin "1") (pinfunction "1_1") (pintype "passive"))
      (node (ref "R72") (pin "1") (pinfunction "1_1") (pintype "passive"))
      (node (ref "U$2") (pin "P$2") (pinfunction "I/O_1_P$2") (pintype "bidirectional"))
    )
    (net (code "71") (name "/HUB_USB_XTAL") (class "Default")
      (node (ref "U$33") (pin "P$3") (pinfunction "OUT_P$3") (pintype "bidirectional"))
      (node (ref "U1") (pin "P$45") (pinfunction "XTAL1/CLK48_P$45") (pintype "bidirectional"))
    )
    (net (code "72") (name "/IMU_USB_N") (class "Default")
      (node (ref "2PIN_3") (pin "P$2") (pinfunction "P$2_P$2") (pintype "bidirectional"))
      (node (ref "U$10") (pin "D+") (pinfunction "3_D+") (pintype "bidirectional"))
      (node (ref "U$3") (pin "P$3") (pinfunction "I/O_2_P$3") (pintype "bidirectional"))
      (node (ref "U$9") (pin "P$3") (pinfunction "I/O_2_P$3") (pintype "bidirectional"))
    )
    (net (code "73") (name "/IMU_USB_P") (class "Default")
      (node (ref "2PIN_3") (pin "P$1") (pinfunction "P$1_P$1") (pintype "bidirectional"))
      (node (ref "U$10") (pin "D-") (pinfunction "2_D-") (pintype "bidirectional"))
      (node (ref "U$3") (pin "P$2") (pinfunction "I/O_1_P$2") (pintype "bidirectional"))
      (node (ref "U$9") (pin "P$2") (pinfunction "I/O_1_P$2") (pintype "bidirectional"))
    )
    (net (code "74") (name "/INT_SCL") (class "Default")
      (node (ref "2PIN_6") (pin "P$1") (pinfunction "P$1_P$1") (pintype "bidirectional"))
      (node (ref "JP1") (pin "65") (pinfunction "P$65_65") (pintype "bidirectional"))
      (node (ref "JP2") (pin "65") (pinfunction "P$65_65") (pintype "bidirectional"))
      (node (ref "JP3") (pin "65") (pinfunction "P$65_65") (pintype "bidirectional"))
      (node (ref "JP4") (pin "65") (pinfunction "P$65_65") (pintype "bidirectional"))
      (node (ref "U$18") (pin "P$2") (pinfunction "I/O_1_P$2") (pintype "bidirectional"))
      (node (ref "U$50") (pin "2") (pinfunction "LX_2") (pintype "bidirectional"))
    )
    (net (code "75") (name "/INT_SDA") (class "Default")
      (node (ref "2PIN_6") (pin "P$2") (pinfunction "P$2_P$2") (pintype "bidirectional"))
      (node (ref "JP1") (pin "64") (pinfunction "P$64_64") (pintype "bidirectional"))
      (node (ref "JP2") (pin "64") (pinfunction "P$64_64") (pintype "bidirectional"))
      (node (ref "JP3") (pin "64") (pinfunction "P$64_64") (pintype "bidirectional"))
      (node (ref "JP4") (pin "64") (pinfunction "P$64_64") (pintype "bidirectional"))
      (node (ref "U$18") (pin "P$3") (pinfunction "I/O_2_P$3") (pintype "bidirectional"))
      (node (ref "U$50") (pin "7") (pinfunction "LY_7") (pintype "bidirectional"))
    )
    (net (code "76") (name "/MISO") (class "Default")
      (node (ref "4PIN_7") (pin "P$3") (pinfunction "P$3_P$3") (pintype "bidirectional"))
      (node (ref "JP1") (pin "72") (pinfunction "P$72_72") (pintype "bidirectional"))
      (node (ref "JP2") (pin "72") (pinfunction "P$72_72") (pintype "bidirectional"))
      (node (ref "JP3") (pin "72") (pinfunction "P$72_72") (pintype "bidirectional"))
      (node (ref "JP4") (pin "72") (pinfunction "P$72_72") (pintype "bidirectional"))
      (node (ref "U$15") (pin "P$5") (pinfunction "P$5_P$5") (pintype "bidirectional"))
      (node (ref "U$19") (pin "P$3") (pinfunction "I/O_2_P$3") (pintype "bidirectional"))
      (node (ref "U$27") (pin "P$3") (pinfunction "I/O_2_P$3") (pintype "bidirectional"))
    )
    (net (code "77") (name "/MOSI") (class "Default")
      (node (ref "4PIN_7") (pin "P$4") (pinfunction "P$4_P$4") (pintype "bidirectional"))
      (node (ref "JP1") (pin "71") (pinfunction "P$71_71") (pintype "bidirectional"))
      (node (ref "JP2") (pin "71") (pinfunction "P$71_71") (pintype "bidirectional"))
      (node (ref "JP3") (pin "71") (pinfunction "P$71_71") (pintype "bidirectional"))
      (node (ref "JP4") (pin "71") (pinfunction "P$71_71") (pintype "bidirectional"))
      (node (ref "U$15") (pin "P$6") (pinfunction "P$6_P$6") (pintype "bidirectional"))
      (node (ref "U$19") (pin "P$2") (pinfunction "I/O_1_P$2") (pintype "bidirectional"))
      (node (ref "U$27") (pin "P$2") (pinfunction "I/O_1_P$2") (pintype "bidirectional"))
    )
    (net (code "78") (name "/PWM_0") (class "Default")
      (node (ref "JP1") (pin "31") (pinfunction "P$31_31") (pintype "bidirectional"))
      (node (ref "JP2") (pin "31") (pinfunction "P$31_31") (pintype "bidirectional"))
      (node (ref "JP3") (pin "31") (pinfunction "P$31_31") (pintype "bidirectional"))
      (node (ref "JP4") (pin "31") (pinfunction "P$31_31") (pintype "bidirectional"))
    )
    (net (code "79") (name "/PWM_1") (class "Default")
      (node (ref "JP1") (pin "26") (pinfunction "P$26_26") (pintype "bidirectional"))
      (node (ref "JP2") (pin "26") (pinfunction "P$26_26") (pintype "bidirectional"))
      (node (ref "JP3") (pin "26") (pinfunction "P$26_26") (pintype "bidirectional"))
      (node (ref "JP4") (pin "26") (pinfunction "P$26_26") (pintype "bidirectional"))
    )
    (net (code "80") (name "/RTS_CF") (class "Default")
      (node (ref "4PIN_2") (pin "P$2") (pinfunction "P$2_P$2") (pintype "bidirectional"))
      (node (ref "JP1") (pin "14") (pinfunction "P$14_14") (pintype "bidirectional"))
      (node (ref "JP2") (pin "14") (pinfunction "P$14_14") (pintype "bidirectional"))
      (node (ref "JP3") (pin "14") (pinfunction "P$14_14") (pintype "bidirectional"))
      (node (ref "JP4") (pin "14") (pinfunction "P$14_14") (pintype "bidirectional"))
    )
    (net (code "81") (name "/RTS_MC") (class "Default")
      (node (ref "4PIN_1") (pin "P$2") (pinfunction "P$2_P$2") (pintype "bidirectional"))
      (node (ref "JP1") (pin "30") (pinfunction "P$30_30") (pintype "bidirectional"))
      (node (ref "JP2") (pin "30") (pinfunction "P$30_30") (pintype "bidirectional"))
      (node (ref "JP3") (pin "30") (pinfunction "P$30_30") (pintype "bidirectional"))
      (node (ref "JP4") (pin "30") (pinfunction "P$30_30") (pintype "bidirectional"))
    )
    (net (code "82") (name "/RTS_MD") (class "Default")
      (node (ref "5.2") (pin "P$3") (pinfunction "P$2_P$3") (pintype "bidirectional"))
      (node (ref "5.2") (pin "P$4") (pinfunction "P$2_P$4") (pintype "bidirectional"))
      (node (ref "JP1") (pin "69") (pinfunction "P$69_69") (pintype "bidirectional"))
      (node (ref "JP2") (pin "69") (pinfunction "P$69_69") (pintype "bidirectional"))
      (node (ref "JP3") (pin "69") (pinfunction "P$69_69") (pintype "bidirectional"))
      (node (ref "JP4") (pin "69") (pinfunction "P$69_69") (pintype "bidirectional"))
      (node (ref "U$55") (pin "P$2") (pinfunction "I/O_1_P$2") (pintype "bidirectional"))
    )
    (net (code "83") (name "/RTS_MF") (class "Default")
      (node (ref "JP1") (pin "6") (pinfunction "P$6_6") (pintype "bidirectional"))
      (node (ref "JP2") (pin "6") (pinfunction "P$6_6") (pintype "bidirectional"))
      (node (ref "JP3") (pin "6") (pinfunction "P$6_6") (pintype "bidirectional"))
      (node (ref "JP4") (pin "6") (pinfunction "P$6_6") (pintype "bidirectional"))
    )
    (net (code "84") (name "/RTS_PF") (class "Default")
      (node (ref "JP1") (pin "10") (pinfunction "P$10_10") (pintype "bidirectional"))
      (node (ref "JP2") (pin "10") (pinfunction "P$10_10") (pintype "bidirectional"))
      (node (ref "JP3") (pin "10") (pinfunction "P$10_10") (pintype "bidirectional"))
      (node (ref "JP4") (pin "10") (pinfunction "P$10_10") (pintype "bidirectional"))
    )
    (net (code "85") (name "/RTS_SF") (class "Default")
      (node (ref "JP1") (pin "51") (pinfunction "P$51_51") (pintype "bidirectional"))
      (node (ref "JP2") (pin "51") (pinfunction "P$51_51") (pintype "bidirectional"))
      (node (ref "JP3") (pin "51") (pinfunction "P$51_51") (pintype "bidirectional"))
      (node (ref "JP4") (pin "51") (pinfunction "P$51_51") (pintype "bidirectional"))
    )
    (net (code "86") (name "/RX_CF") (class "Default")
      (node (ref "4PIN_2") (pin "P$4") (pinfunction "P$4_P$4") (pintype "bidirectional"))
      (node (ref "JP1") (pin "11") (pinfunction "P$11_11") (pintype "bidirectional"))
      (node (ref "JP2") (pin "11") (pinfunction "P$11_11") (pintype "bidirectional"))
      (node (ref "JP3") (pin "11") (pinfunction "P$11_11") (pintype "bidirectional"))
      (node (ref "JP4") (pin "11") (pinfunction "P$11_11") (pintype "bidirectional"))
      (node (ref "U$8") (pin "P$2") (pinfunction "I/O_1_P$2") (pintype "bidirectional"))
    )
    (net (code "87") (name "/RX_MC") (class "Default")
      (node (ref "4PIN_1") (pin "P$4") (pinfunction "P$4_P$4") (pintype "bidirectional"))
      (node (ref "JP1") (pin "27") (pinfunction "P$27_27") (pintype "bidirectional"))
      (node (ref "JP2") (pin "27") (pinfunction "P$27_27") (pintype "bidirectional"))
      (node (ref "JP3") (pin "27") (pinfunction "P$27_27") (pintype "bidirectional"))
      (node (ref "JP4") (pin "27") (pinfunction "P$27_27") (pintype "bidirectional"))
      (node (ref "U$4") (pin "P$3") (pinfunction "I/O_2_P$3") (pintype "bidirectional"))
    )
    (net (code "88") (name "/RX_MD") (class "Default")
      (node (ref "5.2") (pin "P$10") (pinfunction "P$5_P$10") (pintype "bidirectional"))
      (node (ref "5.2") (pin "P$9") (pinfunction "P$5_P$9") (pintype "bidirectional"))
      (node (ref "JP1") (pin "66") (pinfunction "P$66_66") (pintype "bidirectional"))
      (node (ref "JP2") (pin "66") (pinfunction "P$66_66") (pintype "bidirectional"))
      (node (ref "JP3") (pin "66") (pinfunction "P$66_66") (pintype "bidirectional"))
      (node (ref "JP4") (pin "66") (pinfunction "P$66_66") (pintype "bidirectional"))
      (node (ref "U$54") (pin "P$2") (pinfunction "I/O_1_P$2") (pintype "bidirectional"))
    )
    (net (code "89") (name "/RX_MF") (class "Default")
      (node (ref "JP1") (pin "3") (pinfunction "P$3_3") (pintype "bidirectional"))
      (node (ref "JP2") (pin "3") (pinfunction "P$3_3") (pintype "bidirectional"))
      (node (ref "JP3") (pin "3") (pinfunction "P$3_3") (pintype "bidirectional"))
      (node (ref "JP4") (pin "3") (pinfunction "P$3_3") (pintype "bidirectional"))
    )
    (net (code "90") (name "/RX_PF") (class "Default")
      (node (ref "JP1") (pin "7") (pinfunction "P$7_7") (pintype "bidirectional"))
      (node (ref "JP2") (pin "7") (pinfunction "P$7_7") (pintype "bidirectional"))
      (node (ref "JP3") (pin "7") (pinfunction "P$7_7") (pintype "bidirectional"))
      (node (ref "JP4") (pin "7") (pinfunction "P$7_7") (pintype "bidirectional"))
    )
    (net (code "91") (name "/RX_SF") (class "Default")
      (node (ref "JP1") (pin "48") (pinfunction "P$48_48") (pintype "bidirectional"))
      (node (ref "JP2") (pin "48") (pinfunction "P$48_48") (pintype "bidirectional"))
      (node (ref "JP3") (pin "48") (pinfunction "P$48_48") (pintype "bidirectional"))
      (node (ref "JP4") (pin "48") (pinfunction "P$48_48") (pintype "bidirectional"))
    )
    (net (code "92") (name "/SCL_1_UNBUF") (class "Default")
      (node (ref "R8") (pin "2") (pinfunction "2_2") (pintype "passive"))
      (node (ref "U$46") (pin "P$6") (pinfunction "SCL2_P$6") (pintype "bidirectional"))
      (node (ref "U$50") (pin "3") (pinfunction "SX_3") (pintype "bidirectional"))
    )
    (net (code "93") (name "/SDA_1_UNBUF") (class "Default")
      (node (ref "R9") (pin "2") (pinfunction "2_2") (pintype "passive"))
      (node (ref "U$46") (pin "P$5") (pinfunction "SDA2_P$5") (pintype "bidirectional"))
      (node (ref "U$50") (pin "6") (pinfunction "SY_6") (pintype "bidirectional"))
    )
    (net (code "94") (name "/SHORE_SCL") (class "Default")
      (node (ref "5.4") (pin "P$7") (pinfunction "P$4_P$7") (pintype "bidirectional"))
      (node (ref "5.4") (pin "P$8") (pinfunction "P$4_P$8") (pintype "bidirectional"))
      (node (ref "U$40") (pin "7") (pinfunction "LY_7") (pintype "bidirectional"))
      (node (ref "U$60") (pin "P$2") (pinfunction "I/O_1_P$2") (pintype "bidirectional"))
    )
    (net (code "95") (name "/SHORE_SCL_UNBUF") (class "Default")
      (node (ref "BATTERY-MUX") (pin "P$5") (pinfunction "SC0_P$5") (pintype "bidirectional"))
      (node (ref "U$40") (pin "6") (pinfunction "SY_6") (pintype "bidirectional"))
    )
    (net (code "96") (name "/SHORE_SDA") (class "Default")
      (node (ref "5.5") (pin "P$7") (pinfunction "P$4_P$7") (pintype "bidirectional"))
      (node (ref "5.5") (pin "P$8") (pinfunction "P$4_P$8") (pintype "bidirectional"))
      (node (ref "U$40") (pin "2") (pinfunction "LX_2") (pintype "bidirectional"))
      (node (ref "U$60") (pin "P$3") (pinfunction "I/O_2_P$3") (pintype "bidirectional"))
    )
    (net (code "97") (name "/SHORE_SDA_UNBUF") (class "Default")
      (node (ref "BATTERY-MUX") (pin "P$4") (pinfunction "SD0_P$4") (pintype "bidirectional"))
      (node (ref "U$40") (pin "3") (pinfunction "SX_3") (pintype "bidirectional"))
    )
    (net (code "98") (name "/SPI_CLK") (class "Default")
      (node (ref "4PIN_7") (pin "P$1") (pinfunction "P$1_P$1") (pintype "bidirectional"))
      (node (ref "JP1") (pin "70") (pinfunction "P$70_70") (pintype "bidirectional"))
      (node (ref "JP2") (pin "70") (pinfunction "P$70_70") (pintype "bidirectional"))
      (node (ref "JP3") (pin "70") (pinfunction "P$70_70") (pintype "bidirectional"))
      (node (ref "JP4") (pin "70") (pinfunction "P$70_70") (pintype "bidirectional"))
      (node (ref "U$15") (pin "P$4") (pinfunction "P$4_P$4") (pintype "bidirectional"))
      (node (ref "U$28") (pin "P$2") (pinfunction "I/O_1_P$2") (pintype "bidirectional"))
    )
    (net (code "99") (name "/TX_CF") (class "Default")
      (node (ref "4PIN_2") (pin "P$3") (pinfunction "P$3_P$3") (pintype "bidirectional"))
      (node (ref "JP1") (pin "12") (pinfunction "P$12_12") (pintype "bidirectional"))
      (node (ref "JP2") (pin "12") (pinfunction "P$12_12") (pintype "bidirectional"))
      (node (ref "JP3") (pin "12") (pinfunction "P$12_12") (pintype "bidirectional"))
      (node (ref "JP4") (pin "12") (pinfunction "P$12_12") (pintype "bidirectional"))
      (node (ref "U$8") (pin "P$3") (pinfunction "I/O_2_P$3") (pintype "bidirectional"))
    )
    (net (code "100") (name "/TX_MC") (class "Default")
      (node (ref "4PIN_1") (pin "P$3") (pinfunction "P$3_P$3") (pintype "bidirectional"))
      (node (ref "JP1") (pin "28") (pinfunction "P$28_28") (pintype "bidirectional"))
      (node (ref "JP2") (pin "28") (pinfunction "P$28_28") (pintype "bidirectional"))
      (node (ref "JP3") (pin "28") (pinfunction "P$28_28") (pintype "bidirectional"))
      (node (ref "JP4") (pin "28") (pinfunction "P$28_28") (pintype "bidirectional"))
      (node (ref "U$4") (pin "P$2") (pinfunction "I/O_1_P$2") (pintype "bidirectional"))
    )
    (net (code "101") (name "/TX_MD") (class "Default")
      (node (ref "5.2") (pin "P$7") (pinfunction "P$4_P$7") (pintype "bidirectional"))
      (node (ref "5.2") (pin "P$8") (pinfunction "P$4_P$8") (pintype "bidirectional"))
      (node (ref "JP1") (pin "67") (pinfunction "P$67_67") (pintype "bidirectional"))
      (node (ref "JP2") (pin "67") (pinfunction "P$67_67") (pintype "bidirectional"))
      (node (ref "JP3") (pin "67") (pinfunction "P$67_67") (pintype "bidirectional"))
      (node (ref "JP4") (pin "67") (pinfunction "P$67_67") (pintype "bidirectional"))
      (node (ref "U$54") (pin "P$3") (pinfunction "I/O_2_P$3") (pintype "bidirectional"))
    )
    (net (code "102") (name "/TX_MF") (class "Default")
      (node (ref "JP1") (pin "4") (pinfunction "P$4_4") (pintype "bidirectional"))
      (node (ref "JP2") (pin "4") (pinfunction "P$4_4") (pintype "bidirectional"))
      (node (ref "JP3") (pin "4") (pinfunction "P$4_4") (pintype "bidirectional"))
      (node (ref "JP4") (pin "4") (pinfunction "P$4_4") (pintype "bidirectional"))
    )
    (net (code "103") (name "/TX_PF") (class "Default")
      (node (ref "JP1") (pin "8") (pinfunction "P$8_8") (pintype "bidirectional"))
      (node (ref "JP2") (pin "8") (pinfunction "P$8_8") (pintype "bidirectional"))
      (node (ref "JP3") (pin "8") (pinfunction "P$8_8") (pintype "bidirectional"))
      (node (ref "JP4") (pin "8") (pinfunction "P$8_8") (pintype "bidirectional"))
    )
    (net (code "104") (name "/TX_SF") (class "Default")
      (node (ref "JP1") (pin "49") (pinfunction "P$49_49") (pintype "bidirectional"))
      (node (ref "JP2") (pin "49") (pinfunction "P$49_49") (pintype "bidirectional"))
      (node (ref "JP3") (pin "49") (pinfunction "P$49_49") (pintype "bidirectional"))
      (node (ref "JP4") (pin "49") (pinfunction "P$49_49") (pintype "bidirectional"))
    )
    (net (code "105") (name "/USB-5_P") (class "Default")
      (node (ref "R31") (pin "2") (pinfunction "2_2") (pintype "passive"))
      (node (ref "R44") (pin "1") (pinfunction "1_1") (pintype "passive"))
    )
    (net (code "106") (name "/USB_1_N") (class "Default")
      (node (ref "JP1") (pin "61") (pinfunction "P$61_61") (pintype "bidirectional"))
      (node (ref "R2") (pin "1") (pinfunction "1_1") (pintype "passive"))
      (node (ref "R22") (pin "1") (pinfunction "1_1") (pintype "passive"))
      (node (ref "U$29") (pin "P$3") (pinfunction "I/O_2_P$3") (pintype "bidirectional"))
    )
    (net (code "107") (name "/USB_1_P") (class "Default")
      (node (ref "JP1") (pin "41") (pinfunction "P$41_41") (pintype "bidirectional"))
      (node (ref "R23") (pin "1") (pinfunction "1_1") (pintype "passive"))
      (node (ref "R36") (pin "1") (pinfunction "1_1") (pintype "passive"))
      (node (ref "U$29") (pin "P$2") (pinfunction "I/O_1_P$2") (pintype "bidirectional"))
    )
    (net (code "108") (name "/USB_2_N") (class "Default")
      (node (ref "JP2") (pin "61") (pinfunction "P$61_61") (pintype "bidirectional"))
      (node (ref "R24") (pin "1") (pinfunction "1_1") (pintype "passive"))
      (node (ref "R37") (pin "1") (pinfunction "1_1") (pintype "passive"))
      (node (ref "U$30") (pin "P$3") (pinfunction "I/O_2_P$3") (pintype "bidirectional"))
    )
    (net (code "109") (name "/USB_2_P") (class "Default")
      (node (ref "JP2") (pin "41") (pinfunction "P$41_41") (pintype "bidirectional"))
      (node (ref "R25") (pin "1") (pinfunction "1_1") (pintype "passive"))
      (node (ref "R38") (pin "1") (pinfunction "1_1") (pintype "passive"))
      (node (ref "U$30") (pin "P$2") (pinfunction "I/O_1_P$2") (pintype "bidirectional"))
    )
    (net (code "110") (name "/USB_3_N") (class "Default")
      (node (ref "JP3") (pin "61") (pinfunction "P$61_61") (pintype "bidirectional"))
      (node (ref "R27") (pin "2") (pinfunction "2_2") (pintype "passive"))
      (node (ref "R40") (pin "1") (pinfunction "1_1") (pintype "passive"))
      (node (ref "U$31") (pin "P$3") (pinfunction "I/O_2_P$3") (pintype "bidirectional"))
    )
    (net (code "111") (name "/USB_3_P") (class "Default")
      (node (ref "JP3") (pin "41") (pinfunction "P$41_41") (pintype "bidirectional"))
      (node (ref "R26") (pin "2") (pinfunction "2_2") (pintype "passive"))
      (node (ref "R39") (pin "1") (pinfunction "1_1") (pintype "passive"))
      (node (ref "U$31") (pin "P$2") (pinfunction "I/O_1_P$2") (pintype "bidirectional"))
    )
    (net (code "112") (name "/USB_4_N") (class "Default")
      (node (ref "JP4") (pin "61") (pinfunction "P$61_61") (pintype "bidirectional"))
      (node (ref "R28") (pin "2") (pinfunction "2_2") (pintype "passive"))
      (node (ref "R41") (pin "1") (pinfunction "1_1") (pintype "passive"))
      (node (ref "U$32") (pin "P$3") (pinfunction "I/O_2_P$3") (pintype "bidirectional"))
    )
    (net (code "113") (name "/USB_4_P") (class "Default")
      (node (ref "JP4") (pin "41") (pinfunction "P$41_41") (pintype "bidirectional"))
      (node (ref "R29") (pin "2") (pinfunction "2_2") (pintype "passive"))
      (node (ref "R42") (pin "1") (pinfunction "1_1") (pintype "passive"))
      (node (ref "U$32") (pin "P$2") (pinfunction "I/O_1_P$2") (pintype "bidirectional"))
    )
    (net (code "114") (name "/USB_5_5V") (class "Default")
      (node (ref "D40") (pin "C") (pinfunction "C_C") (pintype "passive"))
      (node (ref "G1") (pin "OUT1") (pinfunction "OUT1_OUT1") (pintype "bidirectional"))
      (node (ref "U$107") (pin "1") (pinfunction "P$1_1") (pintype "bidirectional"))
      (node (ref "U$24") (pin "P$2") (pinfunction "P$2_P$2") (pintype "bidirectional"))
      (node (ref "U$34") (pin "P$1") (pinfunction "+_P$1") (pintype "bidirectional"))
    )
    (net (code "115") (name "/USB_5_M") (class "Default")
      (node (ref "R30") (pin "2") (pinfunction "2_2") (pintype "passive"))
      (node (ref "R43") (pin "1") (pinfunction "1_1") (pintype "passive"))
      (node (ref "U$14") (pin "D+") (pinfunction "3_D+") (pintype "bidirectional"))
      (node (ref "U$22") (pin "P$3") (pinfunction "I/O_2_P$3") (pintype "bidirectional"))
    )
    (net (code "116") (name "/USB_5_P") (class "Default")
      (node (ref "U$14") (pin "D-") (pinfunction "2_D-") (pintype "bidirectional"))
      (node (ref "U$22") (pin "P$2") (pinfunction "I/O_1_P$2") (pintype "bidirectional"))
    )
    (net (code "117") (name "/USB_6_5V") (class "Default")
      (node (ref "D39") (pin "C") (pinfunction "C_C") (pintype "passive"))
      (node (ref "G1") (pin "OUT2") (pinfunction "OUT2_OUT2") (pintype "bidirectional"))
      (node (ref "U$102") (pin "1") (pinfunction "P$1_1") (pintype "bidirectional"))
      (node (ref "U$25") (pin "P$2") (pinfunction "P$2_P$2") (pintype "bidirectional"))
      (node (ref "U$35") (pin "P$1") (pinfunction "+_P$1") (pintype "bidirectional"))
    )
    (net (code "118") (name "/USB_6_M") (class "Default")
      (node (ref "R32") (pin "2") (pinfunction "2_2") (pintype "passive"))
      (node (ref "R45") (pin "1") (pinfunction "1_1") (pintype "passive"))
      (node (ref "U$16") (pin "D+") (pinfunction "3_D+") (pintype "bidirectional"))
      (node (ref "U$23") (pin "P$3") (pinfunction "I/O_2_P$3") (pintype "bidirectional"))
    )
    (net (code "119") (name "/USB_6_P") (class "Default")
      (node (ref "R33") (pin "2") (pinfunction "2_2") (pintype "passive"))
      (node (ref "R46") (pin "1") (pinfunction "1_1") (pintype "passive"))
      (node (ref "U$16") (pin "D-") (pinfunction "2_D-") (pintype "bidirectional"))
      (node (ref "U$23") (pin "P$2") (pinfunction "I/O_1_P$2") (pintype "bidirectional"))
    )
    (net (code "120") (name "/V_BATT") (class "Default")
      (node (ref "4PIN_3") (pin "P$1") (pinfunction "P$1_P$1") (pintype "bidirectional"))
      (node (ref "4PIN_3") (pin "P$2") (pinfunction "P$2_P$2") (pintype "bidirectional"))
      (node (ref "4PIN_3") (pin "P$3") (pinfunction "P$3_P$3") (pintype "bidirectional"))
      (node (ref "4PIN_3") (pin "P$4") (pinfunction "P$4_P$4") (pintype "bidirectional"))
      (node (ref "4PIN_4") (pin "P$1") (pinfunction "P$1_P$1") (pintype "bidirectional"))
      (node (ref "4PIN_4") (pin "P$2") (pinfunction "P$2_P$2") (pintype "bidirectional"))
      (node (ref "4PIN_4") (pin "P$3") (pinfunction "P$3_P$3") (pintype "bidirectional"))
      (node (ref "4PIN_4") (pin "P$4") (pinfunction "P$4_P$4") (pintype "bidirectional"))
      (node (ref "D14") (pin "C") (pinfunction "C_C") (pintype "passive"))
      (node (ref "D18") (pin "C") (pinfunction "C_C") (pintype "passive"))
      (node (ref "D22") (pin "C") (pinfunction "C_C") (pintype "passive"))
      (node (ref "D26") (pin "C") (pinfunction "C_C") (pintype "passive"))
      (node (ref "D28") (pin "C") (pinfunction "C_C") (pintype "passive"))
      (node (ref "D29") (pin "C") (pinfunction "C_C") (pintype "passive"))
      (node (ref "D30") (pin "C") (pinfunction "C_C") (pintype "passive"))
      (node (ref "D31") (pin "C") (pinfunction "C_C") (pintype "passive"))
      (node (ref "D32") (pin "C") (pinfunction "C_C") (pintype "passive"))
      (node (ref "D33") (pin "C") (pinfunction "C_C") (pintype "passive"))
      (node (ref "D34") (pin "C") (pinfunction "C_C") (pintype "passive"))
      (node (ref "D35") (pin "C") (pinfunction "C_C") (pintype "passive"))
      (node (ref "JP1") (pin "P2,1") (pinfunction "POWER2_P2,1") (pintype "bidirectional"))
      (node (ref "JP1") (pin "P2,2") (pinfunction "POWER2_P2,2") (pintype "bidirectional"))
      (node (ref "JP1") (pin "P2,3") (pinfunction "POWER2_P2,3") (pintype "bidirectional"))
      (node (ref "JP1") (pin "P2,4") (pinfunction "POWER2_P2,4") (pintype "bidirectional"))
      (node (ref "JP1") (pin "P2,5") (pinfunction "POWER2_P2,5") (pintype "bidirectional"))
      (node (ref "JP1") (pin "P2,6") (pinfunction "POWER2_P2,6") (pintype "bidirectional"))
      (node (ref "JP2") (pin "P2,1") (pinfunction "POWER2_P2,1") (pintype "bidirectional"))
      (node (ref "JP2") (pin "P2,2") (pinfunction "POWER2_P2,2") (pintype "bidirectional"))
      (node (ref "JP2") (pin "P2,3") (pinfunction "POWER2_P2,3") (pintype "bidirectional"))
      (node (ref "JP2") (pin "P2,4") (pinfunction "POWER2_P2,4") (pintype "bidirectional"))
      (node (ref "JP2") (pin "P2,5") (pinfunction "POWER2_P2,5") (pintype "bidirectional"))
      (node (ref "JP2") (pin "P2,6") (pinfunction "POWER2_P2,6") (pintype "bidirectional"))
      (node (ref "JP3") (pin "P2,1") (pinfunction "POWER2_P2,1") (pintype "bidirectional"))
      (node (ref "JP3") (pin "P2,2") (pinfunction "POWER2_P2,2") (pintype "bidirectional"))
      (node (ref "JP3") (pin "P2,3") (pinfunction "POWER2_P2,3") (pintype "bidirectional"))
      (node (ref "JP3") (pin "P2,4") (pinfunction "POWER2_P2,4") (pintype "bidirectional"))
      (node (ref "JP3") (pin "P2,5") (pinfunction "POWER2_P2,5") (pintype "bidirectional"))
      (node (ref "JP3") (pin "P2,6") (pinfunction "POWER2_P2,6") (pintype "bidirectional"))
      (node (ref "JP4") (pin "P2,1") (pinfunction "POWER2_P2,1") (pintype "bidirectional"))
      (node (ref "JP4") (pin "P2,2") (pinfunction "POWER2_P2,2") (pintype "bidirectional"))
      (node (ref "JP4") (pin "P2,3") (pinfunction "POWER2_P2,3") (pintype "bidirectional"))
      (node (ref "JP4") (pin "P2,4") (pinfunction "POWER2_P2,4") (pintype "bidirectional"))
      (node (ref "JP4") (pin "P2,5") (pinfunction "POWER2_P2,5") (pintype "bidirectional"))
      (node (ref "JP4") (pin "P2,6") (pinfunction "POWER2_P2,6") (pintype "bidirectional"))
      (node (ref "U$78") (pin "P$1") (pinfunction "+_P$1") (pintype "bidirectional"))
      (node (ref "U$82") (pin "P$1") (pinfunction "+_P$1") (pintype "bidirectional"))
      (node (ref "U$86") (pin "P$1") (pinfunction "+_P$1") (pintype "bidirectional"))
      (node (ref "U$90") (pin "P$1") (pinfunction "+_P$1") (pintype "bidirectional"))
      (node (ref "U$92") (pin "P$1") (pinfunction "+_P$1") (pintype "bidirectional"))
      (node (ref "U$93") (pin "P$1") (pinfunction "+_P$1") (pintype "bidirectional"))
      (node (ref "U$94") (pin "P$1") (pinfunction "+_P$1") (pintype "bidirectional"))
      (node (ref "U$95") (pin "P$1") (pinfunction "+_P$1") (pintype "bidirectional"))
      (node (ref "U$96") (pin "P$1") (pinfunction "+_P$1") (pintype "bidirectional"))
      (node (ref "U$97") (pin "P$1") (pinfunction "+_P$1") (pintype "bidirectional"))
      (node (ref "U$98") (pin "P$1") (pinfunction "+_P$1") (pintype "bidirectional"))
      (node (ref "U$99") (pin "P$1") (pinfunction "+_P$1") (pintype "bidirectional"))
    )
    (net (code "121") (name "/~{EXT_USB_OVERCUR}") (class "Default")
      (node (ref "G1") (pin "!OC3!") (pinfunction "~{OC3}_!OC3!") (pintype "bidirectional"))
      (node (ref "R66") (pin "1") (pinfunction "1_1") (pintype "passive"))
      (node (ref "U1") (pin "P$37") (pinfunction "~{OVERCUR7}_P$37") (pintype "bidirectional"))
    )
    (net (code "122") (name "/~{EXT_USB_PWR}") (class "Default")
      (node (ref "G1") (pin "!EN3!") (pinfunction "~{EN3}_!EN3!") (pintype "bidirectional"))
      (node (ref "U1") (pin "P$36") (pinfunction "~{PWRON7}_P$36") (pintype "bidirectional"))
    )
    (net (code "123") (name "/~{USB_5_OVERCUR}") (class "Default")
      (node (ref "G1") (pin "!OC1!") (pinfunction "~{OC1}_!OC1!") (pintype "bidirectional"))
      (node (ref "R64") (pin "2") (pinfunction "2_2") (pintype "passive"))
      (node (ref "U1") (pin "P$29") (pinfunction "~{OVERCUR5}_P$29") (pintype "bidirectional"))
    )
    (net (code "124") (name "/~{USB_5_PWR}") (class "Default")
      (node (ref "G1") (pin "!EN1!") (pinfunction "~{EN1}_!EN1!") (pintype "bidirectional"))
      (node (ref "U1") (pin "P$28") (pinfunction "~{PWRON5}_P$28") (pintype "bidirectional"))
    )
    (net (code "125") (name "/~{USB_6_OVERCUR}") (class "Default")
      (node (ref "G1") (pin "!OC2!") (pinfunction "~{OC2}_!OC2!") (pintype "bidirectional"))
      (node (ref "R65") (pin "1") (pinfunction "1_1") (pintype "passive"))
      (node (ref "U1") (pin "P$33") (pinfunction "~{OVERCUR6}_P$33") (pintype "bidirectional"))
    )
    (net (code "126") (name "/~{USB_6_PWR}") (class "Default")
      (node (ref "G1") (pin "!EN2!") (pinfunction "~{EN2}_!EN2!") (pintype "bidirectional"))
      (node (ref "U1") (pin "P$32") (pinfunction "~{PWRON6}_P$32") (pintype "bidirectional"))
    )
    (net (code "127") (name "Net-(DVL_HOST_FTDI-3V3OUT)") (class "Default")
      (node (ref "C4") (pin "1") (pinfunction "1_1") (pintype "passive"))
      (node (ref "DVL_HOST_FTDI") (pin "16") (pinfunction "3V3OUT_16") (pintype "output"))
    )
    (net (code "128") (name "Net-(DVL_HOST_FTDI-CBUS0)") (class "Default")
      (node (ref "DVL_HOST_FTDI") (pin "22") (pinfunction "CBUS0_22") (pintype "bidirectional"))
      (node (ref "LED1") (pin "C") (pinfunction "C_C") (pintype "passive"))
    )
    (net (code "129") (name "Net-(DVL_HOST_FTDI-CBUS1)") (class "Default")
      (node (ref "DVL_HOST_FTDI") (pin "21") (pinfunction "CBUS1_21") (pintype "bidirectional"))
      (node (ref "LED2") (pin "C") (pinfunction "C_C") (pintype "passive"))
    )
    (net (code "130") (name "Net-(DVL_SLAVE_FTDI-3V3OUT)") (class "Default")
      (node (ref "C8") (pin "1") (pinfunction "1_1") (pintype "passive"))
      (node (ref "DVL_SLAVE_FTDI") (pin "16") (pinfunction "3V3OUT_16") (pintype "output"))
    )
    (net (code "131") (name "Net-(DVL_SLAVE_FTDI-CBUS0)") (class "Default")
      (node (ref "DVL_SLAVE_FTDI") (pin "22") (pinfunction "CBUS0_22") (pintype "bidirectional"))
      (node (ref "LED3") (pin "C") (pinfunction "C_C") (pintype "passive"))
    )
    (net (code "132") (name "Net-(DVL_SLAVE_FTDI-CBUS1)") (class "Default")
      (node (ref "DVL_SLAVE_FTDI") (pin "21") (pinfunction "CBUS1_21") (pintype "bidirectional"))
      (node (ref "LED4") (pin "C") (pinfunction "C_C") (pintype "passive"))
    )
    (net (code "133") (name "Net-(DVL_TTL-TO-RS232-C1+)") (class "Default")
      (node (ref "C18") (pin "1") (pinfunction "1_1") (pintype "passive"))
      (node (ref "DVL_TTL-TO-RS232") (pin "12") (pinfunction "C1+_12") (pintype "bidirectional"))
    )
    (net (code "134") (name "Net-(DVL_TTL-TO-RS232-C1-)") (class "Default")
      (node (ref "C18") (pin "2") (pinfunction "2_2") (pintype "passive"))
      (node (ref "DVL_TTL-TO-RS232") (pin "14") (pinfunction "C1-_14") (pintype "bidirectional"))
    )
    (net (code "135") (name "Net-(DVL_TTL-TO-RS232-C2+)") (class "Default")
      (node (ref "C20") (pin "1") (pinfunction "1_1") (pintype "passive"))
      (node (ref "DVL_TTL-TO-RS232") (pin "15") (pinfunction "C2+_15") (pintype "bidirectional"))
    )
    (net (code "136") (name "Net-(DVL_TTL-TO-RS232-C2-)") (class "Default")
      (node (ref "C20") (pin "2") (pinfunction "2_2") (pintype "passive"))
      (node (ref "DVL_TTL-TO-RS232") (pin "16") (pinfunction "C2-_16") (pintype "bidirectional"))
    )
    (net (code "137") (name "Net-(DVL_TTL-TO-RS232-V+)") (class "Default")
      (node (ref "C17") (pin "1") (pinfunction "1_1") (pintype "passive"))
      (node (ref "DVL_TTL-TO-RS232") (pin "13") (pinfunction "V+_13") (pintype "bidirectional"))
    )
    (net (code "138") (name "Net-(DVL_TTL-TO-RS232-V-)") (class "Default")
      (node (ref "C19") (pin "2") (pinfunction "2_2") (pintype "passive"))
      (node (ref "DVL_TTL-TO-RS232") (pin "17") (pinfunction "V-_17") (pintype "bidirectional"))
    )
    (net (code "139") (name "Net-(DVL_USB_HUB-CRFILT)") (class "Default")
      (node (ref "C27") (pin "1") (pinfunction "1_1") (pintype "passive"))
      (node (ref "DVL_USB_HUB") (pin "P$9") (pinfunction "CRFILT_P$9") (pintype "bidirectional"))
    )
    (net (code "140") (name "Net-(DVL_USB_HUB-HS_IND)") (class "Default")
      (node (ref "DVL_USB_HUB") (pin "P$16") (pinfunction "HS_IND_P$16") (pintype "bidirectional"))
      (node (ref "R10") (pin "2") (pinfunction "2_2") (pintype "passive"))
    )
    (net (code "141") (name "Net-(DVL_USB_HUB-NON_REM1)") (class "Default")
      (node (ref "DVL_USB_HUB") (pin "P$13") (pinfunction "NON_REM1_P$13") (pintype "bidirectional"))
      (node (ref "R15") (pin "1") (pinfunction "1_1") (pintype "passive"))
    )
    (net (code "142") (name "Net-(DVL_USB_HUB-PLLFILT)") (class "Default")
      (node (ref "C26") (pin "1") (pinfunction "1_1") (pintype "passive"))
      (node (ref "DVL_USB_HUB") (pin "P$25") (pinfunction "PLLFILT_P$25") (pintype "bidirectional"))
    )
    (net (code "143") (name "Net-(DVL_USB_HUB-RBIAS)") (class "Default")
      (node (ref "DVL_USB_HUB") (pin "P$26") (pinfunction "RBIAS_P$26") (pintype "bidirectional"))
      (node (ref "R12") (pin "2") (pinfunction "2_2") (pintype "passive"))
    )
    (net (code "144") (name "Net-(DVL_USB_HUB-RESET_N)") (class "Default")
      (node (ref "DVL_USB_HUB") (pin "P$17") (pinfunction "RESET_N_P$17") (pintype "bidirectional"))
      (node (ref "R11") (pin "1") (pinfunction "1_1") (pintype "passive"))
    )
    (net (code "145") (name "Net-(DVL_USB_HUB-SUSP_IND{slash}NON_REM0)") (class "Default")
      (node (ref "DVL_USB_HUB") (pin "P$19") (pinfunction "SUSP_IND/NON_REM0_P$19") (pintype "bidirectional"))
      (node (ref "LED7") (pin "A") (pinfunction "A_A") (pintype "passive"))
      (node (ref "R14") (pin "1") (pinfunction "1_1") (pintype "passive"))
    )
    (net (code "146") (name "Net-(DVL_USB_HUB-USBDM_DN1)") (class "Default")
      (node (ref "C47") (pin "1") (pinfunction "1_1") (pintype "passive"))
      (node (ref "DVL_USB_HUB") (pin "P$28") (pinfunction "USBDM_DN1_P$28") (pintype "bidirectional"))
      (node (ref "R57") (pin "2") (pinfunction "2_2") (pintype "passive"))
    )
    (net (code "147") (name "Net-(DVL_USB_HUB-USBDM_DN2)") (class "Default")
      (node (ref "C1") (pin "1") (pinfunction "1_1") (pintype "passive"))
      (node (ref "DVL_USB_HUB") (pin "P$2") (pinfunction "USBDM_DN2_P$2") (pintype "bidirectional"))
      (node (ref "R49") (pin "2") (pinfunction "2_2") (pintype "passive"))
    )
    (net (code "148") (name "Net-(DVL_USB_HUB-USBDM_UP)") (class "Default")
      (node (ref "C44") (pin "1") (pinfunction "1_1") (pintype "passive"))
      (node (ref "DVL_USB_HUB") (pin "P$21") (pinfunction "USBDM_UP_P$21") (pintype "bidirectional"))
      (node (ref "R51") (pin "2") (pinfunction "2_2") (pintype "passive"))
    )
    (net (code "149") (name "Net-(DVL_USB_HUB-USBDP_DN1)") (class "Default")
      (node (ref "C46") (pin "1") (pinfunction "1_1") (pintype "passive"))
      (node (ref "DVL_USB_HUB") (pin "P$1") (pinfunction "USBDP_DN1_P$1") (pintype "bidirectional"))
      (node (ref "R55") (pin "2") (pinfunction "2_2") (pintype "passive"))
    )
    (net (code "150") (name "Net-(DVL_USB_HUB-USBDP_DN2)") (class "Default")
      (node (ref "C45") (pin "1") (pinfunction "1_1") (pintype "passive"))
      (node (ref "DVL_USB_HUB") (pin "P$3") (pinfunction "USBDP_DN2_P$3") (pintype "bidirectional"))
      (node (ref "R53") (pin "2") (pinfunction "2_2") (pintype "passive"))
    )
    (net (code "151") (name "Net-(DVL_USB_HUB-USBDP_UP)") (class "Default")
      (node (ref "C48") (pin "1") (pinfunction "1_1") (pintype "passive"))
      (node (ref "DVL_USB_HUB") (pin "P$22") (pinfunction "USBDP_UP_P$22") (pintype "bidirectional"))
      (node (ref "R59") (pin "2") (pinfunction "2_2") (pintype "passive"))
    )
    (net (code "152") (name "Net-(LED1-PadA)") (class "Default")
      (node (ref "LED1") (pin "A") (pinfunction "A_A") (pintype "passive"))
      (node (ref "R4") (pin "1") (pinfunction "1_1") (pintype "passive"))
    )
    (net (code "153") (name "Net-(LED2-PadA)") (class "Default")
      (node (ref "LED2") (pin "A") (pinfunction "A_A") (pintype "passive"))
      (node (ref "R5") (pin "1") (pinfunction "1_1") (pintype "passive"))
    )
    (net (code "154") (name "Net-(LED3-PadA)") (class "Default")
      (node (ref "LED3") (pin "A") (pinfunction "A_A") (pintype "passive"))
      (node (ref "R6") (pin "1") (pinfunction "1_1") (pintype "passive"))
    )
    (net (code "155") (name "Net-(LED4-PadA)") (class "Default")
      (node (ref "LED4") (pin "A") (pinfunction "A_A") (pintype "passive"))
      (node (ref "R7") (pin "1") (pinfunction "1_1") (pintype "passive"))
    )
    (net (code "156") (name "Net-(LED7-PadC)") (class "Default")
      (node (ref "LED7") (pin "C") (pinfunction "C_C") (pintype "passive"))
      (node (ref "R13") (pin "1") (pinfunction "1_1") (pintype "passive"))
    )
    (net (code "157") (name "Net-(LED8-PadC)") (class "Default")
      (node (ref "LED8") (pin "C") (pinfunction "C_C") (pintype "passive"))
      (node (ref "LED9") (pin "A") (pinfunction "A_A") (pintype "passive"))
      (node (ref "R18") (pin "2") (pinfunction "2_2") (pintype "passive"))
    )
    (net (code "158") (name "Net-(LED10-PadC)") (class "Default")
      (node (ref "LED10") (pin "C") (pinfunction "C_C") (pintype "passive"))
      (node (ref "LED11") (pin "A") (pinfunction "A_A") (pintype "passive"))
      (node (ref "R19") (pin "2") (pinfunction "2_2") (pintype "passive"))
    )
    (net (code "159") (name "Net-(LED12-PadC)") (class "Default")
      (node (ref "LED12") (pin "C") (pinfunction "C_C") (pintype "passive"))
      (node (ref "LED13") (pin "A") (pinfunction "A_A") (pintype "passive"))
      (node (ref "R20") (pin "2") (pinfunction "2_2") (pintype "passive"))
    )
    (net (code "160") (name "Net-(LED14-PadC)") (class "Default")
      (node (ref "LED14") (pin "C") (pinfunction "C_C") (pintype "passive"))
      (node (ref "LED15") (pin "A") (pinfunction "A_A") (pintype "passive"))
      (node (ref "R21") (pin "2") (pinfunction "2_2") (pintype "passive"))
    )
    (net (code "161") (name "Net-(U$10-1)") (class "Default")
      (node (ref "R67") (pin "1") (pinfunction "1_1") (pintype "passive"))
      (node (ref "U$10") (pin "VDD") (pinfunction "1_VDD") (pintype "bidirectional"))
      (node (ref "U$17") (pin "2") (pinfunction "P$2_2") (pintype "bidirectional"))
    )
    (net (code "162") (name "Net-(U$10-4)") (class "Default")
      (node (ref "U$10") (pin "GND") (pinfunction "4_GND") (pintype "bidirectional"))
      (node (ref "U$21") (pin "2") (pinfunction "P$2_2") (pintype "bidirectional"))
    )
    (net (code "163") (name "Net-(U$26-P$2)") (class "Default")
      (node (ref "U$10") (pin "SHIELD") (pinfunction "SHIELD_SHIELD") (pintype "bidirectional"))
      (node (ref "U$10") (pin "SHIELD1") (pinfunction "SHIELD_SHIELD1") (pintype "bidirectional"))
      (node (ref "U$26") (pin "2") (pinfunction "P$2_2") (pintype "bidirectional"))
    )
    (net (code "164") (name "Net-(U$36-P$2)") (class "Default")
      (node (ref "U$36") (pin "2") (pinfunction "P$2_2") (pintype "bidirectional"))
      (node (ref "U$43") (pin "SHIELD") (pinfunction "SHIELD_SHIELD") (pintype "bidirectional"))
      (node (ref "U$43") (pin "SHIELD1") (pinfunction "SHIELD_SHIELD1") (pintype "bidirectional"))
    )
    (net (code "165") (name "Net-(U$41-P$3)") (class "Default")
      (node (ref "2PIN_4") (pin "P$2") (pinfunction "P$2_P$2") (pintype "bidirectional"))
      (node (ref "D1") (pin "A") (pinfunction "A_A") (pintype "passive"))
      (node (ref "R61") (pin "1") (pinfunction "1_1") (pintype "passive"))
      (node (ref "U$41") (pin "GATE") (pinfunction "P$3_GATE") (pintype "bidirectional"))
    )
    (net (code "166") (name "Net-(U$43-1)") (class "Default")
      (node (ref "R68") (pin "1") (pinfunction "1_1") (pintype "passive"))
      (node (ref "U$43") (pin "VDD") (pinfunction "1_VDD") (pintype "bidirectional"))
      (node (ref "U$74") (pin "2") (pinfunction "P$2_2") (pintype "bidirectional"))
    )
    (net (code "167") (name "Net-(U$46-EN)") (class "Default")
      (node (ref "R1") (pin "1") (pinfunction "1_1") (pintype "passive"))
      (node (ref "U$46") (pin "P$7") (pinfunction "VREF2_P$7") (pintype "bidirectional"))
      (node (ref "U$46") (pin "P$8") (pinfunction "EN_P$8") (pintype "bidirectional"))
      (node (ref "U$51") (pin "P$1") (pinfunction "+_P$1") (pintype "bidirectional"))
    )
    (net (code "168") (name "Net-(U$101-P$2)") (class "Default")
      (node (ref "U$101") (pin "2") (pinfunction "P$2_2") (pintype "bidirectional"))
      (node (ref "U$43") (pin "GND") (pinfunction "4_GND") (pintype "bidirectional"))
    )
    (net (code "169") (name "Net-(U$102-P$2)") (class "Default")
      (node (ref "U$102") (pin "2") (pinfunction "P$2_2") (pintype "bidirectional"))
      (node (ref "U$16") (pin "VDD") (pinfunction "1_VDD") (pintype "bidirectional"))
    )
    (net (code "170") (name "Net-(U$103-P$2)") (class "Default")
      (node (ref "U$103") (pin "2") (pinfunction "P$2_2") (pintype "bidirectional"))
      (node (ref "U$16") (pin "GND") (pinfunction "4_GND") (pintype "bidirectional"))
    )
    (net (code "171") (name "Net-(U$104-P$2)") (class "Default")
      (node (ref "U$104") (pin "2") (pinfunction "P$2_2") (pintype "bidirectional"))
      (node (ref "U$16") (pin "SHIELD") (pinfunction "SHIELD_SHIELD") (pintype "bidirectional"))
      (node (ref "U$16") (pin "SHIELD1") (pinfunction "SHIELD_SHIELD1") (pintype "bidirectional"))
    )
    (net (code "172") (name "Net-(U$105-P$2)") (class "Default")
      (node (ref "U$105") (pin "2") (pinfunction "P$2_2") (pintype "bidirectional"))
      (node (ref "U$14") (pin "SHIELD") (pinfunction "SHIELD_SHIELD") (pintype "bidirectional"))
      (node (ref "U$14") (pin "SHIELD1") (pinfunction "SHIELD_SHIELD1") (pintype "bidirectional"))
    )
    (net (code "173") (name "Net-(U$106-P$2)") (class "Default")
      (node (ref "U$106") (pin "2") (pinfunction "P$2_2") (pintype "bidirectional"))
      (node (ref "U$14") (pin "GND") (pinfunction "4_GND") (pintype "bidirectional"))
    )
    (net (code "174") (name "Net-(U$107-P$2)") (class "Default")
      (node (ref "U$107") (pin "2") (pinfunction "P$2_2") (pintype "bidirectional"))
      (node (ref "U$14") (pin "VDD") (pinfunction "1_VDD") (pintype "bidirectional"))
    )
    (net (code "175") (name "Net-(U$108-P$2)") (class "Default")
      (node (ref "U$108") (pin "2") (pinfunction "P$2_2") (pintype "bidirectional"))
      (node (ref "U$47") (pin "P$1") (pinfunction "1_P$1") (pintype "bidirectional"))
    )
    (net (code "176") (name "Net-(U$109-P$2)") (class "Default")
      (node (ref "U$109") (pin "2") (pinfunction "P$2_2") (pintype "bidirectional"))
      (node (ref "U$47") (pin "P$4") (pinfunction "4_P$4") (pintype "bidirectional"))
    )
    (net (code "177") (name "Net-(U1-DM0)") (class "Default")
      (node (ref "C3") (pin "1") (pinfunction "1_1") (pintype "passive"))
      (node (ref "R17") (pin "2") (pinfunction "2_2") (pintype "passive"))
      (node (ref "U1") (pin "P$4") (pinfunction "DM0_P$4") (pintype "bidirectional"))
    )
    (net (code "178") (name "Net-(U1-DM1)") (class "Default")
      (node (ref "C30") (pin "1") (pinfunction "1_1") (pintype "passive"))
      (node (ref "R22") (pin "2") (pinfunction "2_2") (pintype "passive"))
      (node (ref "U1") (pin "P$13") (pinfunction "DM1_P$13") (pintype "bidirectional"))
    )
    (net (code "179") (name "Net-(U1-DM2)") (class "Default")
      (node (ref "C32") (pin "1") (pinfunction "1_1") (pintype "passive"))
      (node (ref "R24") (pin "2") (pinfunction "2_2") (pintype "passive"))
      (node (ref "U1") (pin "P$17") (pinfunction "DM2_P$17") (pintype "bidirectional"))
    )
    (net (code "180") (name "Net-(U1-DM3)") (class "Default")
      (node (ref "C34") (pin "1") (pinfunction "1_1") (pintype "passive"))
      (node (ref "R27") (pin "1") (pinfunction "1_1") (pintype "passive"))
      (node (ref "U1") (pin "P$21") (pinfunction "DM3_P$21") (pintype "bidirectional"))
    )
    (net (code "181") (name "Net-(U1-DM4)") (class "Default")
      (node (ref "C36") (pin "1") (pinfunction "1_1") (pintype "passive"))
      (node (ref "R28") (pin "1") (pinfunction "1_1") (pintype "passive"))
      (node (ref "U1") (pin "P$26") (pinfunction "DM4_P$26") (pintype "bidirectional"))
    )
    (net (code "182") (name "Net-(U1-DM5)") (class "Default")
      (node (ref "C38") (pin "1") (pinfunction "1_1") (pintype "passive"))
      (node (ref "R30") (pin "1") (pinfunction "1_1") (pintype "passive"))
      (node (ref "U1") (pin "P$30") (pinfunction "DM5_P$30") (pintype "bidirectional"))
    )
    (net (code "183") (name "Net-(U1-DM6)") (class "Default")
      (node (ref "C40") (pin "1") (pinfunction "1_1") (pintype "passive"))
      (node (ref "R32") (pin "1") (pinfunction "1_1") (pintype "passive"))
      (node (ref "U1") (pin "P$34") (pinfunction "DM6_P$34") (pintype "bidirectional"))
    )
    (net (code "184") (name "Net-(U1-DM7)") (class "Default")
      (node (ref "C42") (pin "1") (pinfunction "1_1") (pintype "passive"))
      (node (ref "R34") (pin "1") (pinfunction "1_1") (pintype "passive"))
      (node (ref "U1") (pin "P$38") (pinfunction "DM7_P$38") (pintype "bidirectional"))
    )
    (net (code "185") (name "Net-(U1-DP0)") (class "Default")
      (node (ref "C2") (pin "1") (pinfunction "1_1") (pintype "passive"))
      (node (ref "R16") (pin "2") (pinfunction "2_2") (pintype "passive"))
      (node (ref "R3") (pin "2") (pinfunction "2_2") (pintype "passive"))
      (node (ref "U1") (pin "P$3") (pinfunction "DP0_P$3") (pintype "bidirectional"))
    )
    (net (code "186") (name "Net-(U1-DP0PUR)") (class "Default")
      (node (ref "R16") (pin "1") (pinfunction "1_1") (pintype "passive"))
      (node (ref "U1") (pin "P$2") (pinfunction "DP0PUR_P$2") (pintype "bidirectional"))
    )
    (net (code "187") (name "Net-(U1-DP1)") (class "Default")
      (node (ref "C31") (pin "1") (pinfunction "1_1") (pintype "passive"))
      (node (ref "R23") (pin "2") (pinfunction "2_2") (pintype "passive"))
      (node (ref "U1") (pin "P$14") (pinfunction "DP1_P$14") (pintype "bidirectional"))
    )
    (net (code "188") (name "Net-(U1-DP2)") (class "Default")
      (node (ref "C33") (pin "1") (pinfunction "1_1") (pintype "passive"))
      (node (ref "R25") (pin "2") (pinfunction "2_2") (pintype "passive"))
      (node (ref "U1") (pin "P$18") (pinfunction "DP2_P$18") (pintype "bidirectional"))
    )
    (net (code "189") (name "Net-(U1-DP3)") (class "Default")
      (node (ref "C35") (pin "1") (pinfunction "1_1") (pintype "passive"))
      (node (ref "R26") (pin "1") (pinfunction "1_1") (pintype "passive"))
      (node (ref "U1") (pin "P$22") (pinfunction "DP3_P$22") (pintype "bidirectional"))
    )
    (net (code "190") (name "Net-(U1-DP4)") (class "Default")
      (node (ref "C37") (pin "1") (pinfunction "1_1") (pintype "passive"))
      (node (ref "R29") (pin "1") (pinfunction "1_1") (pintype "passive"))
      (node (ref "U1") (pin "P$27") (pinfunction "DP4_P$27") (pintype "bidirectional"))
    )
    (net (code "191") (name "Net-(U1-DP5)") (class "Default")
      (node (ref "C39") (pin "1") (pinfunction "1_1") (pintype "passive"))
      (node (ref "R31") (pin "1") (pinfunction "1_1") (pintype "passive"))
      (node (ref "U1") (pin "P$31") (pinfunction "DP5_P$31") (pintype "bidirectional"))
    )
    (net (code "192") (name "Net-(U1-DP6)") (class "Default")
      (node (ref "C41") (pin "1") (pinfunction "1_1") (pintype "passive"))
      (node (ref "R33") (pin "1") (pinfunction "1_1") (pintype "passive"))
      (node (ref "U1") (pin "P$35") (pinfunction "DP6_P$35") (pintype "bidirectional"))
    )
    (net (code "193") (name "Net-(U1-DP7)") (class "Default")
      (node (ref "C43") (pin "1") (pinfunction "1_1") (pintype "passive"))
      (node (ref "R35") (pin "1") (pinfunction "1_1") (pintype "passive"))
      (node (ref "U1") (pin "P$39") (pinfunction "DP7_P$39") (pintype "bidirectional"))
    )
    (net (code "194") (name "Net-(U1-HUBCFG)") (class "Default")
      (node (ref "R21") (pin "1") (pinfunction "1_1") (pintype "passive"))
      (node (ref "U1") (pin "P$40") (pinfunction "HUBCFG_P$40") (pintype "bidirectional"))
    )
    (net (code "195") (name "Net-(U1-PORTDIS)") (class "Default")
      (node (ref "R19") (pin "1") (pinfunction "1_1") (pintype "passive"))
      (node (ref "U1") (pin "P$42") (pinfunction "PORTDIS_P$42") (pintype "bidirectional"))
    )
    (net (code "196") (name "Net-(U1-PORTPWR)") (class "Default")
      (node (ref "R20") (pin "1") (pinfunction "1_1") (pintype "passive"))
      (node (ref "U1") (pin "P$41") (pinfunction "PORTPWR_P$41") (pintype "bidirectional"))
    )
    (net (code "197") (name "Net-(U1-SUSPND)") (class "Default")
      (node (ref "R18") (pin "1") (pinfunction "1_1") (pintype "passive"))
      (node (ref "U1") (pin "P$1") (pinfunction "SUSPND_P$1") (pintype "bidirectional"))
    )
    (net (code "198") (name "unconnected-(BATTERY-MUX-SC3-PadP$12)") (class "Default")
      (node (ref "BATTERY-MUX") (pin "P$12") (pinfunction "SC3_P$12") (pintype "bidirectional"))
    )
    (net (code "199") (name "unconnected-(BATTERY-MUX-SD3-PadP$11)") (class "Default")
      (node (ref "BATTERY-MUX") (pin "P$11") (pinfunction "SD3_P$11") (pintype "bidirectional"))
    )
    (net (code "200") (name "unconnected-(DVL_HOST_FTDI-CBUS2-Pad10)") (class "Default")
      (node (ref "DVL_HOST_FTDI") (pin "10") (pinfunction "CBUS2_10") (pintype "bidirectional"))
    )
    (net (code "201") (name "unconnected-(DVL_HOST_FTDI-CBUS3-Pad11)") (class "Default")
      (node (ref "DVL_HOST_FTDI") (pin "11") (pinfunction "CBUS3_11") (pintype "bidirectional"))
    )
    (net (code "202") (name "unconnected-(DVL_HOST_FTDI-CBUS4-Pad9)") (class "Default")
      (node (ref "DVL_HOST_FTDI") (pin "9") (pinfunction "CBUS4_9") (pintype "bidirectional"))
    )
    (net (code "203") (name "unconnected-(DVL_HOST_FTDI-OSCI-Pad27)") (class "Default")
      (node (ref "DVL_HOST_FTDI") (pin "27") (pinfunction "OSCI_27") (pintype "input"))
    )
    (net (code "204") (name "unconnected-(DVL_HOST_FTDI-OSCO-Pad28)") (class "Default")
      (node (ref "DVL_HOST_FTDI") (pin "28") (pinfunction "OSCO_28") (pintype "output"))
    )
    (net (code "205") (name "unconnected-(DVL_HOST_FTDI-~{DCD}-Pad7)") (class "Default")
      (node (ref "DVL_HOST_FTDI") (pin "7") (pinfunction "~{DCD}_7") (pintype "input"))
    )
    (net (code "206") (name "unconnected-(DVL_HOST_FTDI-~{DSR}-Pad6)") (class "Default")
      (node (ref "DVL_HOST_FTDI") (pin "6") (pinfunction "~{DSR}_6") (pintype "input"))
    )
    (net (code "207") (name "unconnected-(DVL_HOST_FTDI-~{DTR}-Pad31)") (class "Default")
      (node (ref "DVL_HOST_FTDI") (pin "31") (pinfunction "~{DTR}_31") (pintype "output"))
    )
    (net (code "208") (name "unconnected-(DVL_HOST_FTDI-~{RI}-Pad3)") (class "Default")
      (node (ref "DVL_HOST_FTDI") (pin "3") (pinfunction "~{RI}_3") (pintype "input"))
    )
    (net (code "209") (name "unconnected-(DVL_SLAVE_FTDI-CBUS2-Pad10)") (class "Default")
      (node (ref "DVL_SLAVE_FTDI") (pin "10") (pinfunction "CBUS2_10") (pintype "bidirectional"))
    )
    (net (code "210") (name "unconnected-(DVL_SLAVE_FTDI-CBUS3-Pad11)") (class "Default")
      (node (ref "DVL_SLAVE_FTDI") (pin "11") (pinfunction "CBUS3_11") (pintype "bidirectional"))
    )
    (net (code "211") (name "unconnected-(DVL_SLAVE_FTDI-CBUS4-Pad9)") (class "Default")
      (node (ref "DVL_SLAVE_FTDI") (pin "9") (pinfunction "CBUS4_9") (pintype "bidirectional"))
    )
    (net (code "212") (name "unconnected-(DVL_SLAVE_FTDI-OSCI-Pad27)") (class "Default")
      (node (ref "DVL_SLAVE_FTDI") (pin "27") (pinfunction "OSCI_27") (pintype "input"))
    )
    (net (code "213") (name "unconnected-(DVL_SLAVE_FTDI-OSCO-Pad28)") (class "Default")
      (node (ref "DVL_SLAVE_FTDI") (pin "28") (pinfunction "OSCO_28") (pintype "output"))
    )
    (net (code "214") (name "unconnected-(DVL_SLAVE_FTDI-~{DCD}-Pad7)") (class "Default")
      (node (ref "DVL_SLAVE_FTDI") (pin "7") (pinfunction "~{DCD}_7") (pintype "input"))
    )
    (net (code "215") (name "unconnected-(DVL_SLAVE_FTDI-~{DSR}-Pad6)") (class "Default")
      (node (ref "DVL_SLAVE_FTDI") (pin "6") (pinfunction "~{DSR}_6") (pintype "input"))
    )
    (net (code "216") (name "unconnected-(DVL_SLAVE_FTDI-~{DTR}-Pad31)") (class "Default")
      (node (ref "DVL_SLAVE_FTDI") (pin "31") (pinfunction "~{DTR}_31") (pintype "output"))
    )
    (net (code "217") (name "unconnected-(DVL_SLAVE_FTDI-~{RI}-Pad3)") (class "Default")
      (node (ref "DVL_SLAVE_FTDI") (pin "3") (pinfunction "~{RI}_3") (pintype "input"))
    )
    (net (code "218") (name "unconnected-(DVL_TTL-TO-RS232-RIN5-Pad18)") (class "Default")
      (node (ref "DVL_TTL-TO-RS232") (pin "18") (pinfunction "RIN5_18") (pintype "bidirectional"))
    )
    (net (code "219") (name "unconnected-(DVL_TTL-TO-RS232-ROUT5-Pad19)") (class "Default")
      (node (ref "DVL_TTL-TO-RS232") (pin "19") (pinfunction "ROUT5_19") (pintype "bidirectional"))
    )
    (net (code "220") (name "unconnected-(DVL_USB_HUB-NC-PadP$5)") (class "Default")
      (node (ref "DVL_USB_HUB") (pin "P$5") (pinfunction "NC_P$5") (pintype "bidirectional"))
    )
    (net (code "221") (name "unconnected-(DVL_USB_HUB-NC-PadP$6)") (class "Default")
      (node (ref "DVL_USB_HUB") (pin "P$6") (pinfunction "NC_P$6") (pintype "bidirectional"))
    )
    (net (code "222") (name "unconnected-(DVL_USB_HUB-OCS_N1-PadP$8)") (class "Default")
      (node (ref "DVL_USB_HUB") (pin "P$8") (pinfunction "OCS_N1_P$8") (pintype "bidirectional"))
    )
    (net (code "223") (name "unconnected-(DVL_USB_HUB-OCS_N2-PadP$12)") (class "Default")
      (node (ref "DVL_USB_HUB") (pin "P$12") (pinfunction "OCS_N2_P$12") (pintype "bidirectional"))
    )
    (net (code "224") (name "unconnected-(DVL_USB_HUB-XTALOUT-PadP$23)") (class "Default")
      (node (ref "DVL_USB_HUB") (pin "P$23") (pinfunction "XTALOUT_P$23") (pintype "bidirectional"))
    )
    (net (code "225") (name "unconnected-(G1-PadOUT4)") (class "Default")
      (node (ref "G1") (pin "OUT4") (pinfunction "OUT4_OUT4") (pintype "bidirectional"))
    )
    (net (code "226") (name "unconnected-(G1-~{EN4}-Pad!EN4!)") (class "Default")
      (node (ref "G1") (pin "!EN4!") (pinfunction "~{EN4}_!EN4!") (pintype "bidirectional"))
    )
    (net (code "227") (name "unconnected-(G1-~{OC4}-Pad!OC4!)") (class "Default")
      (node (ref "G1") (pin "!OC4!") (pinfunction "~{OC4}_!OC4!") (pintype "bidirectional"))
    )
    (net (code "228") (name "unconnected-(U$37-N.C-Pad1)") (class "Default")
      (node (ref "U$37") (pin "1") (pinfunction "N.C_1") (pintype "bidirectional"))
    )
    (net (code "229") (name "unconnected-(U$37-NC-Pad5)") (class "Default")
      (node (ref "U$37") (pin "5") (pinfunction "NC_5") (pintype "bidirectional"))
    )
    (net (code "230") (name "unconnected-(U$38-N.C-Pad1)") (class "Default")
      (node (ref "U$38") (pin "1") (pinfunction "N.C_1") (pintype "bidirectional"))
    )
    (net (code "231") (name "unconnected-(U$38-NC-Pad5)") (class "Default")
      (node (ref "U$38") (pin "5") (pinfunction "NC_5") (pintype "bidirectional"))
    )
    (net (code "232") (name "unconnected-(U$39-N.C-Pad1)") (class "Default")
      (node (ref "U$39") (pin "1") (pinfunction "N.C_1") (pintype "bidirectional"))
    )
    (net (code "233") (name "unconnected-(U$39-NC-Pad5)") (class "Default")
      (node (ref "U$39") (pin "5") (pinfunction "NC_5") (pintype "bidirectional"))
    )
    (net (code "234") (name "unconnected-(U$40-N.C-Pad1)") (class "Default")
      (node (ref "U$40") (pin "1") (pinfunction "N.C_1") (pintype "bidirectional"))
    )
    (net (code "235") (name "unconnected-(U$40-NC-Pad5)") (class "Default")
      (node (ref "U$40") (pin "5") (pinfunction "NC_5") (pintype "bidirectional"))
    )
    (net (code "236") (name "unconnected-(U$50-N.C-Pad1)") (class "Default")
      (node (ref "U$50") (pin "1") (pinfunction "N.C_1") (pintype "bidirectional"))
    )
    (net (code "237") (name "unconnected-(U$50-NC-Pad5)") (class "Default")
      (node (ref "U$50") (pin "5") (pinfunction "NC_5") (pintype "bidirectional"))
    )
    (net (code "238") (name "unconnected-(U1-EECLK-PadP$7)") (class "Default")
      (node (ref "U1") (pin "P$7") (pinfunction "EECLK_P$7") (pintype "bidirectional"))
    )
    (net (code "239") (name "unconnected-(U1-XTAL2-PadP$44)") (class "Default")
      (node (ref "U1") (pin "P$44") (pinfunction "XTAL2_P$44") (pintype "bidirectional"))
    )
    (net (code "240") (name "unconnected-(U1-~{PWRON1}-PadP$11)") (class "Default")
      (node (ref "U1") (pin "P$11") (pinfunction "~{PWRON1}_P$11") (pintype "bidirectional"))
    )
    (net (code "241") (name "unconnected-(U1-~{PWRON2}-PadP$15)") (class "Default")
      (node (ref "U1") (pin "P$15") (pinfunction "~{PWRON2}_P$15") (pintype "bidirectional"))
    )
    (net (code "242") (name "unconnected-(U1-~{PWRON3}-PadP$19)") (class "Default")
      (node (ref "U1") (pin "P$19") (pinfunction "~{PWRON3}_P$19") (pintype "bidirectional"))
    )
    (net (code "243") (name "unconnected-(U1-~{PWRON4}-PadP$23)") (class "Default")
      (node (ref "U1") (pin "P$23") (pinfunction "~{PWRON4}_P$23") (pintype "bidirectional"))
    )
  )
)
